# GC_LINE_2026_INCHEON.net
KiCad netlist of a schematic drawn in EAGLE
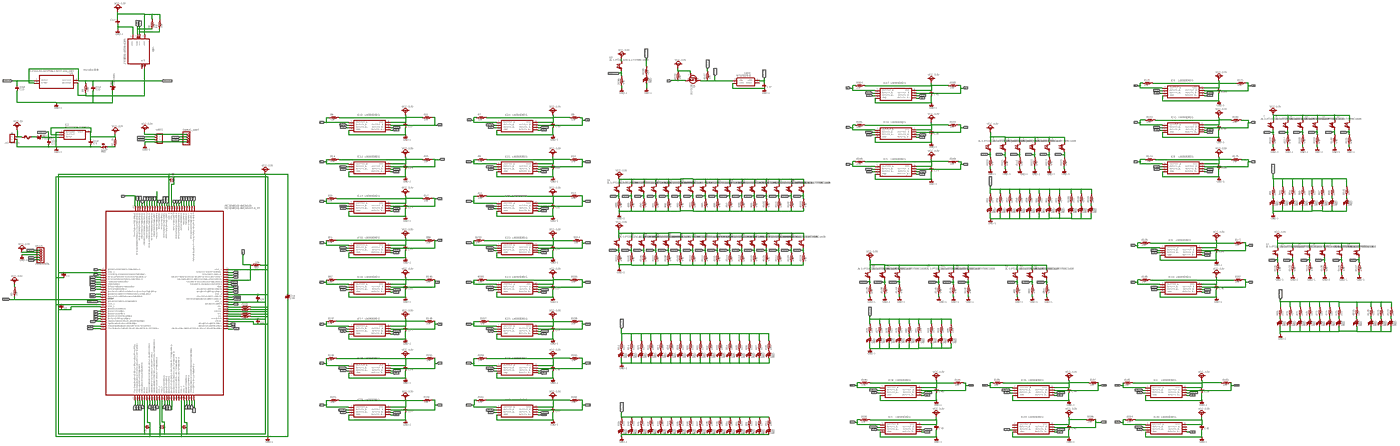
[diagram p0: schematic, sheet 1, overview]
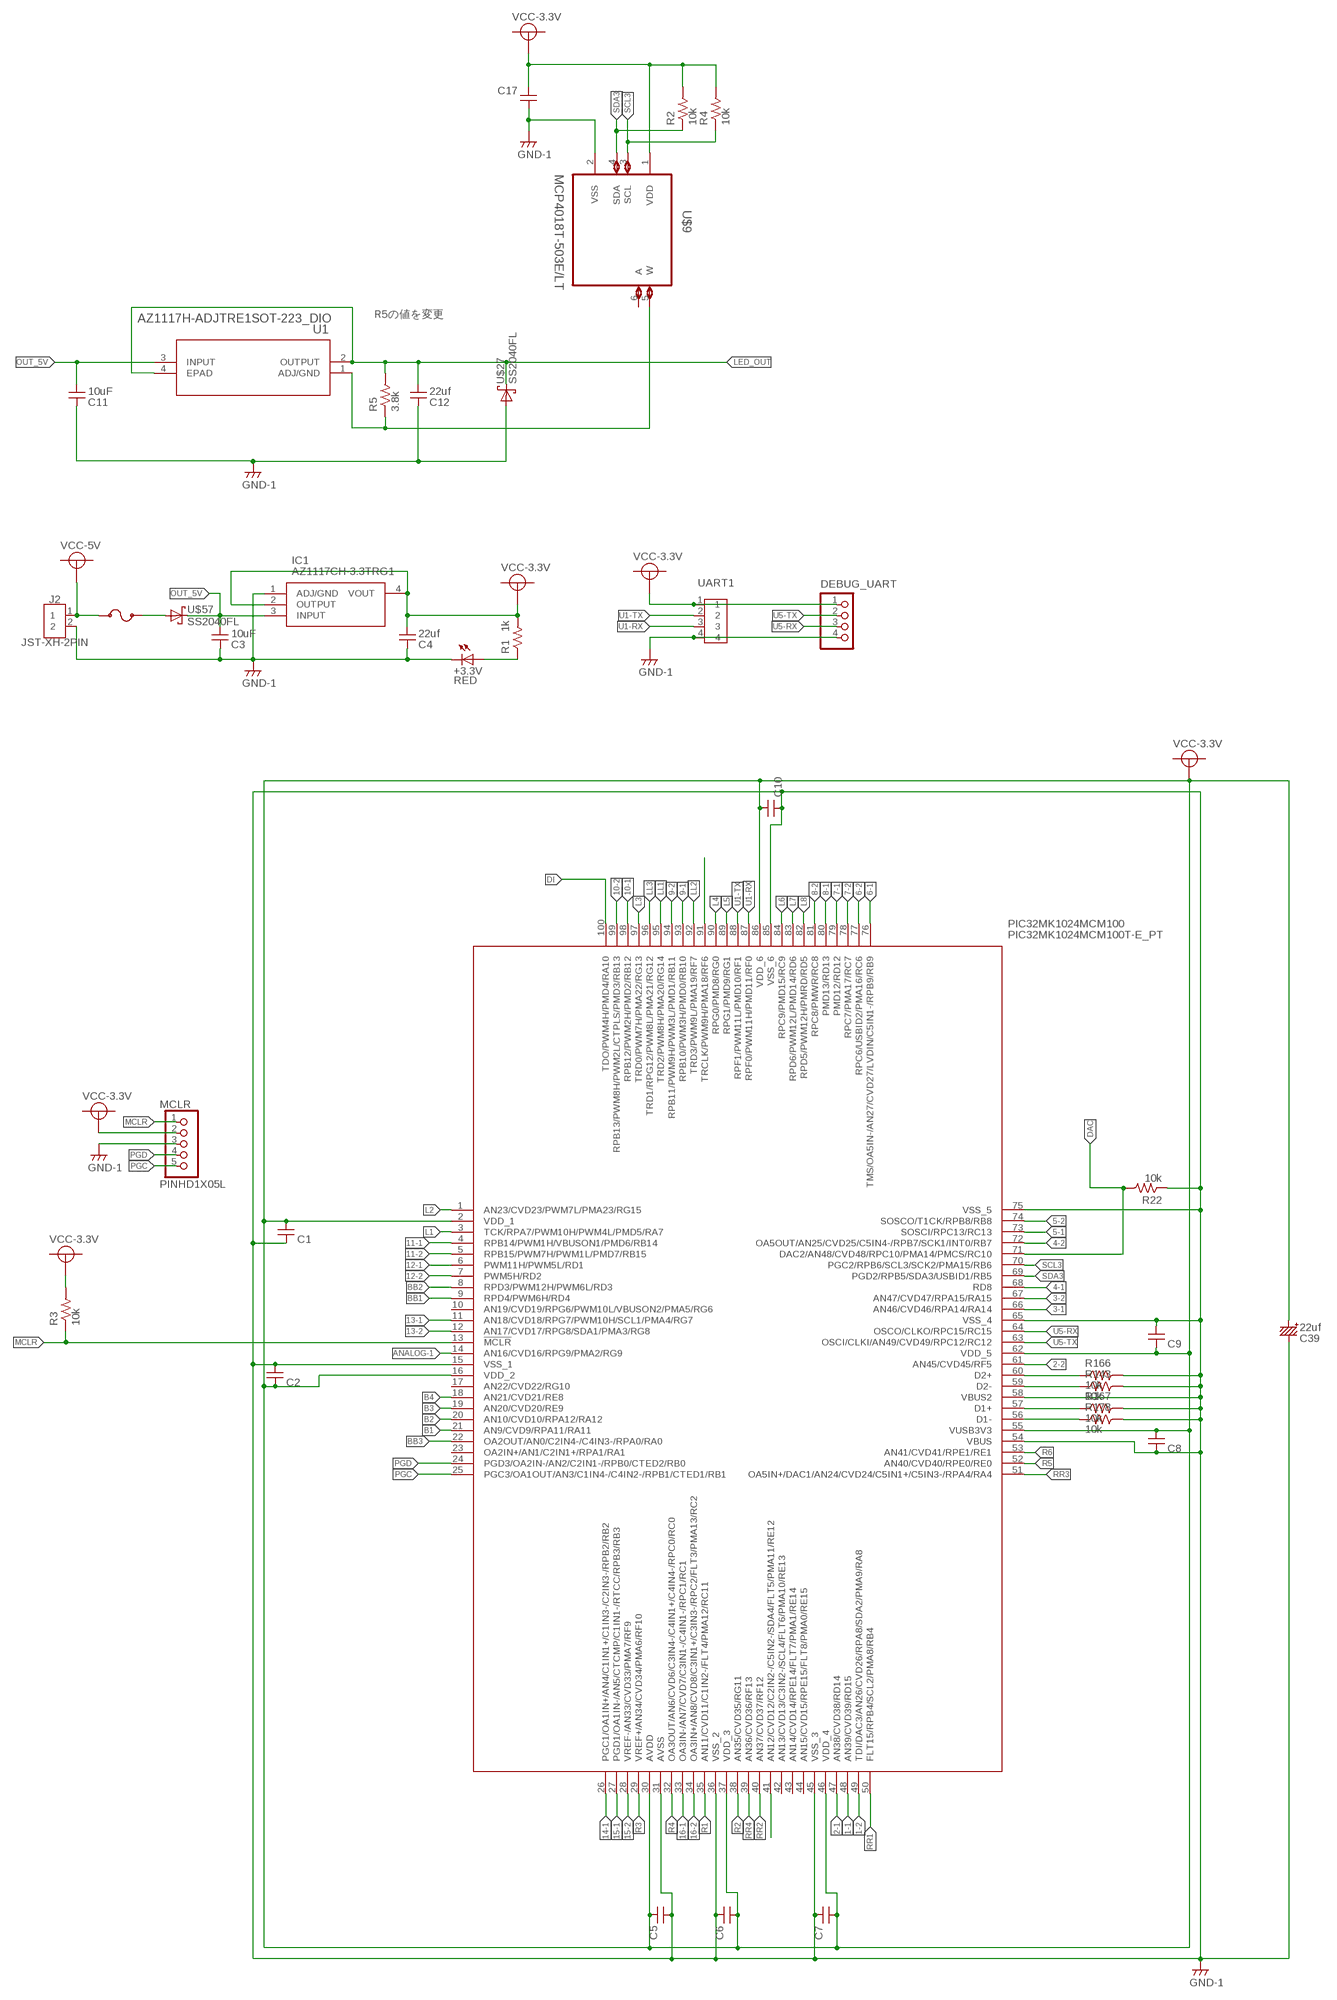
[diagram p1: schematic, sheet 1, part 1 of 4]
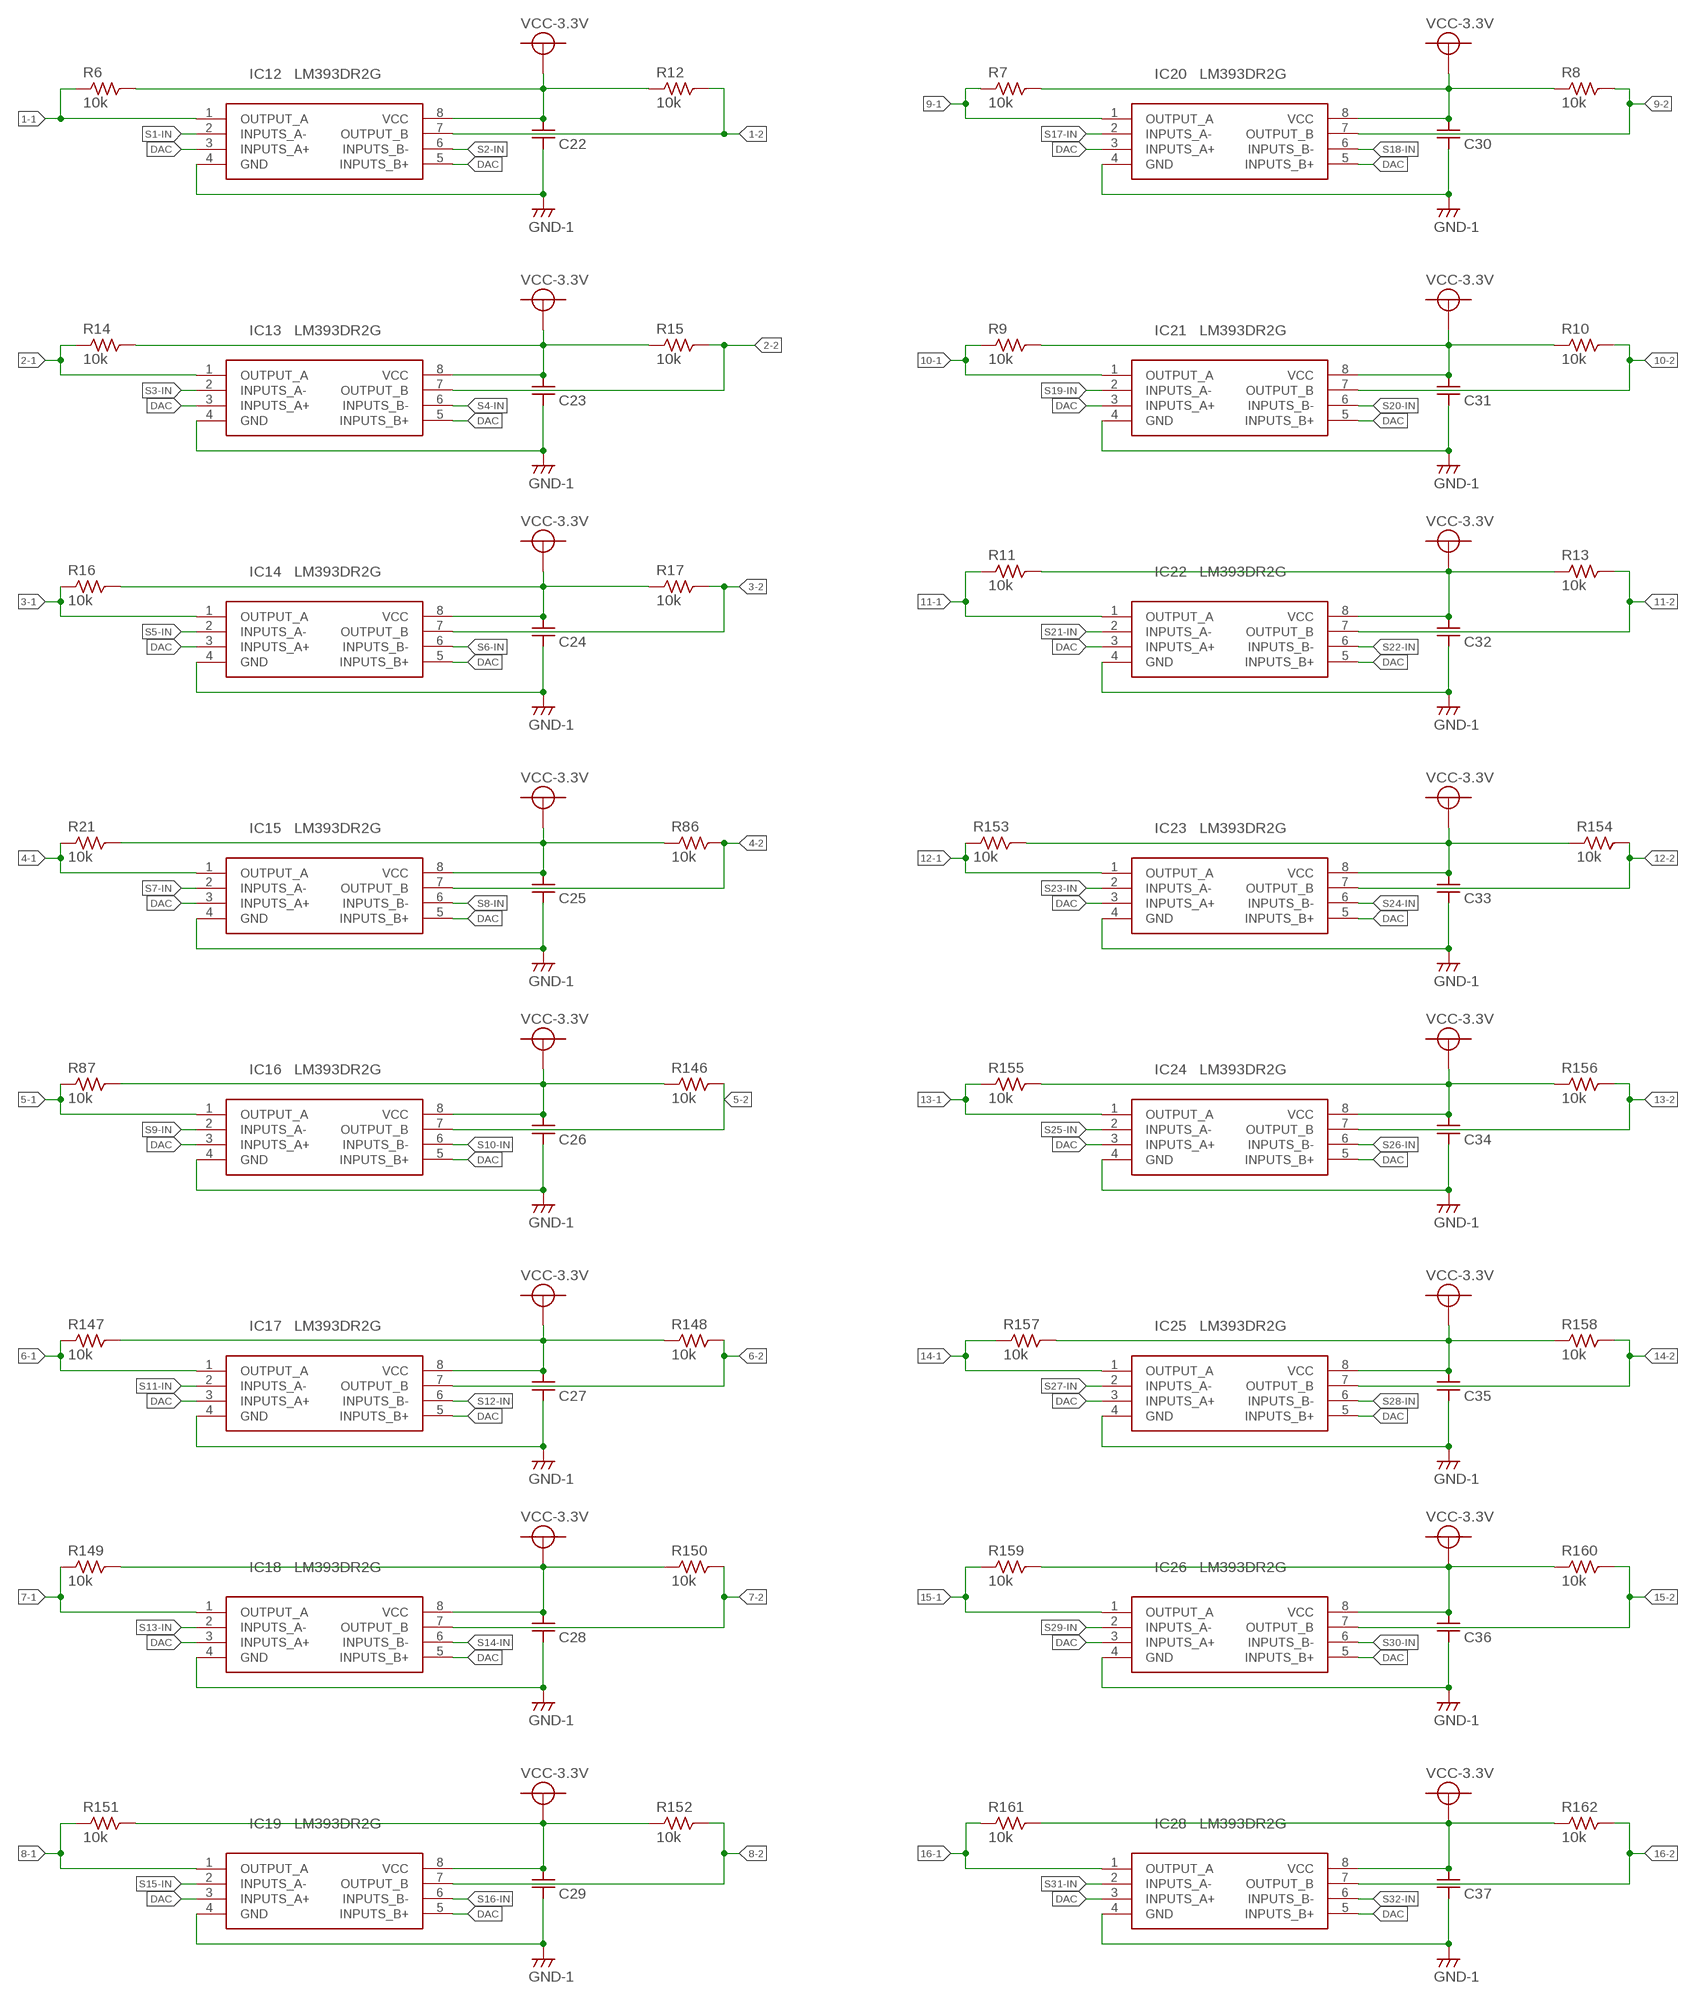
[diagram p2: schematic, sheet 1, part 2 of 4]
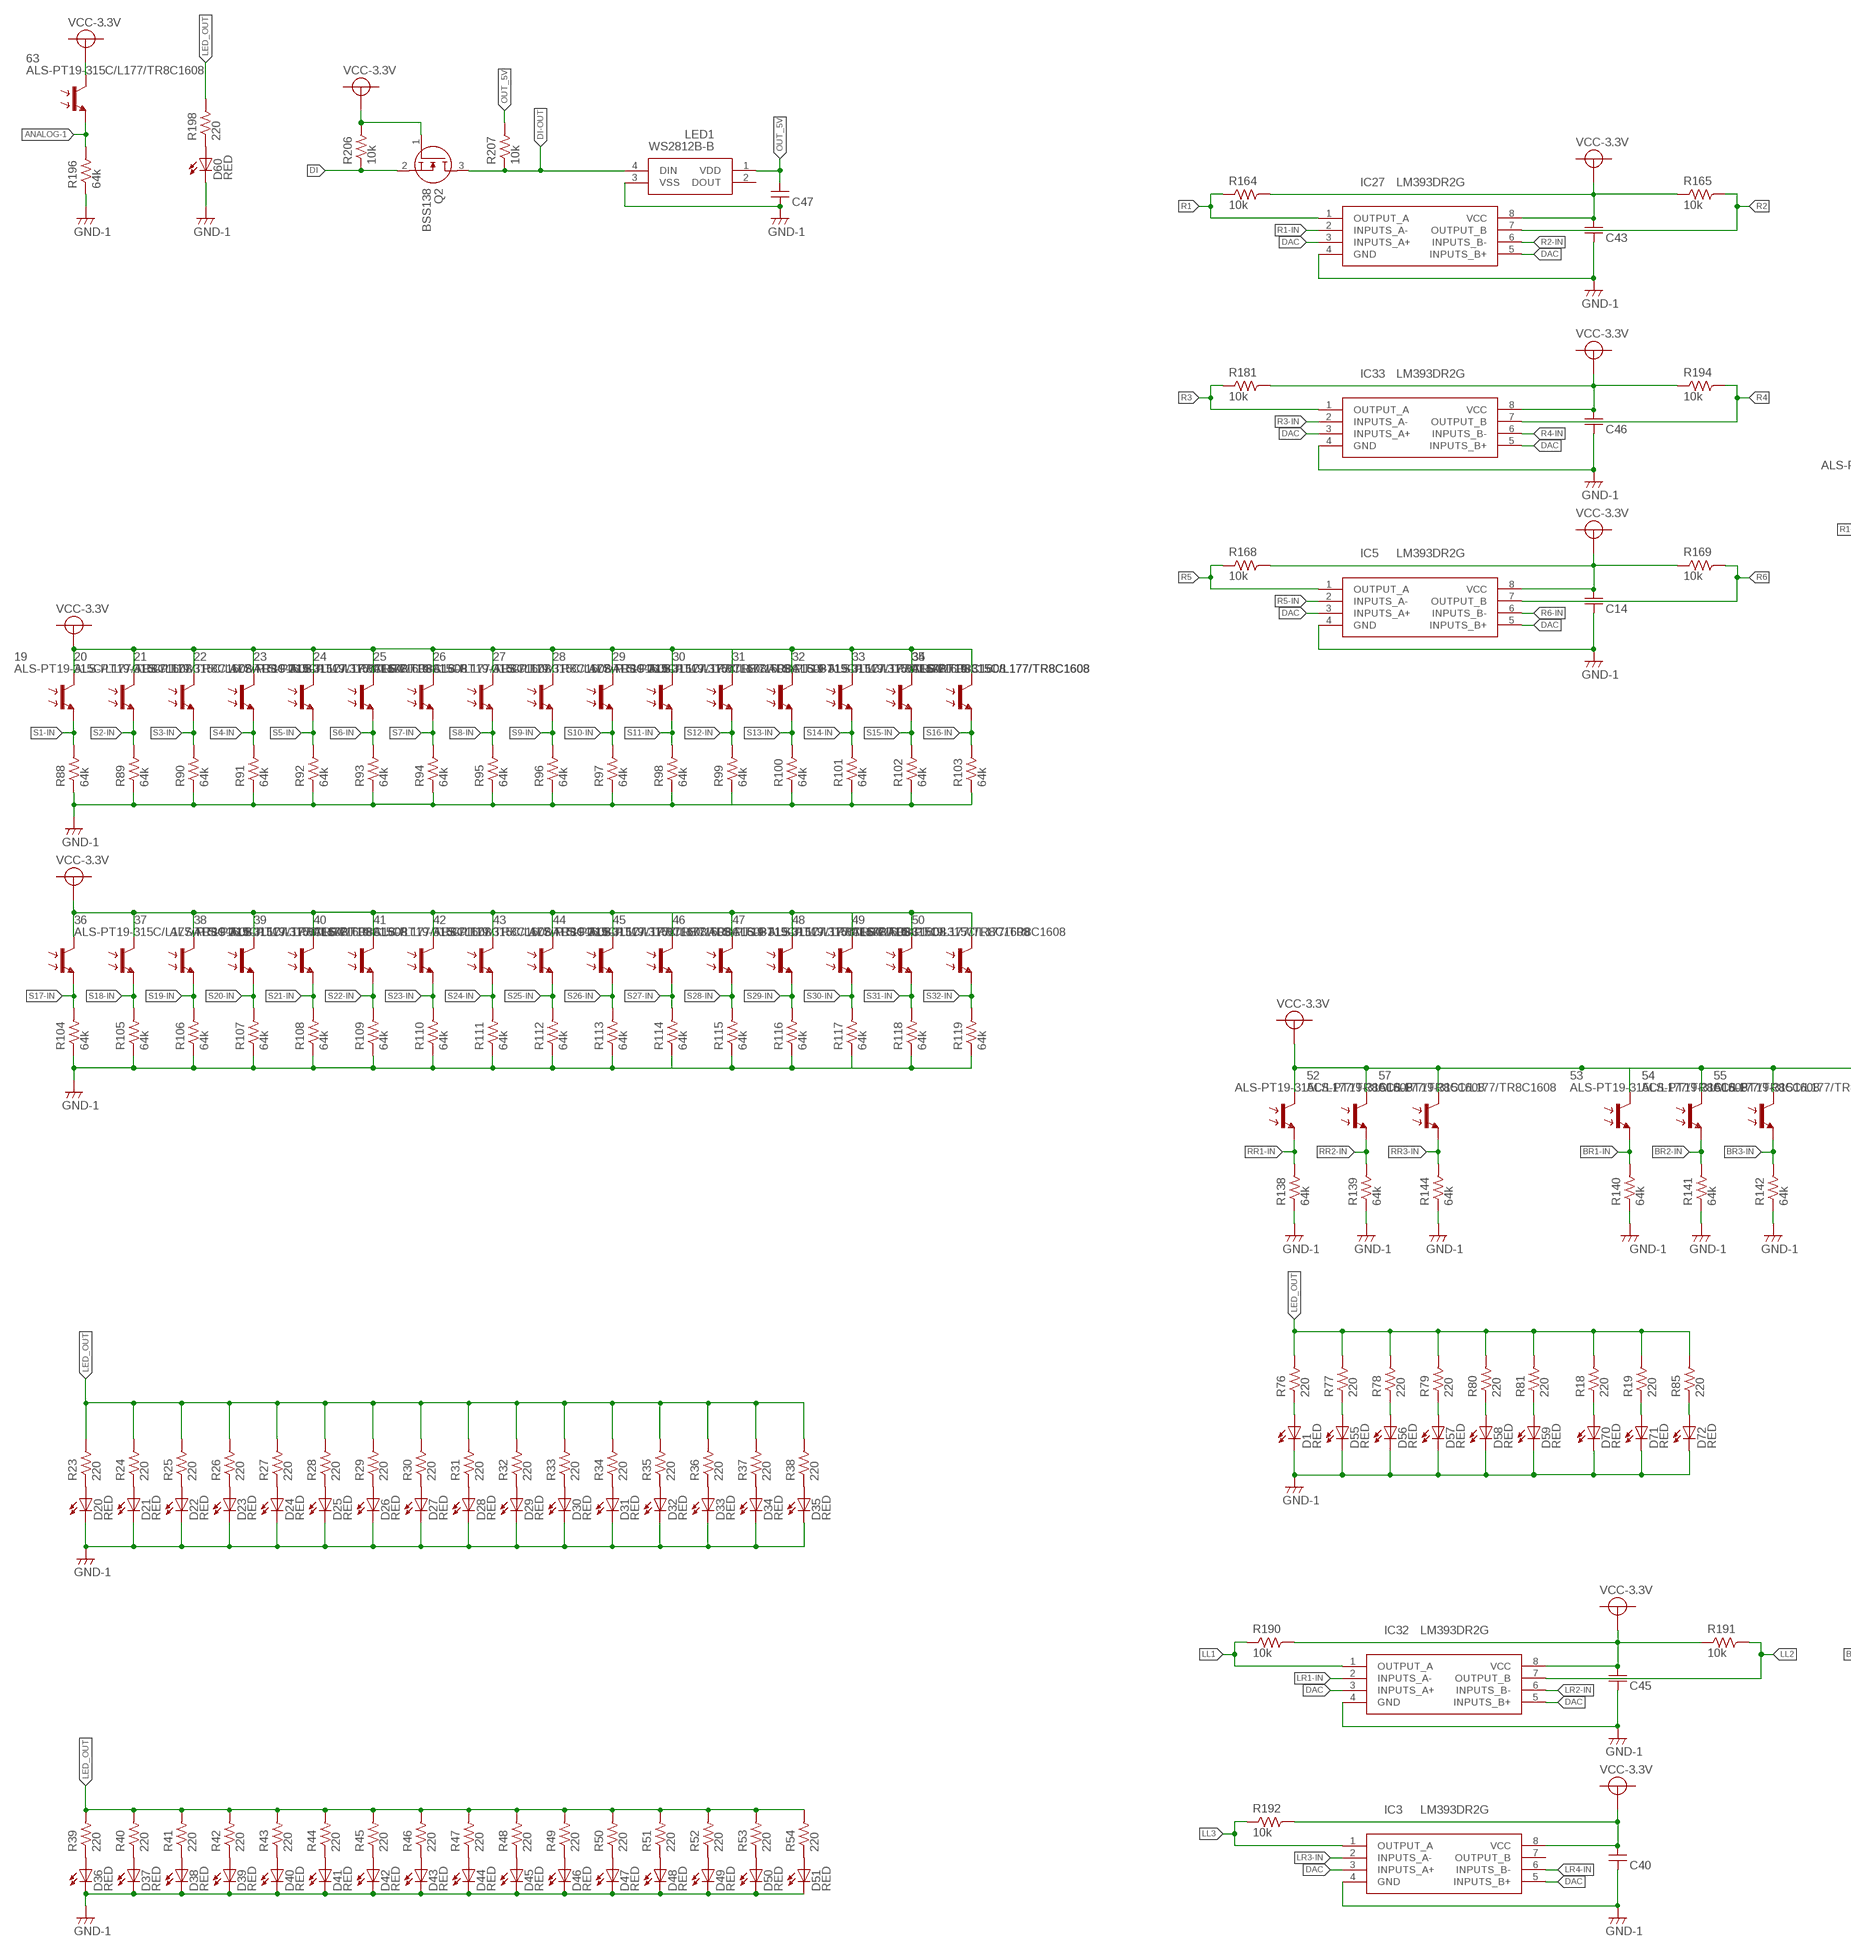
[diagram p3: schematic, sheet 1, part 3 of 4]
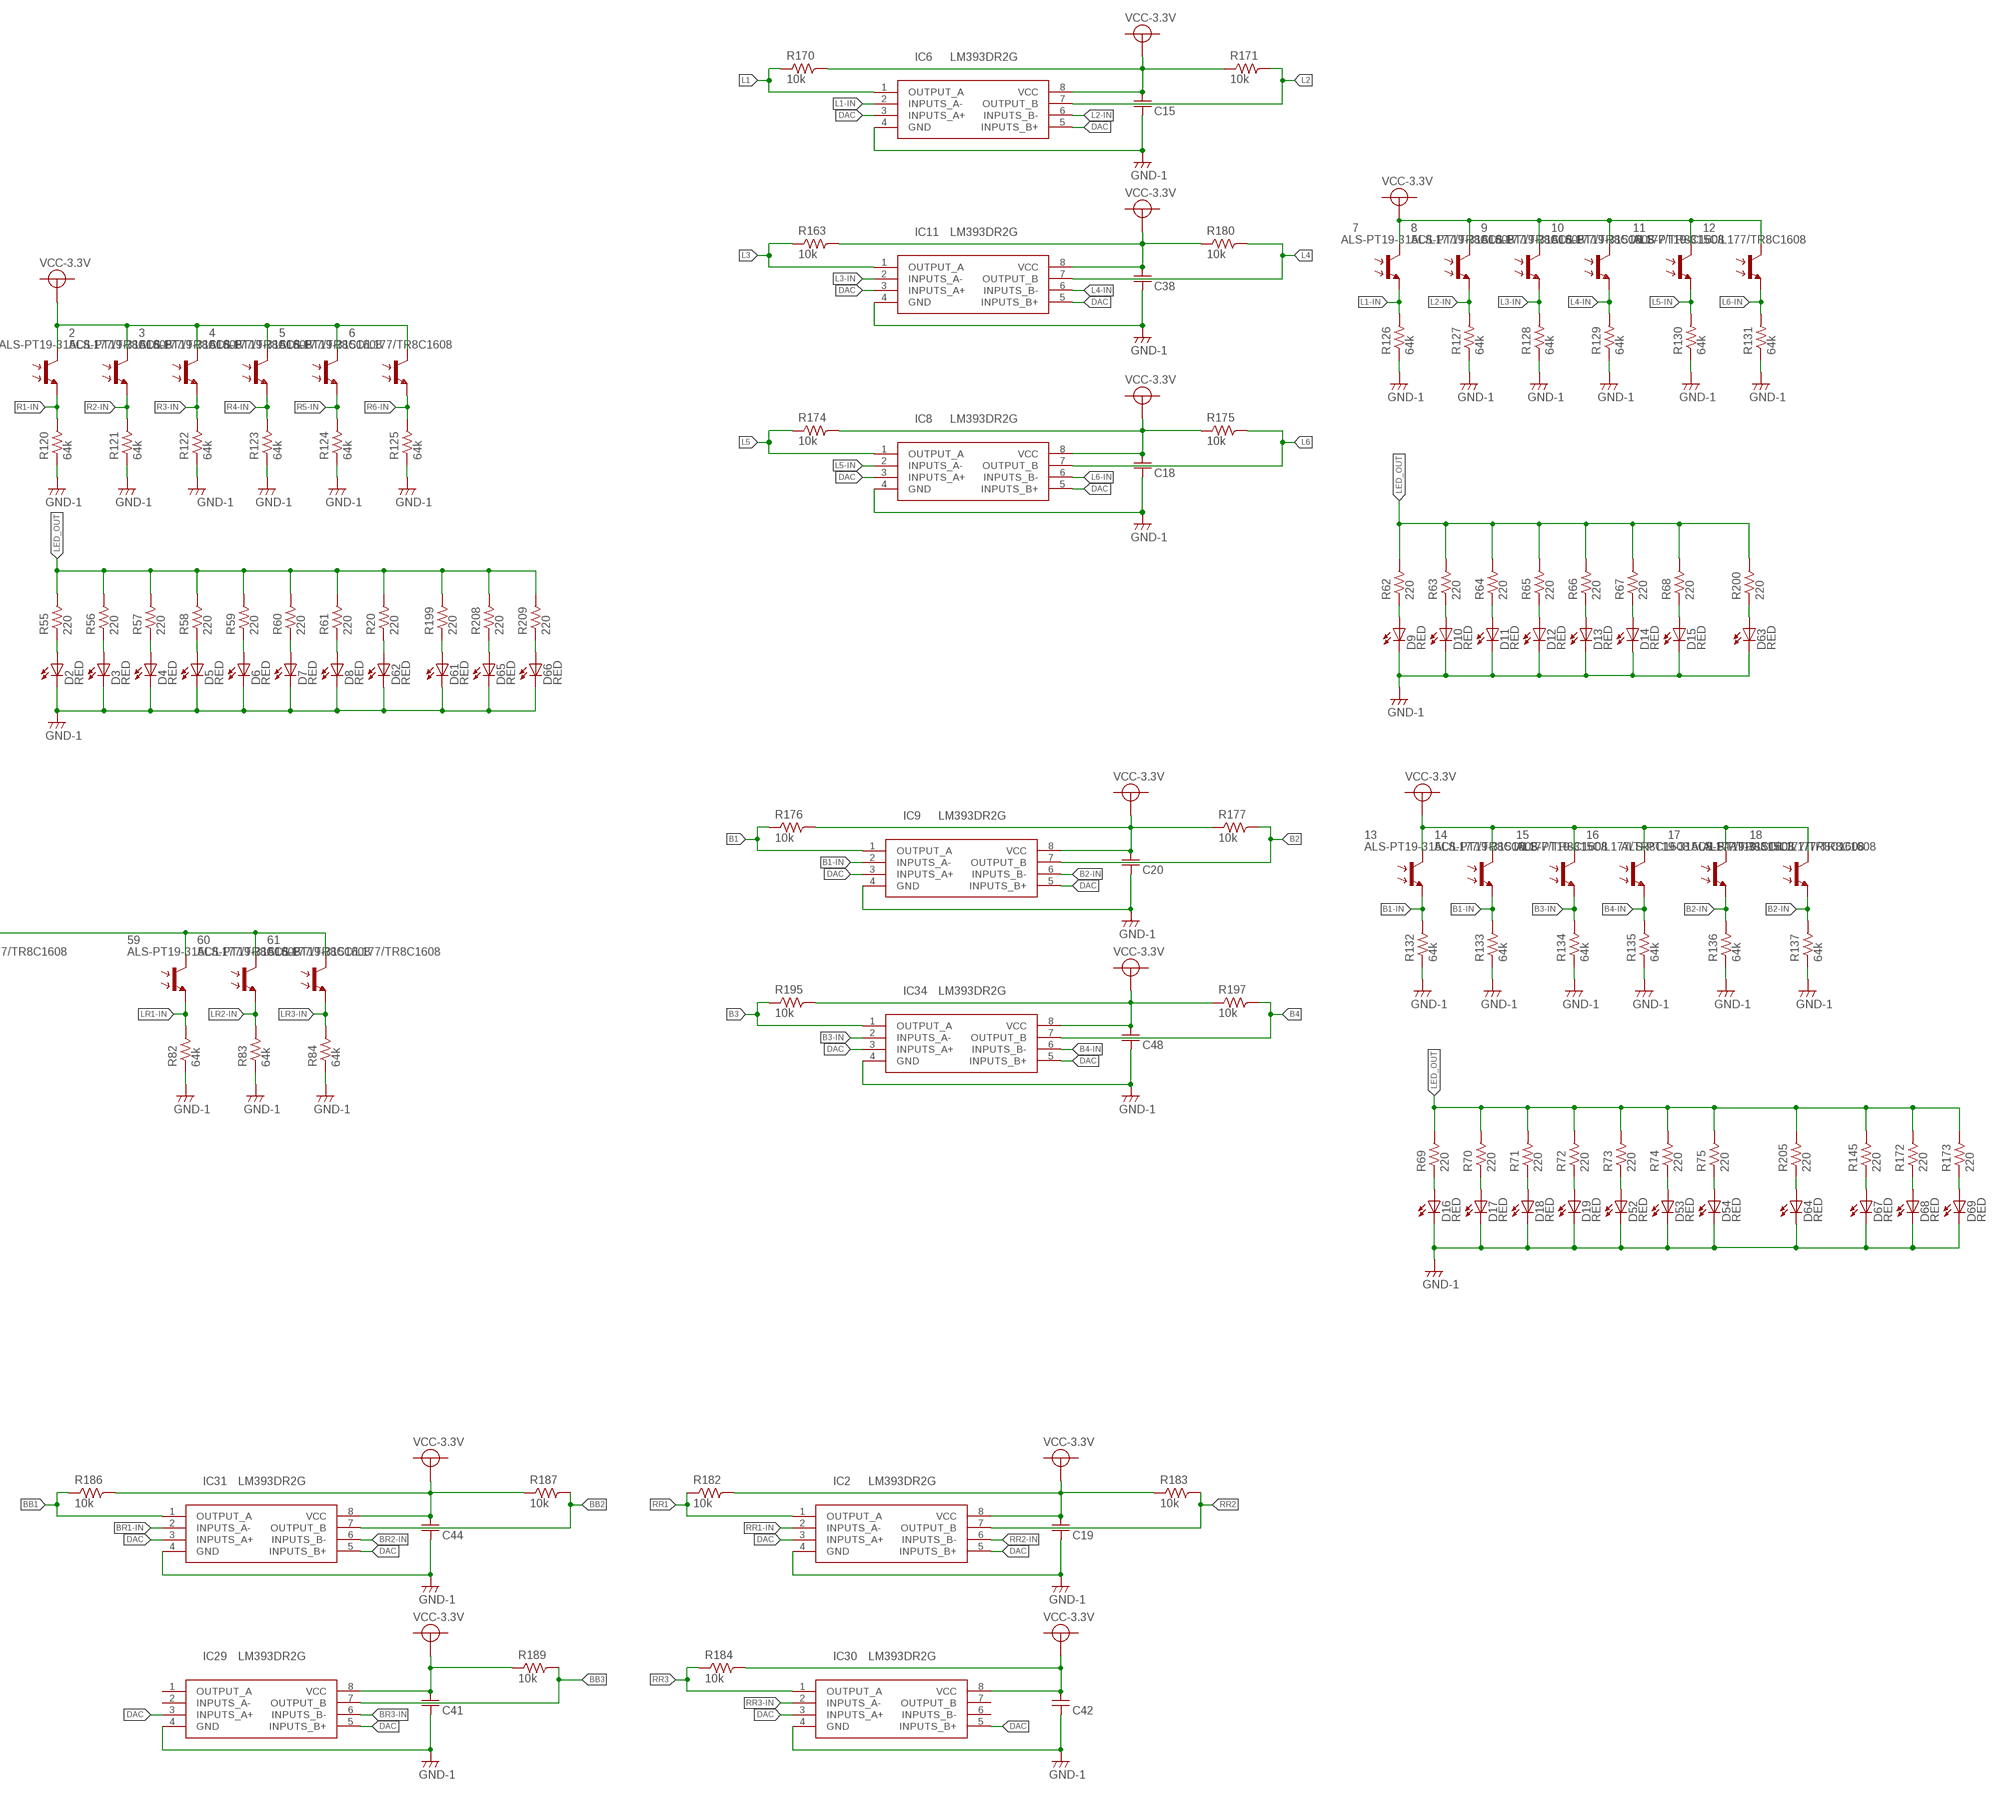
[diagram p4: schematic, sheet 1, part 4 of 4]

(export (version "E")
  (design (tool "Eeschema 10.0.6"))
  (components
    (comp (ref "+3.3V")
      (value "RED")
      (footprint "eagle-import:LEDC1608X55N_FLAT-R")
      (libsource (lib "eagle-import") (part "LEDRED"))
    )
    (comp (ref "1")
      (value "ALS-PT19-315C/L177/TR8C1608")
      (footprint "eagle-import:C1608")
      (libsource (lib "eagle-import") (part "ALS-PT19-315C/L177/TR8C1608"))
    )
    (comp (ref "2")
      (value "ALS-PT19-315C/L177/TR8C1608")
      (footprint "eagle-import:C1608")
      (libsource (lib "eagle-import") (part "ALS-PT19-315C/L177/TR8C1608"))
    )
    (comp (ref "3")
      (value "ALS-PT19-315C/L177/TR8C1608")
      (footprint "eagle-import:C1608")
      (libsource (lib "eagle-import") (part "ALS-PT19-315C/L177/TR8C1608"))
    )
    (comp (ref "4")
      (value "ALS-PT19-315C/L177/TR8C1608")
      (footprint "eagle-import:C1608")
      (libsource (lib "eagle-import") (part "ALS-PT19-315C/L177/TR8C1608"))
    )
    (comp (ref "5")
      (value "ALS-PT19-315C/L177/TR8C1608")
      (footprint "eagle-import:C1608")
      (libsource (lib "eagle-import") (part "ALS-PT19-315C/L177/TR8C1608"))
    )
    (comp (ref "6")
      (value "ALS-PT19-315C/L177/TR8C1608")
      (footprint "eagle-import:C1608")
      (libsource (lib "eagle-import") (part "ALS-PT19-315C/L177/TR8C1608"))
    )
    (comp (ref "7")
      (value "ALS-PT19-315C/L177/TR8C1608")
      (footprint "eagle-import:C1608")
      (libsource (lib "eagle-import") (part "ALS-PT19-315C/L177/TR8C1608"))
    )
    (comp (ref "8")
      (value "ALS-PT19-315C/L177/TR8C1608")
      (footprint "eagle-import:C1608")
      (libsource (lib "eagle-import") (part "ALS-PT19-315C/L177/TR8C1608"))
    )
    (comp (ref "9")
      (value "ALS-PT19-315C/L177/TR8C1608")
      (footprint "eagle-import:C1608")
      (libsource (lib "eagle-import") (part "ALS-PT19-315C/L177/TR8C1608"))
    )
    (comp (ref "10")
      (value "ALS-PT19-315C/L177/TR8C1608")
      (footprint "eagle-import:C1608")
      (libsource (lib "eagle-import") (part "ALS-PT19-315C/L177/TR8C1608"))
    )
    (comp (ref "11")
      (value "ALS-PT19-315C/L177/TR8C1608")
      (footprint "eagle-import:C1608")
      (libsource (lib "eagle-import") (part "ALS-PT19-315C/L177/TR8C1608"))
    )
    (comp (ref "12")
      (value "ALS-PT19-315C/L177/TR8C1608")
      (footprint "eagle-import:C1608")
      (libsource (lib "eagle-import") (part "ALS-PT19-315C/L177/TR8C1608"))
    )
    (comp (ref "13")
      (value "ALS-PT19-315C/L177/TR8C1608")
      (footprint "eagle-import:C1608")
      (libsource (lib "eagle-import") (part "ALS-PT19-315C/L177/TR8C1608"))
    )
    (comp (ref "14")
      (value "ALS-PT19-315C/L177/TR8C1608")
      (footprint "eagle-import:C1608")
      (libsource (lib "eagle-import") (part "ALS-PT19-315C/L177/TR8C1608"))
    )
    (comp (ref "15")
      (value "ALS-PT19-315C/L177/TR8C1608")
      (footprint "eagle-import:C1608")
      (libsource (lib "eagle-import") (part "ALS-PT19-315C/L177/TR8C1608"))
    )
    (comp (ref "16")
      (value "ALS-PT19-315C/L177/TR8C1608")
      (footprint "eagle-import:C1608")
      (libsource (lib "eagle-import") (part "ALS-PT19-315C/L177/TR8C1608"))
    )
    (comp (ref "17")
      (value "ALS-PT19-315C/L177/TR8C1608")
      (footprint "eagle-import:C1608")
      (libsource (lib "eagle-import") (part "ALS-PT19-315C/L177/TR8C1608"))
    )
    (comp (ref "18")
      (value "ALS-PT19-315C/L177/TR8C1608")
      (footprint "eagle-import:C1608")
      (libsource (lib "eagle-import") (part "ALS-PT19-315C/L177/TR8C1608"))
    )
    (comp (ref "19")
      (value "ALS-PT19-315C/L177/TR8C1608")
      (footprint "eagle-import:C1608")
      (libsource (lib "eagle-import") (part "ALS-PT19-315C/L177/TR8C1608"))
    )
    (comp (ref "20")
      (value "ALS-PT19-315C/L177/TR8C1608")
      (footprint "eagle-import:C1608")
      (libsource (lib "eagle-import") (part "ALS-PT19-315C/L177/TR8C1608"))
    )
    (comp (ref "21")
      (value "ALS-PT19-315C/L177/TR8C1608")
      (footprint "eagle-import:C1608")
      (libsource (lib "eagle-import") (part "ALS-PT19-315C/L177/TR8C1608"))
    )
    (comp (ref "22")
      (value "ALS-PT19-315C/L177/TR8C1608")
      (footprint "eagle-import:C1608")
      (libsource (lib "eagle-import") (part "ALS-PT19-315C/L177/TR8C1608"))
    )
    (comp (ref "23")
      (value "ALS-PT19-315C/L177/TR8C1608")
      (footprint "eagle-import:C1608")
      (libsource (lib "eagle-import") (part "ALS-PT19-315C/L177/TR8C1608"))
    )
    (comp (ref "24")
      (value "ALS-PT19-315C/L177/TR8C1608")
      (footprint "eagle-import:C1608")
      (libsource (lib "eagle-import") (part "ALS-PT19-315C/L177/TR8C1608"))
    )
    (comp (ref "25")
      (value "ALS-PT19-315C/L177/TR8C1608")
      (footprint "eagle-import:C1608")
      (libsource (lib "eagle-import") (part "ALS-PT19-315C/L177/TR8C1608"))
    )
    (comp (ref "26")
      (value "ALS-PT19-315C/L177/TR8C1608")
      (footprint "eagle-import:C1608")
      (libsource (lib "eagle-import") (part "ALS-PT19-315C/L177/TR8C1608"))
    )
    (comp (ref "27")
      (value "ALS-PT19-315C/L177/TR8C1608")
      (footprint "eagle-import:C1608")
      (libsource (lib "eagle-import") (part "ALS-PT19-315C/L177/TR8C1608"))
    )
    (comp (ref "28")
      (value "ALS-PT19-315C/L177/TR8C1608")
      (footprint "eagle-import:C1608")
      (libsource (lib "eagle-import") (part "ALS-PT19-315C/L177/TR8C1608"))
    )
    (comp (ref "29")
      (value "ALS-PT19-315C/L177/TR8C1608")
      (footprint "eagle-import:C1608")
      (libsource (lib "eagle-import") (part "ALS-PT19-315C/L177/TR8C1608"))
    )
    (comp (ref "30")
      (value "ALS-PT19-315C/L177/TR8C1608")
      (footprint "eagle-import:C1608")
      (libsource (lib "eagle-import") (part "ALS-PT19-315C/L177/TR8C1608"))
    )
    (comp (ref "31")
      (value "ALS-PT19-315C/L177/TR8C1608")
      (footprint "eagle-import:C1608")
      (libsource (lib "eagle-import") (part "ALS-PT19-315C/L177/TR8C1608"))
    )
    (comp (ref "32")
      (value "ALS-PT19-315C/L177/TR8C1608")
      (footprint "eagle-import:C1608")
      (libsource (lib "eagle-import") (part "ALS-PT19-315C/L177/TR8C1608"))
    )
    (comp (ref "33")
      (value "ALS-PT19-315C/L177/TR8C1608")
      (footprint "eagle-import:C1608")
      (libsource (lib "eagle-import") (part "ALS-PT19-315C/L177/TR8C1608"))
    )
    (comp (ref "34")
      (value "ALS-PT19-315C/L177/TR8C1608")
      (footprint "eagle-import:C1608")
      (libsource (lib "eagle-import") (part "ALS-PT19-315C/L177/TR8C1608"))
    )
    (comp (ref "35")
      (value "ALS-PT19-315C/L177/TR8C1608")
      (footprint "eagle-import:C1608")
      (libsource (lib "eagle-import") (part "ALS-PT19-315C/L177/TR8C1608"))
    )
    (comp (ref "36")
      (value "ALS-PT19-315C/L177/TR8C1608")
      (footprint "eagle-import:C1608")
      (libsource (lib "eagle-import") (part "ALS-PT19-315C/L177/TR8C1608"))
    )
    (comp (ref "37")
      (value "ALS-PT19-315C/L177/TR8C1608")
      (footprint "eagle-import:C1608")
      (libsource (lib "eagle-import") (part "ALS-PT19-315C/L177/TR8C1608"))
    )
    (comp (ref "38")
      (value "ALS-PT19-315C/L177/TR8C1608")
      (footprint "eagle-import:C1608")
      (libsource (lib "eagle-import") (part "ALS-PT19-315C/L177/TR8C1608"))
    )
    (comp (ref "39")
      (value "ALS-PT19-315C/L177/TR8C1608")
      (footprint "eagle-import:C1608")
      (libsource (lib "eagle-import") (part "ALS-PT19-315C/L177/TR8C1608"))
    )
    (comp (ref "40")
      (value "ALS-PT19-315C/L177/TR8C1608")
      (footprint "eagle-import:C1608")
      (libsource (lib "eagle-import") (part "ALS-PT19-315C/L177/TR8C1608"))
    )
    (comp (ref "41")
      (value "ALS-PT19-315C/L177/TR8C1608")
      (footprint "eagle-import:C1608")
      (libsource (lib "eagle-import") (part "ALS-PT19-315C/L177/TR8C1608"))
    )
    (comp (ref "42")
      (value "ALS-PT19-315C/L177/TR8C1608")
      (footprint "eagle-import:C1608")
      (libsource (lib "eagle-import") (part "ALS-PT19-315C/L177/TR8C1608"))
    )
    (comp (ref "43")
      (value "ALS-PT19-315C/L177/TR8C1608")
      (footprint "eagle-import:C1608")
      (libsource (lib "eagle-import") (part "ALS-PT19-315C/L177/TR8C1608"))
    )
    (comp (ref "44")
      (value "ALS-PT19-315C/L177/TR8C1608")
      (footprint "eagle-import:C1608")
      (libsource (lib "eagle-import") (part "ALS-PT19-315C/L177/TR8C1608"))
    )
    (comp (ref "45")
      (value "ALS-PT19-315C/L177/TR8C1608")
      (footprint "eagle-import:C1608")
      (libsource (lib "eagle-import") (part "ALS-PT19-315C/L177/TR8C1608"))
    )
    (comp (ref "46")
      (value "ALS-PT19-315C/L177/TR8C1608")
      (footprint "eagle-import:C1608")
      (libsource (lib "eagle-import") (part "ALS-PT19-315C/L177/TR8C1608"))
    )
    (comp (ref "47")
      (value "ALS-PT19-315C/L177/TR8C1608")
      (footprint "eagle-import:C1608")
      (libsource (lib "eagle-import") (part "ALS-PT19-315C/L177/TR8C1608"))
    )
    (comp (ref "48")
      (value "ALS-PT19-315C/L177/TR8C1608")
      (footprint "eagle-import:C1608")
      (libsource (lib "eagle-import") (part "ALS-PT19-315C/L177/TR8C1608"))
    )
    (comp (ref "49")
      (value "ALS-PT19-315C/L177/TR8C1608")
      (footprint "eagle-import:C1608")
      (libsource (lib "eagle-import") (part "ALS-PT19-315C/L177/TR8C1608"))
    )
    (comp (ref "50")
      (value "ALS-PT19-315C/L177/TR8C1608")
      (footprint "eagle-import:C1608")
      (libsource (lib "eagle-import") (part "ALS-PT19-315C/L177/TR8C1608"))
    )
    (comp (ref "51")
      (value "ALS-PT19-315C/L177/TR8C1608")
      (footprint "eagle-import:C1608")
      (libsource (lib "eagle-import") (part "ALS-PT19-315C/L177/TR8C1608"))
    )
    (comp (ref "52")
      (value "ALS-PT19-315C/L177/TR8C1608")
      (footprint "eagle-import:C1608")
      (libsource (lib "eagle-import") (part "ALS-PT19-315C/L177/TR8C1608"))
    )
    (comp (ref "53")
      (value "ALS-PT19-315C/L177/TR8C1608")
      (footprint "eagle-import:C1608")
      (libsource (lib "eagle-import") (part "ALS-PT19-315C/L177/TR8C1608"))
    )
    (comp (ref "54")
      (value "ALS-PT19-315C/L177/TR8C1608")
      (footprint "eagle-import:C1608")
      (libsource (lib "eagle-import") (part "ALS-PT19-315C/L177/TR8C1608"))
    )
    (comp (ref "55")
      (value "ALS-PT19-315C/L177/TR8C1608")
      (footprint "eagle-import:C1608")
      (libsource (lib "eagle-import") (part "ALS-PT19-315C/L177/TR8C1608"))
    )
    (comp (ref "57")
      (value "ALS-PT19-315C/L177/TR8C1608")
      (footprint "eagle-import:C1608")
      (libsource (lib "eagle-import") (part "ALS-PT19-315C/L177/TR8C1608"))
    )
    (comp (ref "59")
      (value "ALS-PT19-315C/L177/TR8C1608")
      (footprint "eagle-import:C1608")
      (libsource (lib "eagle-import") (part "ALS-PT19-315C/L177/TR8C1608"))
    )
    (comp (ref "60")
      (value "ALS-PT19-315C/L177/TR8C1608")
      (footprint "eagle-import:C1608")
      (libsource (lib "eagle-import") (part "ALS-PT19-315C/L177/TR8C1608"))
    )
    (comp (ref "61")
      (value "ALS-PT19-315C/L177/TR8C1608")
      (footprint "eagle-import:C1608")
      (libsource (lib "eagle-import") (part "ALS-PT19-315C/L177/TR8C1608"))
    )
    (comp (ref "63")
      (value "ALS-PT19-315C/L177/TR8C1608")
      (footprint "eagle-import:C1608")
      (libsource (lib "eagle-import") (part "ALS-PT19-315C/L177/TR8C1608"))
    )
    (comp (ref "C1")
      (value "0.1uF")
      (footprint "eagle-import:C1608")
      (libsource (lib "eagle-import") (part "CC1068"))
    )
    (comp (ref "C2")
      (value "0.1uF")
      (footprint "eagle-import:C1608")
      (libsource (lib "eagle-import") (part "CC1068"))
    )
    (comp (ref "C3")
      (value "10uF")
      (footprint "eagle-import:C1608")
      (libsource (lib "eagle-import") (part "RLC_vf.Zptc1PYOQp6T00ZjicgECQ_CC25V10UF1608(0603)"))
    )
    (comp (ref "C4")
      (value "22uf")
      (footprint "eagle-import:C1608")
      (libsource (lib "eagle-import") (part "CC6.3V22UF1608(0603)"))
    )
    (comp (ref "C5")
      (value "0.1uF")
      (footprint "eagle-import:C1608")
      (libsource (lib "eagle-import") (part "CC1068"))
    )
    (comp (ref "C6")
      (value "0.1uF")
      (footprint "eagle-import:C1608")
      (libsource (lib "eagle-import") (part "CC1068"))
    )
    (comp (ref "C7")
      (value "0.1uF")
      (footprint "eagle-import:C1608")
      (libsource (lib "eagle-import") (part "CC1068"))
    )
    (comp (ref "C8")
      (value "0.1uF")
      (footprint "eagle-import:C1608")
      (libsource (lib "eagle-import") (part "CC1068"))
    )
    (comp (ref "C9")
      (value "0.1uF")
      (footprint "eagle-import:C1608")
      (libsource (lib "eagle-import") (part "CC1068"))
    )
    (comp (ref "C10")
      (value "0.1uF")
      (footprint "eagle-import:C1608")
      (libsource (lib "eagle-import") (part "CC1068"))
    )
    (comp (ref "C11")
      (value "10uF")
      (footprint "eagle-import:C1608")
      (libsource (lib "eagle-import") (part "RLC_vf.Zptc1PYOQp6T00ZjicgECQ_CC25V10UF1608(0603)"))
    )
    (comp (ref "C12")
      (value "22uf")
      (footprint "eagle-import:C1608")
      (libsource (lib "eagle-import") (part "CC6.3V22UF1608(0603)"))
    )
    (comp (ref "C14")
      (value "0.1uF")
      (footprint "eagle-import:C1608")
      (libsource (lib "eagle-import") (part "CC1068"))
    )
    (comp (ref "C15")
      (value "0.1uF")
      (footprint "eagle-import:C1608")
      (libsource (lib "eagle-import") (part "CC1068"))
    )
    (comp (ref "C17")
      (value "0.1uF")
      (footprint "eagle-import:C1608")
      (libsource (lib "eagle-import") (part "CC1068"))
    )
    (comp (ref "C18")
      (value "0.1uF")
      (footprint "eagle-import:C1608")
      (libsource (lib "eagle-import") (part "CC1068"))
    )
    (comp (ref "C19")
      (value "0.1uF")
      (footprint "eagle-import:C1608")
      (libsource (lib "eagle-import") (part "CC1068"))
    )
    (comp (ref "C20")
      (value "0.1uF")
      (footprint "eagle-import:C1608")
      (libsource (lib "eagle-import") (part "CC1068"))
    )
    (comp (ref "C22")
      (value "0.1uF")
      (footprint "eagle-import:C1608")
      (libsource (lib "eagle-import") (part "CC1068"))
    )
    (comp (ref "C23")
      (value "0.1uF")
      (footprint "eagle-import:C1608")
      (libsource (lib "eagle-import") (part "CC1068"))
    )
    (comp (ref "C24")
      (value "0.1uF")
      (footprint "eagle-import:C1608")
      (libsource (lib "eagle-import") (part "CC1068"))
    )
    (comp (ref "C25")
      (value "0.1uF")
      (footprint "eagle-import:C1608")
      (libsource (lib "eagle-import") (part "CC1068"))
    )
    (comp (ref "C26")
      (value "0.1uF")
      (footprint "eagle-import:C1608")
      (libsource (lib "eagle-import") (part "CC1068"))
    )
    (comp (ref "C27")
      (value "0.1uF")
      (footprint "eagle-import:C1608")
      (libsource (lib "eagle-import") (part "CC1068"))
    )
    (comp (ref "C28")
      (value "0.1uF")
      (footprint "eagle-import:C1608")
      (libsource (lib "eagle-import") (part "CC1068"))
    )
    (comp (ref "C29")
      (value "0.1uF")
      (footprint "eagle-import:C1608")
      (libsource (lib "eagle-import") (part "CC1068"))
    )
    (comp (ref "C30")
      (value "0.1uF")
      (footprint "eagle-import:C1608")
      (libsource (lib "eagle-import") (part "CC1068"))
    )
    (comp (ref "C31")
      (value "0.1uF")
      (footprint "eagle-import:C1608")
      (libsource (lib "eagle-import") (part "CC1068"))
    )
    (comp (ref "C32")
      (value "0.1uF")
      (footprint "eagle-import:C1608")
      (libsource (lib "eagle-import") (part "CC1068"))
    )
    (comp (ref "C33")
      (value "0.1uF")
      (footprint "eagle-import:C1608")
      (libsource (lib "eagle-import") (part "CC1068"))
    )
    (comp (ref "C34")
      (value "0.1uF")
      (footprint "eagle-import:C1608")
      (libsource (lib "eagle-import") (part "CC1068"))
    )
    (comp (ref "C35")
      (value "0.1uF")
      (footprint "eagle-import:C1608")
      (libsource (lib "eagle-import") (part "CC1068"))
    )
    (comp (ref "C36")
      (value "0.1uF")
      (footprint "eagle-import:C1608")
      (libsource (lib "eagle-import") (part "CC1068"))
    )
    (comp (ref "C37")
      (value "0.1uF")
      (footprint "eagle-import:C1608")
      (libsource (lib "eagle-import") (part "CC1068"))
    )
    (comp (ref "C38")
      (value "0.1uF")
      (footprint "eagle-import:C1608")
      (libsource (lib "eagle-import") (part "CC1068"))
    )
    (comp (ref "C39")
      (value "22uf")
      (footprint "eagle-import:CC_3")
      (libsource (lib "eagle-import") (part "C+25V100"))
    )
    (comp (ref "C40")
      (value "0.1uF")
      (footprint "eagle-import:C1608")
      (libsource (lib "eagle-import") (part "CC1068"))
    )
    (comp (ref "C41")
      (value "0.1uF")
      (footprint "eagle-import:C1608")
      (libsource (lib "eagle-import") (part "CC1068"))
    )
    (comp (ref "C42")
      (value "0.1uF")
      (footprint "eagle-import:C1608")
      (libsource (lib "eagle-import") (part "CC1068"))
    )
    (comp (ref "C43")
      (value "0.1uF")
      (footprint "eagle-import:C1608")
      (libsource (lib "eagle-import") (part "CC1068"))
    )
    (comp (ref "C44")
      (value "0.1uF")
      (footprint "eagle-import:C1608")
      (libsource (lib "eagle-import") (part "CC1068"))
    )
    (comp (ref "C45")
      (value "0.1uF")
      (footprint "eagle-import:C1608")
      (libsource (lib "eagle-import") (part "CC1068"))
    )
    (comp (ref "C46")
      (value "0.1uF")
      (footprint "eagle-import:C1608")
      (libsource (lib "eagle-import") (part "CC1068"))
    )
    (comp (ref "C47")
      (value "0.1uF")
      (footprint "eagle-import:C1608")
      (libsource (lib "eagle-import") (part "CC1068"))
    )
    (comp (ref "C48")
      (value "0.1uF")
      (footprint "eagle-import:C1608")
      (libsource (lib "eagle-import") (part "CC1068"))
    )
    (comp (ref "D1")
      (value "RED")
      (footprint "eagle-import:CHIPLED_0603")
      (libsource (lib "eagle-import") (part "Robo_muscle-Diode_vf.UtgNshgcRRiQhBLyTmKZbQ_LEDRED"))
    )
    (comp (ref "D2")
      (value "RED")
      (footprint "eagle-import:CHIPLED_0603")
      (libsource (lib "eagle-import") (part "Robo_muscle-Diode_vf.UtgNshgcRRiQhBLyTmKZbQ_LEDRED"))
    )
    (comp (ref "D3")
      (value "RED")
      (footprint "eagle-import:CHIPLED_0603")
      (libsource (lib "eagle-import") (part "Robo_muscle-Diode_vf.UtgNshgcRRiQhBLyTmKZbQ_LEDRED"))
    )
    (comp (ref "D4")
      (value "RED")
      (footprint "eagle-import:CHIPLED_0603")
      (libsource (lib "eagle-import") (part "Robo_muscle-Diode_vf.UtgNshgcRRiQhBLyTmKZbQ_LEDRED"))
    )
    (comp (ref "D5")
      (value "RED")
      (footprint "eagle-import:CHIPLED_0603")
      (libsource (lib "eagle-import") (part "Robo_muscle-Diode_vf.UtgNshgcRRiQhBLyTmKZbQ_LEDRED"))
    )
    (comp (ref "D6")
      (value "RED")
      (footprint "eagle-import:CHIPLED_0603")
      (libsource (lib "eagle-import") (part "Robo_muscle-Diode_vf.UtgNshgcRRiQhBLyTmKZbQ_LEDRED"))
    )
    (comp (ref "D7")
      (value "RED")
      (footprint "eagle-import:CHIPLED_0603")
      (libsource (lib "eagle-import") (part "Robo_muscle-Diode_vf.UtgNshgcRRiQhBLyTmKZbQ_LEDRED"))
    )
    (comp (ref "D8")
      (value "RED")
      (footprint "eagle-import:CHIPLED_0603")
      (libsource (lib "eagle-import") (part "Robo_muscle-Diode_vf.UtgNshgcRRiQhBLyTmKZbQ_LEDRED"))
    )
    (comp (ref "D9")
      (value "RED")
      (footprint "eagle-import:CHIPLED_0603")
      (libsource (lib "eagle-import") (part "Robo_muscle-Diode_vf.UtgNshgcRRiQhBLyTmKZbQ_LEDRED"))
    )
    (comp (ref "D10")
      (value "RED")
      (footprint "eagle-import:CHIPLED_0603")
      (libsource (lib "eagle-import") (part "Robo_muscle-Diode_vf.UtgNshgcRRiQhBLyTmKZbQ_LEDRED"))
    )
    (comp (ref "D11")
      (value "RED")
      (footprint "eagle-import:CHIPLED_0603")
      (libsource (lib "eagle-import") (part "Robo_muscle-Diode_vf.UtgNshgcRRiQhBLyTmKZbQ_LEDRED"))
    )
    (comp (ref "D12")
      (value "RED")
      (footprint "eagle-import:CHIPLED_0603")
      (libsource (lib "eagle-import") (part "Robo_muscle-Diode_vf.UtgNshgcRRiQhBLyTmKZbQ_LEDRED"))
    )
    (comp (ref "D13")
      (value "RED")
      (footprint "eagle-import:CHIPLED_0603")
      (libsource (lib "eagle-import") (part "Robo_muscle-Diode_vf.UtgNshgcRRiQhBLyTmKZbQ_LEDRED"))
    )
    (comp (ref "D14")
      (value "RED")
      (footprint "eagle-import:CHIPLED_0603")
      (libsource (lib "eagle-import") (part "Robo_muscle-Diode_vf.UtgNshgcRRiQhBLyTmKZbQ_LEDRED"))
    )
    (comp (ref "D15")
      (value "RED")
      (footprint "eagle-import:CHIPLED_0603")
      (libsource (lib "eagle-import") (part "Robo_muscle-Diode_vf.UtgNshgcRRiQhBLyTmKZbQ_LEDRED"))
    )
    (comp (ref "D16")
      (value "RED")
      (footprint "eagle-import:CHIPLED_0603")
      (libsource (lib "eagle-import") (part "Robo_muscle-Diode_vf.UtgNshgcRRiQhBLyTmKZbQ_LEDRED"))
    )
    (comp (ref "D17")
      (value "RED")
      (footprint "eagle-import:CHIPLED_0603")
      (libsource (lib "eagle-import") (part "Robo_muscle-Diode_vf.UtgNshgcRRiQhBLyTmKZbQ_LEDRED"))
    )
    (comp (ref "D18")
      (value "RED")
      (footprint "eagle-import:CHIPLED_0603")
      (libsource (lib "eagle-import") (part "Robo_muscle-Diode_vf.UtgNshgcRRiQhBLyTmKZbQ_LEDRED"))
    )
    (comp (ref "D19")
      (value "RED")
      (footprint "eagle-import:CHIPLED_0603")
      (libsource (lib "eagle-import") (part "Robo_muscle-Diode_vf.UtgNshgcRRiQhBLyTmKZbQ_LEDRED"))
    )
    (comp (ref "D20")
      (value "RED")
      (footprint "eagle-import:CHIPLED_0603")
      (libsource (lib "eagle-import") (part "Robo_muscle-Diode_vf.UtgNshgcRRiQhBLyTmKZbQ_LEDRED"))
    )
    (comp (ref "D21")
      (value "RED")
      (footprint "eagle-import:CHIPLED_0603")
      (libsource (lib "eagle-import") (part "Robo_muscle-Diode_vf.UtgNshgcRRiQhBLyTmKZbQ_LEDRED"))
    )
    (comp (ref "D22")
      (value "RED")
      (footprint "eagle-import:CHIPLED_0603")
      (libsource (lib "eagle-import") (part "Robo_muscle-Diode_vf.UtgNshgcRRiQhBLyTmKZbQ_LEDRED"))
    )
    (comp (ref "D23")
      (value "RED")
      (footprint "eagle-import:CHIPLED_0603")
      (libsource (lib "eagle-import") (part "Robo_muscle-Diode_vf.UtgNshgcRRiQhBLyTmKZbQ_LEDRED"))
    )
    (comp (ref "D24")
      (value "RED")
      (footprint "eagle-import:CHIPLED_0603")
      (libsource (lib "eagle-import") (part "Robo_muscle-Diode_vf.UtgNshgcRRiQhBLyTmKZbQ_LEDRED"))
    )
    (comp (ref "D25")
      (value "RED")
      (footprint "eagle-import:CHIPLED_0603")
      (libsource (lib "eagle-import") (part "Robo_muscle-Diode_vf.UtgNshgcRRiQhBLyTmKZbQ_LEDRED"))
    )
    (comp (ref "D26")
      (value "RED")
      (footprint "eagle-import:CHIPLED_0603")
      (libsource (lib "eagle-import") (part "Robo_muscle-Diode_vf.UtgNshgcRRiQhBLyTmKZbQ_LEDRED"))
    )
    (comp (ref "D27")
      (value "RED")
      (footprint "eagle-import:CHIPLED_0603")
      (libsource (lib "eagle-import") (part "Robo_muscle-Diode_vf.UtgNshgcRRiQhBLyTmKZbQ_LEDRED"))
    )
    (comp (ref "D28")
      (value "RED")
      (footprint "eagle-import:CHIPLED_0603")
      (libsource (lib "eagle-import") (part "Robo_muscle-Diode_vf.UtgNshgcRRiQhBLyTmKZbQ_LEDRED"))
    )
    (comp (ref "D29")
      (value "RED")
      (footprint "eagle-import:CHIPLED_0603")
      (libsource (lib "eagle-import") (part "Robo_muscle-Diode_vf.UtgNshgcRRiQhBLyTmKZbQ_LEDRED"))
    )
    (comp (ref "D30")
      (value "RED")
      (footprint "eagle-import:CHIPLED_0603")
      (libsource (lib "eagle-import") (part "Robo_muscle-Diode_vf.UtgNshgcRRiQhBLyTmKZbQ_LEDRED"))
    )
    (comp (ref "D31")
      (value "RED")
      (footprint "eagle-import:CHIPLED_0603")
      (libsource (lib "eagle-import") (part "Robo_muscle-Diode_vf.UtgNshgcRRiQhBLyTmKZbQ_LEDRED"))
    )
    (comp (ref "D32")
      (value "RED")
      (footprint "eagle-import:CHIPLED_0603")
      (libsource (lib "eagle-import") (part "Robo_muscle-Diode_vf.UtgNshgcRRiQhBLyTmKZbQ_LEDRED"))
    )
    (comp (ref "D33")
      (value "RED")
      (footprint "eagle-import:CHIPLED_0603")
      (libsource (lib "eagle-import") (part "Robo_muscle-Diode_vf.UtgNshgcRRiQhBLyTmKZbQ_LEDRED"))
    )
    (comp (ref "D34")
      (value "RED")
      (footprint "eagle-import:CHIPLED_0603")
      (libsource (lib "eagle-import") (part "Robo_muscle-Diode_vf.UtgNshgcRRiQhBLyTmKZbQ_LEDRED"))
    )
    (comp (ref "D35")
      (value "RED")
      (footprint "eagle-import:CHIPLED_0603")
      (libsource (lib "eagle-import") (part "Robo_muscle-Diode_vf.UtgNshgcRRiQhBLyTmKZbQ_LEDRED"))
    )
    (comp (ref "D36")
      (value "RED")
      (footprint "eagle-import:CHIPLED_0603")
      (libsource (lib "eagle-import") (part "Robo_muscle-Diode_vf.UtgNshgcRRiQhBLyTmKZbQ_LEDRED"))
    )
    (comp (ref "D37")
      (value "RED")
      (footprint "eagle-import:CHIPLED_0603")
      (libsource (lib "eagle-import") (part "Robo_muscle-Diode_vf.UtgNshgcRRiQhBLyTmKZbQ_LEDRED"))
    )
    (comp (ref "D38")
      (value "RED")
      (footprint "eagle-import:CHIPLED_0603")
      (libsource (lib "eagle-import") (part "Robo_muscle-Diode_vf.UtgNshgcRRiQhBLyTmKZbQ_LEDRED"))
    )
    (comp (ref "D39")
      (value "RED")
      (footprint "eagle-import:CHIPLED_0603")
      (libsource (lib "eagle-import") (part "Robo_muscle-Diode_vf.UtgNshgcRRiQhBLyTmKZbQ_LEDRED"))
    )
    (comp (ref "D40")
      (value "RED")
      (footprint "eagle-import:CHIPLED_0603")
      (libsource (lib "eagle-import") (part "Robo_muscle-Diode_vf.UtgNshgcRRiQhBLyTmKZbQ_LEDRED"))
    )
    (comp (ref "D41")
      (value "RED")
      (footprint "eagle-import:CHIPLED_0603")
      (libsource (lib "eagle-import") (part "Robo_muscle-Diode_vf.UtgNshgcRRiQhBLyTmKZbQ_LEDRED"))
    )
    (comp (ref "D42")
      (value "RED")
      (footprint "eagle-import:CHIPLED_0603")
      (libsource (lib "eagle-import") (part "Robo_muscle-Diode_vf.UtgNshgcRRiQhBLyTmKZbQ_LEDRED"))
    )
    (comp (ref "D43")
      (value "RED")
      (footprint "eagle-import:CHIPLED_0603")
      (libsource (lib "eagle-import") (part "Robo_muscle-Diode_vf.UtgNshgcRRiQhBLyTmKZbQ_LEDRED"))
    )
    (comp (ref "D44")
      (value "RED")
      (footprint "eagle-import:CHIPLED_0603")
      (libsource (lib "eagle-import") (part "Robo_muscle-Diode_vf.UtgNshgcRRiQhBLyTmKZbQ_LEDRED"))
    )
    (comp (ref "D45")
      (value "RED")
      (footprint "eagle-import:CHIPLED_0603")
      (libsource (lib "eagle-import") (part "Robo_muscle-Diode_vf.UtgNshgcRRiQhBLyTmKZbQ_LEDRED"))
    )
    (comp (ref "D46")
      (value "RED")
      (footprint "eagle-import:CHIPLED_0603")
      (libsource (lib "eagle-import") (part "Robo_muscle-Diode_vf.UtgNshgcRRiQhBLyTmKZbQ_LEDRED"))
    )
    (comp (ref "D47")
      (value "RED")
      (footprint "eagle-import:CHIPLED_0603")
      (libsource (lib "eagle-import") (part "Robo_muscle-Diode_vf.UtgNshgcRRiQhBLyTmKZbQ_LEDRED"))
    )
    (comp (ref "D48")
      (value "RED")
      (footprint "eagle-import:CHIPLED_0603")
      (libsource (lib "eagle-import") (part "Robo_muscle-Diode_vf.UtgNshgcRRiQhBLyTmKZbQ_LEDRED"))
    )
    (comp (ref "D49")
      (value "RED")
      (footprint "eagle-import:CHIPLED_0603")
      (libsource (lib "eagle-import") (part "Robo_muscle-Diode_vf.UtgNshgcRRiQhBLyTmKZbQ_LEDRED"))
    )
    (comp (ref "D50")
      (value "RED")
      (footprint "eagle-import:CHIPLED_0603")
      (libsource (lib "eagle-import") (part "Robo_muscle-Diode_vf.UtgNshgcRRiQhBLyTmKZbQ_LEDRED"))
    )
    (comp (ref "D51")
      (value "RED")
      (footprint "eagle-import:CHIPLED_0603")
      (libsource (lib "eagle-import") (part "Robo_muscle-Diode_vf.UtgNshgcRRiQhBLyTmKZbQ_LEDRED"))
    )
    (comp (ref "D52")
      (value "RED")
      (footprint "eagle-import:CHIPLED_0603")
      (libsource (lib "eagle-import") (part "Robo_muscle-Diode_vf.UtgNshgcRRiQhBLyTmKZbQ_LEDRED"))
    )
    (comp (ref "D53")
      (value "RED")
      (footprint "eagle-import:CHIPLED_0603")
      (libsource (lib "eagle-import") (part "Robo_muscle-Diode_vf.UtgNshgcRRiQhBLyTmKZbQ_LEDRED"))
    )
    (comp (ref "D54")
      (value "RED")
      (footprint "eagle-import:CHIPLED_0603")
      (libsource (lib "eagle-import") (part "Robo_muscle-Diode_vf.UtgNshgcRRiQhBLyTmKZbQ_LEDRED"))
    )
    (comp (ref "D55")
      (value "RED")
      (footprint "eagle-import:CHIPLED_0603")
      (libsource (lib "eagle-import") (part "Robo_muscle-Diode_vf.UtgNshgcRRiQhBLyTmKZbQ_LEDRED"))
    )
    (comp (ref "D56")
      (value "RED")
      (footprint "eagle-import:CHIPLED_0603")
      (libsource (lib "eagle-import") (part "Robo_muscle-Diode_vf.UtgNshgcRRiQhBLyTmKZbQ_LEDRED"))
    )
    (comp (ref "D57")
      (value "RED")
      (footprint "eagle-import:CHIPLED_0603")
      (libsource (lib "eagle-import") (part "Robo_muscle-Diode_vf.UtgNshgcRRiQhBLyTmKZbQ_LEDRED"))
    )
    (comp (ref "D58")
      (value "RED")
      (footprint "eagle-import:CHIPLED_0603")
      (libsource (lib "eagle-import") (part "Robo_muscle-Diode_vf.UtgNshgcRRiQhBLyTmKZbQ_LEDRED"))
    )
    (comp (ref "D59")
      (value "RED")
      (footprint "eagle-import:CHIPLED_0603")
      (libsource (lib "eagle-import") (part "Robo_muscle-Diode_vf.UtgNshgcRRiQhBLyTmKZbQ_LEDRED"))
    )
    (comp (ref "D60")
      (value "RED")
      (footprint "eagle-import:CHIPLED_0603")
      (libsource (lib "eagle-import") (part "Robo_muscle-Diode_vf.UtgNshgcRRiQhBLyTmKZbQ_LEDRED"))
    )
    (comp (ref "D61")
      (value "RED")
      (footprint "eagle-import:CHIPLED_0603")
      (libsource (lib "eagle-import") (part "Robo_muscle-Diode_vf.UtgNshgcRRiQhBLyTmKZbQ_LEDRED"))
    )
    (comp (ref "D62")
      (value "RED")
      (footprint "eagle-import:CHIPLED_0603")
      (libsource (lib "eagle-import") (part "Robo_muscle-Diode_vf.UtgNshgcRRiQhBLyTmKZbQ_LEDRED"))
    )
    (comp (ref "D63")
      (value "RED")
      (footprint "eagle-import:CHIPLED_0603")
      (libsource (lib "eagle-import") (part "Robo_muscle-Diode_vf.UtgNshgcRRiQhBLyTmKZbQ_LEDRED"))
    )
    (comp (ref "D64")
      (value "RED")
      (footprint "eagle-import:CHIPLED_0603")
      (libsource (lib "eagle-import") (part "Robo_muscle-Diode_vf.UtgNshgcRRiQhBLyTmKZbQ_LEDRED"))
    )
    (comp (ref "D65")
      (value "RED")
      (footprint "eagle-import:CHIPLED_0603")
      (libsource (lib "eagle-import") (part "Robo_muscle-Diode_vf.UtgNshgcRRiQhBLyTmKZbQ_LEDRED"))
    )
    (comp (ref "D66")
      (value "RED")
      (footprint "eagle-import:CHIPLED_0603")
      (libsource (lib "eagle-import") (part "Robo_muscle-Diode_vf.UtgNshgcRRiQhBLyTmKZbQ_LEDRED"))
    )
    (comp (ref "D67")
      (value "RED")
      (footprint "eagle-import:CHIPLED_0603")
      (libsource (lib "eagle-import") (part "Robo_muscle-Diode_vf.UtgNshgcRRiQhBLyTmKZbQ_LEDRED"))
    )
    (comp (ref "D68")
      (value "RED")
      (footprint "eagle-import:CHIPLED_0603")
      (libsource (lib "eagle-import") (part "Robo_muscle-Diode_vf.UtgNshgcRRiQhBLyTmKZbQ_LEDRED"))
    )
    (comp (ref "D69")
      (value "RED")
      (footprint "eagle-import:CHIPLED_0603")
      (libsource (lib "eagle-import") (part "Robo_muscle-Diode_vf.UtgNshgcRRiQhBLyTmKZbQ_LEDRED"))
    )
    (comp (ref "D70")
      (value "RED")
      (footprint "eagle-import:CHIPLED_0603")
      (libsource (lib "eagle-import") (part "Robo_muscle-Diode_vf.UtgNshgcRRiQhBLyTmKZbQ_LEDRED"))
    )
    (comp (ref "D71")
      (value "RED")
      (footprint "eagle-import:CHIPLED_0603")
      (libsource (lib "eagle-import") (part "Robo_muscle-Diode_vf.UtgNshgcRRiQhBLyTmKZbQ_LEDRED"))
    )
    (comp (ref "D72")
      (value "RED")
      (footprint "eagle-import:CHIPLED_0603")
      (libsource (lib "eagle-import") (part "Robo_muscle-Diode_vf.UtgNshgcRRiQhBLyTmKZbQ_LEDRED"))
    )
    (comp (ref "DEBUG_UART")
      (value "S4B-XH-A")
      (footprint "eagle-import:S4B-XH-A")
      (libsource (lib "eagle-import") (part "S4B-XH-A"))
    )
    (comp (ref "IC1")
      (value "AZ1117CH-3.3TRG1")
      (footprint "eagle-import:SOT230P700X180-4N")
      (fields (field (name "MOUSER_PART_NUMBER") "621-AZ1117CH-3.3TRG1"))
      (libsource (lib "eagle-import") (part "AZ1117CH-3.3TRG1"))
    )
    (comp (ref "IC2")
      (value "LM393DR2G")
      (footprint "eagle-import:SOIC127P600X175-8N")
      (libsource (lib "eagle-import") (part "LM393DR2G"))
    )
    (comp (ref "IC3")
      (value "LM393DR2G")
      (footprint "eagle-import:SOIC127P600X175-8N")
      (libsource (lib "eagle-import") (part "LM393DR2G"))
    )
    (comp (ref "IC5")
      (value "LM393DR2G")
      (footprint "eagle-import:SOIC127P600X175-8N")
      (libsource (lib "eagle-import") (part "LM393DR2G"))
    )
    (comp (ref "IC6")
      (value "LM393DR2G")
      (footprint "eagle-import:SOIC127P600X175-8N")
      (libsource (lib "eagle-import") (part "LM393DR2G"))
    )
    (comp (ref "IC8")
      (value "LM393DR2G")
      (footprint "eagle-import:SOIC127P600X175-8N")
      (libsource (lib "eagle-import") (part "LM393DR2G"))
    )
    (comp (ref "IC9")
      (value "LM393DR2G")
      (footprint "eagle-import:SOIC127P600X175-8N")
      (libsource (lib "eagle-import") (part "LM393DR2G"))
    )
    (comp (ref "IC11")
      (value "LM393DR2G")
      (footprint "eagle-import:SOIC127P600X175-8N")
      (libsource (lib "eagle-import") (part "LM393DR2G"))
    )
    (comp (ref "IC12")
      (value "LM393DR2G")
      (footprint "eagle-import:SOIC127P600X175-8N")
      (libsource (lib "eagle-import") (part "LM393DR2G"))
    )
    (comp (ref "IC13")
      (value "LM393DR2G")
      (footprint "eagle-import:SOIC127P600X175-8N")
      (libsource (lib "eagle-import") (part "LM393DR2G"))
    )
    (comp (ref "IC14")
      (value "LM393DR2G")
      (footprint "eagle-import:SOIC127P600X175-8N")
      (libsource (lib "eagle-import") (part "LM393DR2G"))
    )
    (comp (ref "IC15")
      (value "LM393DR2G")
      (footprint "eagle-import:SOIC127P600X175-8N")
      (libsource (lib "eagle-import") (part "LM393DR2G"))
    )
    (comp (ref "IC16")
      (value "LM393DR2G")
      (footprint "eagle-import:SOIC127P600X175-8N")
      (libsource (lib "eagle-import") (part "LM393DR2G"))
    )
    (comp (ref "IC17")
      (value "LM393DR2G")
      (footprint "eagle-import:SOIC127P600X175-8N")
      (libsource (lib "eagle-import") (part "LM393DR2G"))
    )
    (comp (ref "IC18")
      (value "LM393DR2G")
      (footprint "eagle-import:SOIC127P600X175-8N")
      (libsource (lib "eagle-import") (part "LM393DR2G"))
    )
    (comp (ref "IC19")
      (value "LM393DR2G")
      (footprint "eagle-import:SOIC127P600X175-8N")
      (libsource (lib "eagle-import") (part "LM393DR2G"))
    )
    (comp (ref "IC20")
      (value "LM393DR2G")
      (footprint "eagle-import:SOIC127P600X175-8N")
      (libsource (lib "eagle-import") (part "LM393DR2G"))
    )
    (comp (ref "IC21")
      (value "LM393DR2G")
      (footprint "eagle-import:SOIC127P600X175-8N")
      (libsource (lib "eagle-import") (part "LM393DR2G"))
    )
    (comp (ref "IC22")
      (value "LM393DR2G")
      (footprint "eagle-import:SOIC127P600X175-8N")
      (libsource (lib "eagle-import") (part "LM393DR2G"))
    )
    (comp (ref "IC23")
      (value "LM393DR2G")
      (footprint "eagle-import:SOIC127P600X175-8N")
      (libsource (lib "eagle-import") (part "LM393DR2G"))
    )
    (comp (ref "IC24")
      (value "LM393DR2G")
      (footprint "eagle-import:SOIC127P600X175-8N")
      (libsource (lib "eagle-import") (part "LM393DR2G"))
    )
    (comp (ref "IC25")
      (value "LM393DR2G")
      (footprint "eagle-import:SOIC127P600X175-8N")
      (libsource (lib "eagle-import") (part "LM393DR2G"))
    )
    (comp (ref "IC26")
      (value "LM393DR2G")
      (footprint "eagle-import:SOIC127P600X175-8N")
      (libsource (lib "eagle-import") (part "LM393DR2G"))
    )
    (comp (ref "IC27")
      (value "LM393DR2G")
      (footprint "eagle-import:SOIC127P600X175-8N")
      (libsource (lib "eagle-import") (part "LM393DR2G"))
    )
    (comp (ref "IC28")
      (value "LM393DR2G")
      (footprint "eagle-import:SOIC127P600X175-8N")
      (libsource (lib "eagle-import") (part "LM393DR2G"))
    )
    (comp (ref "IC29")
      (value "LM393DR2G")
      (footprint "eagle-import:SOIC127P600X175-8N")
      (libsource (lib "eagle-import") (part "LM393DR2G"))
    )
    (comp (ref "IC30")
      (value "LM393DR2G")
      (footprint "eagle-import:SOIC127P600X175-8N")
      (libsource (lib "eagle-import") (part "LM393DR2G"))
    )
    (comp (ref "IC31")
      (value "LM393DR2G")
      (footprint "eagle-import:SOIC127P600X175-8N")
      (libsource (lib "eagle-import") (part "LM393DR2G"))
    )
    (comp (ref "IC32")
      (value "LM393DR2G")
      (footprint "eagle-import:SOIC127P600X175-8N")
      (libsource (lib "eagle-import") (part "LM393DR2G"))
    )
    (comp (ref "IC33")
      (value "LM393DR2G")
      (footprint "eagle-import:SOIC127P600X175-8N")
      (libsource (lib "eagle-import") (part "LM393DR2G"))
    )
    (comp (ref "IC34")
      (value "LM393DR2G")
      (footprint "eagle-import:SOIC127P600X175-8N")
      (libsource (lib "eagle-import") (part "LM393DR2G"))
    )
    (comp (ref "J2")
      (value "JST-XH-2PIN")
      (footprint "eagle-import:B2B-XH-A")
      (fields
        (field (name "MANUFACTURER") "JST Sales America Inc. ")
        (field (name "MPN") "B2B-XH-A(LF)(SN) ")
      )
      (libsource (lib "eagle-import") (part "B2B-XH-A"))
    )
    (comp (ref "LED1")
      (value "WS2812B-B")
      (footprint "eagle-import:WS2812BB")
      (libsource (lib "eagle-import") (part "WS2812B-B"))
    )
    (comp (ref "MCLR")
      (value "PINHD1X05L")
      (footprint "eagle-import:1X05L")
      (libsource (lib "eagle-import") (part "PINHD1X05L"))
    )
    (comp (ref "PIC32MK1024MCM100")
      (value "PIC32MK1024MCM100T-E_PT")
      (footprint "eagle-import:QFP40P1400X1400X120-100N")
      (fields
        (field (name "MANUFACTURER_PART_NUMBER") "PIC32MK1024MCM100T-E/PT")
        (field (name "MOUSER_PART_NUMBER") "579-1024MCM100T-E/PT")
      )
      (libsource (lib "eagle-import") (part "PIC32MK1024MCM100T-E_PT"))
    )
    (comp (ref "Q2")
      (value "BSS138")
      (footprint "eagle-import:SOT95P240X120-3N")
      (fields (field (name "MOUSER_PART_NUMBER") "512-BSS138"))
      (libsource (lib "eagle-import") (part "BSS138"))
    )
    (comp (ref "R1")
      (value "1k")
      (footprint "eagle-import:R1608")
      (libsource (lib "eagle-import") (part "RLC_vf.Zptc1PYOQp6T00ZjicgECQ_R1K/1608(0603)"))
    )
    (comp (ref "R2")
      (value "10k")
      (footprint "eagle-import:R1608")
      (libsource (lib "eagle-import") (part "RLC_vf.Zptc1PYOQp6T00ZjicgECQ_R10K/1608(0603)"))
    )
    (comp (ref "R3")
      (value "10k")
      (footprint "eagle-import:R1608")
      (libsource (lib "eagle-import") (part "RLC_vf.Zptc1PYOQp6T00ZjicgECQ_R10K/1608(0603)"))
    )
    (comp (ref "R4")
      (value "10k")
      (footprint "eagle-import:R1608")
      (libsource (lib "eagle-import") (part "RLC_vf.Zptc1PYOQp6T00ZjicgECQ_R10K/1608(0603)"))
    )
    (comp (ref "R5")
      (value "3.8k")
      (footprint "eagle-import:R1608")
      (libsource (lib "eagle-import") (part "RLC_vf.Zptc1PYOQp6T00ZjicgECQ_R1K/1608(0603)"))
    )
    (comp (ref "R6")
      (value "10k")
      (footprint "eagle-import:R1608")
      (libsource (lib "eagle-import") (part "RLC_vf.Zptc1PYOQp6T00ZjicgECQ_R10K/1608(0603)"))
    )
    (comp (ref "R7")
      (value "10k")
      (footprint "eagle-import:R1608")
      (libsource (lib "eagle-import") (part "RLC_vf.Zptc1PYOQp6T00ZjicgECQ_R10K/1608(0603)"))
    )
    (comp (ref "R8")
      (value "10k")
      (footprint "eagle-import:R1608")
      (libsource (lib "eagle-import") (part "RLC_vf.Zptc1PYOQp6T00ZjicgECQ_R10K/1608(0603)"))
    )
    (comp (ref "R9")
      (value "10k")
      (footprint "eagle-import:R1608")
      (libsource (lib "eagle-import") (part "RLC_vf.Zptc1PYOQp6T00ZjicgECQ_R10K/1608(0603)"))
    )
    (comp (ref "R10")
      (value "10k")
      (footprint "eagle-import:R1608")
      (libsource (lib "eagle-import") (part "RLC_vf.Zptc1PYOQp6T00ZjicgECQ_R10K/1608(0603)"))
    )
    (comp (ref "R11")
      (value "10k")
      (footprint "eagle-import:R1608")
      (libsource (lib "eagle-import") (part "RLC_vf.Zptc1PYOQp6T00ZjicgECQ_R10K/1608(0603)"))
    )
    (comp (ref "R12")
      (value "10k")
      (footprint "eagle-import:R1608")
      (libsource (lib "eagle-import") (part "RLC_vf.Zptc1PYOQp6T00ZjicgECQ_R10K/1608(0603)"))
    )
    (comp (ref "R13")
      (value "10k")
      (footprint "eagle-import:R1608")
      (libsource (lib "eagle-import") (part "RLC_vf.Zptc1PYOQp6T00ZjicgECQ_R10K/1608(0603)"))
    )
    (comp (ref "R14")
      (value "10k")
      (footprint "eagle-import:R1608")
      (libsource (lib "eagle-import") (part "RLC_vf.Zptc1PYOQp6T00ZjicgECQ_R10K/1608(0603)"))
    )
    (comp (ref "R15")
      (value "10k")
      (footprint "eagle-import:R1608")
      (libsource (lib "eagle-import") (part "RLC_vf.Zptc1PYOQp6T00ZjicgECQ_R10K/1608(0603)"))
    )
    (comp (ref "R16")
      (value "10k")
      (footprint "eagle-import:R1608")
      (libsource (lib "eagle-import") (part "RLC_vf.Zptc1PYOQp6T00ZjicgECQ_R10K/1608(0603)"))
    )
    (comp (ref "R17")
      (value "10k")
      (footprint "eagle-import:R1608")
      (libsource (lib "eagle-import") (part "RLC_vf.Zptc1PYOQp6T00ZjicgECQ_R10K/1608(0603)"))
    )
    (comp (ref "R18")
      (value "220")
      (footprint "eagle-import:R1608")
      (libsource (lib "eagle-import") (part "R220/1608(0603)"))
    )
    (comp (ref "R19")
      (value "220")
      (footprint "eagle-import:R1608")
      (libsource (lib "eagle-import") (part "R220/1608(0603)"))
    )
    (comp (ref "R20")
      (value "220")
      (footprint "eagle-import:R1608")
      (libsource (lib "eagle-import") (part "R220/1608(0603)"))
    )
    (comp (ref "R21")
      (value "10k")
      (footprint "eagle-import:R1608")
      (libsource (lib "eagle-import") (part "RLC_vf.Zptc1PYOQp6T00ZjicgECQ_R10K/1608(0603)"))
    )
    (comp (ref "R22")
      (value "10k")
      (footprint "eagle-import:R1608")
      (libsource (lib "eagle-import") (part "RLC_vf.Zptc1PYOQp6T00ZjicgECQ_R10K/1608(0603)"))
    )
    (comp (ref "R23")
      (value "220")
      (footprint "eagle-import:R1608")
      (libsource (lib "eagle-import") (part "R220/1608(0603)"))
    )
    (comp (ref "R24")
      (value "220")
      (footprint "eagle-import:R1608")
      (libsource (lib "eagle-import") (part "R220/1608(0603)"))
    )
    (comp (ref "R25")
      (value "220")
      (footprint "eagle-import:R1608")
      (libsource (lib "eagle-import") (part "R220/1608(0603)"))
    )
    (comp (ref "R26")
      (value "220")
      (footprint "eagle-import:R1608")
      (libsource (lib "eagle-import") (part "R220/1608(0603)"))
    )
    (comp (ref "R27")
      (value "220")
      (footprint "eagle-import:R1608")
      (libsource (lib "eagle-import") (part "R220/1608(0603)"))
    )
    (comp (ref "R28")
      (value "220")
      (footprint "eagle-import:R1608")
      (libsource (lib "eagle-import") (part "R220/1608(0603)"))
    )
    (comp (ref "R29")
      (value "220")
      (footprint "eagle-import:R1608")
      (libsource (lib "eagle-import") (part "R220/1608(0603)"))
    )
    (comp (ref "R30")
      (value "220")
      (footprint "eagle-import:R1608")
      (libsource (lib "eagle-import") (part "R220/1608(0603)"))
    )
    (comp (ref "R31")
      (value "220")
      (footprint "eagle-import:R1608")
      (libsource (lib "eagle-import") (part "R220/1608(0603)"))
    )
    (comp (ref "R32")
      (value "220")
      (footprint "eagle-import:R1608")
      (libsource (lib "eagle-import") (part "R220/1608(0603)"))
    )
    (comp (ref "R33")
      (value "220")
      (footprint "eagle-import:R1608")
      (libsource (lib "eagle-import") (part "R220/1608(0603)"))
    )
    (comp (ref "R34")
      (value "220")
      (footprint "eagle-import:R1608")
      (libsource (lib "eagle-import") (part "R220/1608(0603)"))
    )
    (comp (ref "R35")
      (value "220")
      (footprint "eagle-import:R1608")
      (libsource (lib "eagle-import") (part "R220/1608(0603)"))
    )
    (comp (ref "R36")
      (value "220")
      (footprint "eagle-import:R1608")
      (libsource (lib "eagle-import") (part "R220/1608(0603)"))
    )
    (comp (ref "R37")
      (value "220")
      (footprint "eagle-import:R1608")
      (libsource (lib "eagle-import") (part "R220/1608(0603)"))
    )
    (comp (ref "R38")
      (value "220")
      (footprint "eagle-import:R1608")
      (libsource (lib "eagle-import") (part "R220/1608(0603)"))
    )
    (comp (ref "R39")
      (value "220")
      (footprint "eagle-import:R1608")
      (libsource (lib "eagle-import") (part "R220/1608(0603)"))
    )
    (comp (ref "R40")
      (value "220")
      (footprint "eagle-import:R1608")
      (libsource (lib "eagle-import") (part "R220/1608(0603)"))
    )
    (comp (ref "R41")
      (value "220")
      (footprint "eagle-import:R1608")
      (libsource (lib "eagle-import") (part "R220/1608(0603)"))
    )
    (comp (ref "R42")
      (value "220")
      (footprint "eagle-import:R1608")
      (libsource (lib "eagle-import") (part "R220/1608(0603)"))
    )
    (comp (ref "R43")
      (value "220")
      (footprint "eagle-import:R1608")
      (libsource (lib "eagle-import") (part "R220/1608(0603)"))
    )
    (comp (ref "R44")
      (value "220")
      (footprint "eagle-import:R1608")
      (libsource (lib "eagle-import") (part "R220/1608(0603)"))
    )
    (comp (ref "R45")
      (value "220")
      (footprint "eagle-import:R1608")
      (libsource (lib "eagle-import") (part "R220/1608(0603)"))
    )
    (comp (ref "R46")
      (value "220")
      (footprint "eagle-import:R1608")
      (libsource (lib "eagle-import") (part "R220/1608(0603)"))
    )
    (comp (ref "R47")
      (value "220")
      (footprint "eagle-import:R1608")
      (libsource (lib "eagle-import") (part "R220/1608(0603)"))
    )
    (comp (ref "R48")
      (value "220")
      (footprint "eagle-import:R1608")
      (libsource (lib "eagle-import") (part "R220/1608(0603)"))
    )
    (comp (ref "R49")
      (value "220")
      (footprint "eagle-import:R1608")
      (libsource (lib "eagle-import") (part "R220/1608(0603)"))
    )
    (comp (ref "R50")
      (value "220")
      (footprint "eagle-import:R1608")
      (libsource (lib "eagle-import") (part "R220/1608(0603)"))
    )
    (comp (ref "R51")
      (value "220")
      (footprint "eagle-import:R1608")
      (libsource (lib "eagle-import") (part "R220/1608(0603)"))
    )
    (comp (ref "R52")
      (value "220")
      (footprint "eagle-import:R1608")
      (libsource (lib "eagle-import") (part "R220/1608(0603)"))
    )
    (comp (ref "R53")
      (value "220")
      (footprint "eagle-import:R1608")
      (libsource (lib "eagle-import") (part "R220/1608(0603)"))
    )
    (comp (ref "R54")
      (value "220")
      (footprint "eagle-import:R1608")
      (libsource (lib "eagle-import") (part "R220/1608(0603)"))
    )
    (comp (ref "R55")
      (value "220")
      (footprint "eagle-import:R1608")
      (libsource (lib "eagle-import") (part "R220/1608(0603)"))
    )
    (comp (ref "R56")
      (value "220")
      (footprint "eagle-import:R1608")
      (libsource (lib "eagle-import") (part "R220/1608(0603)"))
    )
    (comp (ref "R57")
      (value "220")
      (footprint "eagle-import:R1608")
      (libsource (lib "eagle-import") (part "R220/1608(0603)"))
    )
    (comp (ref "R58")
      (value "220")
      (footprint "eagle-import:R1608")
      (libsource (lib "eagle-import") (part "R220/1608(0603)"))
    )
    (comp (ref "R59")
      (value "220")
      (footprint "eagle-import:R1608")
      (libsource (lib "eagle-import") (part "R220/1608(0603)"))
    )
    (comp (ref "R60")
      (value "220")
      (footprint "eagle-import:R1608")
      (libsource (lib "eagle-import") (part "R220/1608(0603)"))
    )
    (comp (ref "R61")
      (value "220")
      (footprint "eagle-import:R1608")
      (libsource (lib "eagle-import") (part "R220/1608(0603)"))
    )
    (comp (ref "R62")
      (value "220")
      (footprint "eagle-import:R1608")
      (libsource (lib "eagle-import") (part "R220/1608(0603)"))
    )
    (comp (ref "R63")
      (value "220")
      (footprint "eagle-import:R1608")
      (libsource (lib "eagle-import") (part "R220/1608(0603)"))
    )
    (comp (ref "R64")
      (value "220")
      (footprint "eagle-import:R1608")
      (libsource (lib "eagle-import") (part "R220/1608(0603)"))
    )
    (comp (ref "R65")
      (value "220")
      (footprint "eagle-import:R1608")
      (libsource (lib "eagle-import") (part "R220/1608(0603)"))
    )
    (comp (ref "R66")
      (value "220")
      (footprint "eagle-import:R1608")
      (libsource (lib "eagle-import") (part "R220/1608(0603)"))
    )
    (comp (ref "R67")
      (value "220")
      (footprint "eagle-import:R1608")
      (libsource (lib "eagle-import") (part "R220/1608(0603)"))
    )
    (comp (ref "R68")
      (value "220")
      (footprint "eagle-import:R1608")
      (libsource (lib "eagle-import") (part "R220/1608(0603)"))
    )
    (comp (ref "R69")
      (value "220")
      (footprint "eagle-import:R1608")
      (libsource (lib "eagle-import") (part "R220/1608(0603)"))
    )
    (comp (ref "R70")
      (value "220")
      (footprint "eagle-import:R1608")
      (libsource (lib "eagle-import") (part "R220/1608(0603)"))
    )
    (comp (ref "R71")
      (value "220")
      (footprint "eagle-import:R1608")
      (libsource (lib "eagle-import") (part "R220/1608(0603)"))
    )
    (comp (ref "R72")
      (value "220")
      (footprint "eagle-import:R1608")
      (libsource (lib "eagle-import") (part "R220/1608(0603)"))
    )
    (comp (ref "R73")
      (value "220")
      (footprint "eagle-import:R1608")
      (libsource (lib "eagle-import") (part "R220/1608(0603)"))
    )
    (comp (ref "R74")
      (value "220")
      (footprint "eagle-import:R1608")
      (libsource (lib "eagle-import") (part "R220/1608(0603)"))
    )
    (comp (ref "R75")
      (value "220")
      (footprint "eagle-import:R1608")
      (libsource (lib "eagle-import") (part "R220/1608(0603)"))
    )
    (comp (ref "R76")
      (value "220")
      (footprint "eagle-import:R1608")
      (libsource (lib "eagle-import") (part "R220/1608(0603)"))
    )
    (comp (ref "R77")
      (value "220")
      (footprint "eagle-import:R1608")
      (libsource (lib "eagle-import") (part "R220/1608(0603)"))
    )
    (comp (ref "R78")
      (value "220")
      (footprint "eagle-import:R1608")
      (libsource (lib "eagle-import") (part "R220/1608(0603)"))
    )
    (comp (ref "R79")
      (value "220")
      (footprint "eagle-import:R1608")
      (libsource (lib "eagle-import") (part "R220/1608(0603)"))
    )
    (comp (ref "R80")
      (value "220")
      (footprint "eagle-import:R1608")
      (libsource (lib "eagle-import") (part "R220/1608(0603)"))
    )
    (comp (ref "R81")
      (value "220")
      (footprint "eagle-import:R1608")
      (libsource (lib "eagle-import") (part "R220/1608(0603)"))
    )
    (comp (ref "R82")
      (value "64k")
      (footprint "eagle-import:R1608")
      (libsource (lib "eagle-import") (part "R64K/1608(0603)"))
    )
    (comp (ref "R83")
      (value "64k")
      (footprint "eagle-import:R1608")
      (libsource (lib "eagle-import") (part "R64K/1608(0603)"))
    )
    (comp (ref "R84")
      (value "64k")
      (footprint "eagle-import:R1608")
      (libsource (lib "eagle-import") (part "R64K/1608(0603)"))
    )
    (comp (ref "R85")
      (value "220")
      (footprint "eagle-import:R1608")
      (libsource (lib "eagle-import") (part "R220/1608(0603)"))
    )
    (comp (ref "R86")
      (value "10k")
      (footprint "eagle-import:R1608")
      (libsource (lib "eagle-import") (part "RLC_vf.Zptc1PYOQp6T00ZjicgECQ_R10K/1608(0603)"))
    )
    (comp (ref "R87")
      (value "10k")
      (footprint "eagle-import:R1608")
      (libsource (lib "eagle-import") (part "RLC_vf.Zptc1PYOQp6T00ZjicgECQ_R10K/1608(0603)"))
    )
    (comp (ref "R88")
      (value "64k")
      (footprint "eagle-import:R1608")
      (libsource (lib "eagle-import") (part "R64K/1608(0603)"))
    )
    (comp (ref "R89")
      (value "64k")
      (footprint "eagle-import:R1608")
      (libsource (lib "eagle-import") (part "R64K/1608(0603)"))
    )
    (comp (ref "R90")
      (value "64k")
      (footprint "eagle-import:R1608")
      (libsource (lib "eagle-import") (part "R64K/1608(0603)"))
    )
    (comp (ref "R91")
      (value "64k")
      (footprint "eagle-import:R1608")
      (libsource (lib "eagle-import") (part "R64K/1608(0603)"))
    )
    (comp (ref "R92")
      (value "64k")
      (footprint "eagle-import:R1608")
      (libsource (lib "eagle-import") (part "R64K/1608(0603)"))
    )
    (comp (ref "R93")
      (value "64k")
      (footprint "eagle-import:R1608")
      (libsource (lib "eagle-import") (part "R64K/1608(0603)"))
    )
    (comp (ref "R94")
      (value "64k")
      (footprint "eagle-import:R1608")
      (libsource (lib "eagle-import") (part "R64K/1608(0603)"))
    )
    (comp (ref "R95")
      (value "64k")
      (footprint "eagle-import:R1608")
      (libsource (lib "eagle-import") (part "R64K/1608(0603)"))
    )
    (comp (ref "R96")
      (value "64k")
      (footprint "eagle-import:R1608")
      (libsource (lib "eagle-import") (part "R64K/1608(0603)"))
    )
    (comp (ref "R97")
      (value "64k")
      (footprint "eagle-import:R1608")
      (libsource (lib "eagle-import") (part "R64K/1608(0603)"))
    )
    (comp (ref "R98")
      (value "64k")
      (footprint "eagle-import:R1608")
      (libsource (lib "eagle-import") (part "R64K/1608(0603)"))
    )
    (comp (ref "R99")
      (value "64k")
      (footprint "eagle-import:R1608")
      (libsource (lib "eagle-import") (part "R64K/1608(0603)"))
    )
    (comp (ref "R100")
      (value "64k")
      (footprint "eagle-import:R1608")
      (libsource (lib "eagle-import") (part "R64K/1608(0603)"))
    )
    (comp (ref "R101")
      (value "64k")
      (footprint "eagle-import:R1608")
      (libsource (lib "eagle-import") (part "R64K/1608(0603)"))
    )
    (comp (ref "R102")
      (value "64k")
      (footprint "eagle-import:R1608")
      (libsource (lib "eagle-import") (part "R64K/1608(0603)"))
    )
    (comp (ref "R103")
      (value "64k")
      (footprint "eagle-import:R1608")
      (libsource (lib "eagle-import") (part "R64K/1608(0603)"))
    )
    (comp (ref "R104")
      (value "64k")
      (footprint "eagle-import:R1608")
      (libsource (lib "eagle-import") (part "R64K/1608(0603)"))
    )
    (comp (ref "R105")
      (value "64k")
      (footprint "eagle-import:R1608")
      (libsource (lib "eagle-import") (part "R64K/1608(0603)"))
    )
    (comp (ref "R106")
      (value "64k")
      (footprint "eagle-import:R1608")
      (libsource (lib "eagle-import") (part "R64K/1608(0603)"))
    )
    (comp (ref "R107")
      (value "64k")
      (footprint "eagle-import:R1608")
      (libsource (lib "eagle-import") (part "R64K/1608(0603)"))
    )
    (comp (ref "R108")
      (value "64k")
      (footprint "eagle-import:R1608")
      (libsource (lib "eagle-import") (part "R64K/1608(0603)"))
    )
    (comp (ref "R109")
      (value "64k")
      (footprint "eagle-import:R1608")
      (libsource (lib "eagle-import") (part "R64K/1608(0603)"))
    )
    (comp (ref "R110")
      (value "64k")
      (footprint "eagle-import:R1608")
      (libsource (lib "eagle-import") (part "R64K/1608(0603)"))
    )
    (comp (ref "R111")
      (value "64k")
      (footprint "eagle-import:R1608")
      (libsource (lib "eagle-import") (part "R64K/1608(0603)"))
    )
    (comp (ref "R112")
      (value "64k")
      (footprint "eagle-import:R1608")
      (libsource (lib "eagle-import") (part "R64K/1608(0603)"))
    )
    (comp (ref "R113")
      (value "64k")
      (footprint "eagle-import:R1608")
      (libsource (lib "eagle-import") (part "R64K/1608(0603)"))
    )
    (comp (ref "R114")
      (value "64k")
      (footprint "eagle-import:R1608")
      (libsource (lib "eagle-import") (part "R64K/1608(0603)"))
    )
    (comp (ref "R115")
      (value "64k")
      (footprint "eagle-import:R1608")
      (libsource (lib "eagle-import") (part "R64K/1608(0603)"))
    )
    (comp (ref "R116")
      (value "64k")
      (footprint "eagle-import:R1608")
      (libsource (lib "eagle-import") (part "R64K/1608(0603)"))
    )
    (comp (ref "R117")
      (value "64k")
      (footprint "eagle-import:R1608")
      (libsource (lib "eagle-import") (part "R64K/1608(0603)"))
    )
    (comp (ref "R118")
      (value "64k")
      (footprint "eagle-import:R1608")
      (libsource (lib "eagle-import") (part "R64K/1608(0603)"))
    )
    (comp (ref "R119")
      (value "64k")
      (footprint "eagle-import:R1608")
      (libsource (lib "eagle-import") (part "R64K/1608(0603)"))
    )
    (comp (ref "R120")
      (value "64k")
      (footprint "eagle-import:R1608")
      (libsource (lib "eagle-import") (part "R64K/1608(0603)"))
    )
    (comp (ref "R121")
      (value "64k")
      (footprint "eagle-import:R1608")
      (libsource (lib "eagle-import") (part "R64K/1608(0603)"))
    )
    (comp (ref "R122")
      (value "64k")
      (footprint "eagle-import:R1608")
      (libsource (lib "eagle-import") (part "R64K/1608(0603)"))
    )
    (comp (ref "R123")
      (value "64k")
      (footprint "eagle-import:R1608")
      (libsource (lib "eagle-import") (part "R64K/1608(0603)"))
    )
    (comp (ref "R124")
      (value "64k")
      (footprint "eagle-import:R1608")
      (libsource (lib "eagle-import") (part "R64K/1608(0603)"))
    )
    (comp (ref "R125")
      (value "64k")
      (footprint "eagle-import:R1608")
      (libsource (lib "eagle-import") (part "R64K/1608(0603)"))
    )
    (comp (ref "R126")
      (value "64k")
      (footprint "eagle-import:R1608")
      (libsource (lib "eagle-import") (part "R64K/1608(0603)"))
    )
    (comp (ref "R127")
      (value "64k")
      (footprint "eagle-import:R1608")
      (libsource (lib "eagle-import") (part "R64K/1608(0603)"))
    )
    (comp (ref "R128")
      (value "64k")
      (footprint "eagle-import:R1608")
      (libsource (lib "eagle-import") (part "R64K/1608(0603)"))
    )
    (comp (ref "R129")
      (value "64k")
      (footprint "eagle-import:R1608")
      (libsource (lib "eagle-import") (part "R64K/1608(0603)"))
    )
    (comp (ref "R130")
      (value "64k")
      (footprint "eagle-import:R1608")
      (libsource (lib "eagle-import") (part "R64K/1608(0603)"))
    )
    (comp (ref "R131")
      (value "64k")
      (footprint "eagle-import:R1608")
      (libsource (lib "eagle-import") (part "R64K/1608(0603)"))
    )
    (comp (ref "R132")
      (value "64k")
      (footprint "eagle-import:R1608")
      (libsource (lib "eagle-import") (part "R64K/1608(0603)"))
    )
    (comp (ref "R133")
      (value "64k")
      (footprint "eagle-import:R1608")
      (libsource (lib "eagle-import") (part "R64K/1608(0603)"))
    )
    (comp (ref "R134")
      (value "64k")
      (footprint "eagle-import:R1608")
      (libsource (lib "eagle-import") (part "R64K/1608(0603)"))
    )
    (comp (ref "R135")
      (value "64k")
      (footprint "eagle-import:R1608")
      (libsource (lib "eagle-import") (part "R64K/1608(0603)"))
    )
    (comp (ref "R136")
      (value "64k")
      (footprint "eagle-import:R1608")
      (libsource (lib "eagle-import") (part "R64K/1608(0603)"))
    )
    (comp (ref "R137")
      (value "64k")
      (footprint "eagle-import:R1608")
      (libsource (lib "eagle-import") (part "R64K/1608(0603)"))
    )
    (comp (ref "R138")
      (value "64k")
      (footprint "eagle-import:R1608")
      (libsource (lib "eagle-import") (part "R64K/1608(0603)"))
    )
    (comp (ref "R139")
      (value "64k")
      (footprint "eagle-import:R1608")
      (libsource (lib "eagle-import") (part "R64K/1608(0603)"))
    )
    (comp (ref "R140")
      (value "64k")
      (footprint "eagle-import:R1608")
      (libsource (lib "eagle-import") (part "R64K/1608(0603)"))
    )
    (comp (ref "R141")
      (value "64k")
      (footprint "eagle-import:R1608")
      (libsource (lib "eagle-import") (part "R64K/1608(0603)"))
    )
    (comp (ref "R142")
      (value "64k")
      (footprint "eagle-import:R1608")
      (libsource (lib "eagle-import") (part "R64K/1608(0603)"))
    )
    (comp (ref "R143")
      (value "10k")
      (footprint "eagle-import:R1608")
      (libsource (lib "eagle-import") (part "RLC_vf.Zptc1PYOQp6T00ZjicgECQ_R10K/1608(0603)"))
    )
    (comp (ref "R144")
      (value "64k")
      (footprint "eagle-import:R1608")
      (libsource (lib "eagle-import") (part "R64K/1608(0603)"))
    )
    (comp (ref "R145")
      (value "220")
      (footprint "eagle-import:R1608")
      (libsource (lib "eagle-import") (part "R220/1608(0603)"))
    )
    (comp (ref "R146")
      (value "10k")
      (footprint "eagle-import:R1608")
      (libsource (lib "eagle-import") (part "RLC_vf.Zptc1PYOQp6T00ZjicgECQ_R10K/1608(0603)"))
    )
    (comp (ref "R147")
      (value "10k")
      (footprint "eagle-import:R1608")
      (libsource (lib "eagle-import") (part "RLC_vf.Zptc1PYOQp6T00ZjicgECQ_R10K/1608(0603)"))
    )
    (comp (ref "R148")
      (value "10k")
      (footprint "eagle-import:R1608")
      (libsource (lib "eagle-import") (part "RLC_vf.Zptc1PYOQp6T00ZjicgECQ_R10K/1608(0603)"))
    )
    (comp (ref "R149")
      (value "10k")
      (footprint "eagle-import:R1608")
      (libsource (lib "eagle-import") (part "RLC_vf.Zptc1PYOQp6T00ZjicgECQ_R10K/1608(0603)"))
    )
    (comp (ref "R150")
      (value "10k")
      (footprint "eagle-import:R1608")
      (libsource (lib "eagle-import") (part "RLC_vf.Zptc1PYOQp6T00ZjicgECQ_R10K/1608(0603)"))
    )
    (comp (ref "R151")
      (value "10k")
      (footprint "eagle-import:R1608")
      (libsource (lib "eagle-import") (part "RLC_vf.Zptc1PYOQp6T00ZjicgECQ_R10K/1608(0603)"))
    )
    (comp (ref "R152")
      (value "10k")
      (footprint "eagle-import:R1608")
      (libsource (lib "eagle-import") (part "RLC_vf.Zptc1PYOQp6T00ZjicgECQ_R10K/1608(0603)"))
    )
    (comp (ref "R153")
      (value "10k")
      (footprint "eagle-import:R1608")
      (libsource (lib "eagle-import") (part "RLC_vf.Zptc1PYOQp6T00ZjicgECQ_R10K/1608(0603)"))
    )
    (comp (ref "R154")
      (value "10k")
      (footprint "eagle-import:R1608")
      (libsource (lib "eagle-import") (part "RLC_vf.Zptc1PYOQp6T00ZjicgECQ_R10K/1608(0603)"))
    )
    (comp (ref "R155")
      (value "10k")
      (footprint "eagle-import:R1608")
      (libsource (lib "eagle-import") (part "RLC_vf.Zptc1PYOQp6T00ZjicgECQ_R10K/1608(0603)"))
    )
    (comp (ref "R156")
      (value "10k")
      (footprint "eagle-import:R1608")
      (libsource (lib "eagle-import") (part "RLC_vf.Zptc1PYOQp6T00ZjicgECQ_R10K/1608(0603)"))
    )
    (comp (ref "R157")
      (value "10k")
      (footprint "eagle-import:R1608")
      (libsource (lib "eagle-import") (part "RLC_vf.Zptc1PYOQp6T00ZjicgECQ_R10K/1608(0603)"))
    )
    (comp (ref "R158")
      (value "10k")
      (footprint "eagle-import:R1608")
      (libsource (lib "eagle-import") (part "RLC_vf.Zptc1PYOQp6T00ZjicgECQ_R10K/1608(0603)"))
    )
    (comp (ref "R159")
      (value "10k")
      (footprint "eagle-import:R1608")
      (libsource (lib "eagle-import") (part "RLC_vf.Zptc1PYOQp6T00ZjicgECQ_R10K/1608(0603)"))
    )
    (comp (ref "R160")
      (value "10k")
      (footprint "eagle-import:R1608")
      (libsource (lib "eagle-import") (part "RLC_vf.Zptc1PYOQp6T00ZjicgECQ_R10K/1608(0603)"))
    )
    (comp (ref "R161")
      (value "10k")
      (footprint "eagle-import:R1608")
      (libsource (lib "eagle-import") (part "RLC_vf.Zptc1PYOQp6T00ZjicgECQ_R10K/1608(0603)"))
    )
    (comp (ref "R162")
      (value "10k")
      (footprint "eagle-import:R1608")
      (libsource (lib "eagle-import") (part "RLC_vf.Zptc1PYOQp6T00ZjicgECQ_R10K/1608(0603)"))
    )
    (comp (ref "R163")
      (value "10k")
      (footprint "eagle-import:R1608")
      (libsource (lib "eagle-import") (part "RLC_vf.Zptc1PYOQp6T00ZjicgECQ_R10K/1608(0603)"))
    )
    (comp (ref "R164")
      (value "10k")
      (footprint "eagle-import:R1608")
      (libsource (lib "eagle-import") (part "RLC_vf.Zptc1PYOQp6T00ZjicgECQ_R10K/1608(0603)"))
    )
    (comp (ref "R165")
      (value "10k")
      (footprint "eagle-import:R1608")
      (libsource (lib "eagle-import") (part "RLC_vf.Zptc1PYOQp6T00ZjicgECQ_R10K/1608(0603)"))
    )
    (comp (ref "R166")
      (value "10k")
      (footprint "eagle-import:R1608")
      (libsource (lib "eagle-import") (part "RLC_vf.Zptc1PYOQp6T00ZjicgECQ_R10K/1608(0603)"))
    )
    (comp (ref "R167")
      (value "10k")
      (footprint "eagle-import:R1608")
      (libsource (lib "eagle-import") (part "RLC_vf.Zptc1PYOQp6T00ZjicgECQ_R10K/1608(0603)"))
    )
    (comp (ref "R168")
      (value "10k")
      (footprint "eagle-import:R1608")
      (libsource (lib "eagle-import") (part "RLC_vf.Zptc1PYOQp6T00ZjicgECQ_R10K/1608(0603)"))
    )
    (comp (ref "R169")
      (value "10k")
      (footprint "eagle-import:R1608")
      (libsource (lib "eagle-import") (part "RLC_vf.Zptc1PYOQp6T00ZjicgECQ_R10K/1608(0603)"))
    )
    (comp (ref "R170")
      (value "10k")
      (footprint "eagle-import:R1608")
      (libsource (lib "eagle-import") (part "RLC_vf.Zptc1PYOQp6T00ZjicgECQ_R10K/1608(0603)"))
    )
    (comp (ref "R171")
      (value "10k")
      (footprint "eagle-import:R1608")
      (libsource (lib "eagle-import") (part "RLC_vf.Zptc1PYOQp6T00ZjicgECQ_R10K/1608(0603)"))
    )
    (comp (ref "R172")
      (value "220")
      (footprint "eagle-import:R1608")
      (libsource (lib "eagle-import") (part "R220/1608(0603)"))
    )
    (comp (ref "R173")
      (value "220")
      (footprint "eagle-import:R1608")
      (libsource (lib "eagle-import") (part "R220/1608(0603)"))
    )
    (comp (ref "R174")
      (value "10k")
      (footprint "eagle-import:R1608")
      (libsource (lib "eagle-import") (part "RLC_vf.Zptc1PYOQp6T00ZjicgECQ_R10K/1608(0603)"))
    )
    (comp (ref "R175")
      (value "10k")
      (footprint "eagle-import:R1608")
      (libsource (lib "eagle-import") (part "RLC_vf.Zptc1PYOQp6T00ZjicgECQ_R10K/1608(0603)"))
    )
    (comp (ref "R176")
      (value "10k")
      (footprint "eagle-import:R1608")
      (libsource (lib "eagle-import") (part "RLC_vf.Zptc1PYOQp6T00ZjicgECQ_R10K/1608(0603)"))
    )
    (comp (ref "R177")
      (value "10k")
      (footprint "eagle-import:R1608")
      (libsource (lib "eagle-import") (part "RLC_vf.Zptc1PYOQp6T00ZjicgECQ_R10K/1608(0603)"))
    )
    (comp (ref "R178")
      (value "10k")
      (footprint "eagle-import:R1608")
      (libsource (lib "eagle-import") (part "RLC_vf.Zptc1PYOQp6T00ZjicgECQ_R10K/1608(0603)"))
    )
    (comp (ref "R180")
      (value "10k")
      (footprint "eagle-import:R1608")
      (libsource (lib "eagle-import") (part "RLC_vf.Zptc1PYOQp6T00ZjicgECQ_R10K/1608(0603)"))
    )
    (comp (ref "R181")
      (value "10k")
      (footprint "eagle-import:R1608")
      (libsource (lib "eagle-import") (part "RLC_vf.Zptc1PYOQp6T00ZjicgECQ_R10K/1608(0603)"))
    )
    (comp (ref "R182")
      (value "10k")
      (footprint "eagle-import:R1608")
      (libsource (lib "eagle-import") (part "RLC_vf.Zptc1PYOQp6T00ZjicgECQ_R10K/1608(0603)"))
    )
    (comp (ref "R183")
      (value "10k")
      (footprint "eagle-import:R1608")
      (libsource (lib "eagle-import") (part "RLC_vf.Zptc1PYOQp6T00ZjicgECQ_R10K/1608(0603)"))
    )
    (comp (ref "R184")
      (value "10k")
      (footprint "eagle-import:R1608")
      (libsource (lib "eagle-import") (part "RLC_vf.Zptc1PYOQp6T00ZjicgECQ_R10K/1608(0603)"))
    )
    (comp (ref "R186")
      (value "10k")
      (footprint "eagle-import:R1608")
      (libsource (lib "eagle-import") (part "RLC_vf.Zptc1PYOQp6T00ZjicgECQ_R10K/1608(0603)"))
    )
    (comp (ref "R187")
      (value "10k")
      (footprint "eagle-import:R1608")
      (libsource (lib "eagle-import") (part "RLC_vf.Zptc1PYOQp6T00ZjicgECQ_R10K/1608(0603)"))
    )
    (comp (ref "R189")
      (value "10k")
      (footprint "eagle-import:R1608")
      (libsource (lib "eagle-import") (part "RLC_vf.Zptc1PYOQp6T00ZjicgECQ_R10K/1608(0603)"))
    )
    (comp (ref "R190")
      (value "10k")
      (footprint "eagle-import:R1608")
      (libsource (lib "eagle-import") (part "RLC_vf.Zptc1PYOQp6T00ZjicgECQ_R10K/1608(0603)"))
    )
    (comp (ref "R191")
      (value "10k")
      (footprint "eagle-import:R1608")
      (libsource (lib "eagle-import") (part "RLC_vf.Zptc1PYOQp6T00ZjicgECQ_R10K/1608(0603)"))
    )
    (comp (ref "R192")
      (value "10k")
      (footprint "eagle-import:R1608")
      (libsource (lib "eagle-import") (part "RLC_vf.Zptc1PYOQp6T00ZjicgECQ_R10K/1608(0603)"))
    )
    (comp (ref "R194")
      (value "10k")
      (footprint "eagle-import:R1608")
      (libsource (lib "eagle-import") (part "RLC_vf.Zptc1PYOQp6T00ZjicgECQ_R10K/1608(0603)"))
    )
    (comp (ref "R195")
      (value "10k")
      (footprint "eagle-import:R1608")
      (libsource (lib "eagle-import") (part "RLC_vf.Zptc1PYOQp6T00ZjicgECQ_R10K/1608(0603)"))
    )
    (comp (ref "R196")
      (value "64k")
      (footprint "eagle-import:R1608")
      (libsource (lib "eagle-import") (part "R64K/1608(0603)"))
    )
    (comp (ref "R197")
      (value "10k")
      (footprint "eagle-import:R1608")
      (libsource (lib "eagle-import") (part "RLC_vf.Zptc1PYOQp6T00ZjicgECQ_R10K/1608(0603)"))
    )
    (comp (ref "R198")
      (value "220")
      (footprint "eagle-import:R1608")
      (libsource (lib "eagle-import") (part "R220/1608(0603)"))
    )
    (comp (ref "R199")
      (value "220")
      (footprint "eagle-import:R1608")
      (libsource (lib "eagle-import") (part "R220/1608(0603)"))
    )
    (comp (ref "R200")
      (value "220")
      (footprint "eagle-import:R1608")
      (libsource (lib "eagle-import") (part "R220/1608(0603)"))
    )
    (comp (ref "R205")
      (value "220")
      (footprint "eagle-import:R1608")
      (libsource (lib "eagle-import") (part "R220/1608(0603)"))
    )
    (comp (ref "R206")
      (value "10k")
      (footprint "eagle-import:R1608")
      (libsource (lib "eagle-import") (part "RLC_vf.Zptc1PYOQp6T00ZjicgECQ_R10K/1608(0603)"))
    )
    (comp (ref "R207")
      (value "10k")
      (footprint "eagle-import:R1608")
      (libsource (lib "eagle-import") (part "RLC_vf.Zptc1PYOQp6T00ZjicgECQ_R10K/1608(0603)"))
    )
    (comp (ref "R208")
      (value "220")
      (footprint "eagle-import:R1608")
      (libsource (lib "eagle-import") (part "R220/1608(0603)"))
    )
    (comp (ref "R209")
      (value "220")
      (footprint "eagle-import:R1608")
      (libsource (lib "eagle-import") (part "R220/1608(0603)"))
    )
    (comp (ref "U$3")
      (value "RESETABLEFUSE")
      (footprint "eagle-import:R3216")
      (libsource (lib "eagle-import") (part "RESETABLEFUSE"))
    )
    (comp (ref "U$9")
      (value "MCP4018T-503E/LT")
      (footprint "eagle-import:SOT65P210X110-6N")
      (libsource (lib "eagle-import") (part "MCP4018T-503E/LT"))
    )
    (comp (ref "U$27")
      (value "SS2040FL")
      (footprint "eagle-import:SDO-123FL")
      (libsource (lib "eagle-import") (part "SS2040FL"))
    )
    (comp (ref "U$57")
      (value "SS2040FL")
      (footprint "eagle-import:SDO-123FL")
      (libsource (lib "eagle-import") (part "SS2040FL"))
    )
    (comp (ref "U1")
      (value "AZ1117H-ADJTRE1SOT-223_DIO")
      (footprint "eagle-import:SOT-223_DIO")
      (fields
        (field (name "MANUFACTURER_PART_NUMBER") "AZ1117H-ADJTRE1")
        (field (name "COPYRIGHT") "Copyright (C) 2025 Ultra Librarian. All rights reserved.")
      )
      (libsource (lib "eagle-import") (part "AZ1117H-ADJTRE1SOT-223_DIO"))
    )
    (comp (ref "UART1")
      (value "JST-XH-4PIN")
      (footprint "eagle-import:B4B-XH-A")
      (fields (field (name "MANUFACTURER") "JST Sales America Inc.") (field (name "MPN") "B4B-XH-A(LF)(SN)"))
      (libsource (lib "eagle-import") (part "B4B-XH-A"))
    )
  )
  (nets
    (net (code "1") (name "1-1") (class "Default")
      (node (ref "IC12") (pin "1") (pinfunction "OUTPUT_A_1") (pintype "bidirectional"))
      (node (ref "PIC32MK1024MCM100") (pin "48") (pinfunction "AN39/CVD39/RD15_48") (pintype "bidirectional"))
      (node (ref "R6") (pin "1") (pinfunction "P$1_1") (pintype "passive"))
    )
    (net (code "2") (name "1-2") (class "Default")
      (node (ref "IC12") (pin "7") (pinfunction "OUTPUT_B_7") (pintype "bidirectional"))
      (node (ref "PIC32MK1024MCM100") (pin "49") (pinfunction "TDI/DAC3/AN26/CVD26/RPA8/SDA2/PMA9/RA8_49") (pintype "bidirectional"))
      (node (ref "R12") (pin "2") (pinfunction "P$2_2") (pintype "passive"))
    )
    (net (code "3") (name "2-1") (class "Default")
      (node (ref "IC13") (pin "1") (pinfunction "OUTPUT_A_1") (pintype "bidirectional"))
      (node (ref "PIC32MK1024MCM100") (pin "47") (pinfunction "AN38/CVD38/RD14_47") (pintype "bidirectional"))
      (node (ref "R14") (pin "1") (pinfunction "P$1_1") (pintype "passive"))
    )
    (net (code "4") (name "2-2") (class "Default")
      (node (ref "IC13") (pin "7") (pinfunction "OUTPUT_B_7") (pintype "bidirectional"))
      (node (ref "PIC32MK1024MCM100") (pin "61") (pinfunction "AN45/CVD45/RF5_61") (pintype "bidirectional"))
      (node (ref "R15") (pin "2") (pinfunction "P$2_2") (pintype "passive"))
    )
    (net (code "5") (name "3-1") (class "Default")
      (node (ref "IC14") (pin "1") (pinfunction "OUTPUT_A_1") (pintype "bidirectional"))
      (node (ref "PIC32MK1024MCM100") (pin "66") (pinfunction "AN46/CVD46/RPA14/RA14_66") (pintype "bidirectional"))
      (node (ref "R16") (pin "1") (pinfunction "P$1_1") (pintype "passive"))
    )
    (net (code "6") (name "3-2") (class "Default")
      (node (ref "IC14") (pin "7") (pinfunction "OUTPUT_B_7") (pintype "bidirectional"))
      (node (ref "PIC32MK1024MCM100") (pin "67") (pinfunction "AN47/CVD47/RPA15/RA15_67") (pintype "bidirectional"))
      (node (ref "R17") (pin "2") (pinfunction "P$2_2") (pintype "passive"))
    )
    (net (code "7") (name "4-1") (class "Default")
      (node (ref "IC15") (pin "1") (pinfunction "OUTPUT_A_1") (pintype "bidirectional"))
      (node (ref "PIC32MK1024MCM100") (pin "68") (pinfunction "RD8_68") (pintype "bidirectional"))
      (node (ref "R21") (pin "1") (pinfunction "P$1_1") (pintype "passive"))
    )
    (net (code "8") (name "4-2") (class "Default")
      (node (ref "IC15") (pin "7") (pinfunction "OUTPUT_B_7") (pintype "bidirectional"))
      (node (ref "PIC32MK1024MCM100") (pin "72") (pinfunction "OA5OUT/AN25/CVD25/C5IN4-/RPB7/SCK1/INT0/RB7_72") (pintype "bidirectional"))
      (node (ref "R86") (pin "2") (pinfunction "P$2_2") (pintype "passive"))
    )
    (net (code "9") (name "5-1") (class "Default")
      (node (ref "IC16") (pin "1") (pinfunction "OUTPUT_A_1") (pintype "bidirectional"))
      (node (ref "PIC32MK1024MCM100") (pin "73") (pinfunction "SOSCI/RPC13/RC13_73") (pintype "bidirectional"))
      (node (ref "R87") (pin "1") (pinfunction "P$1_1") (pintype "passive"))
    )
    (net (code "10") (name "5-2") (class "Default")
      (node (ref "IC16") (pin "7") (pinfunction "OUTPUT_B_7") (pintype "bidirectional"))
      (node (ref "PIC32MK1024MCM100") (pin "74") (pinfunction "SOSCO/T1CK/RPB8/RB8_74") (pintype "bidirectional"))
      (node (ref "R146") (pin "2") (pinfunction "P$2_2") (pintype "passive"))
    )
    (net (code "11") (name "6-1") (class "Default")
      (node (ref "IC17") (pin "1") (pinfunction "OUTPUT_A_1") (pintype "bidirectional"))
      (node (ref "PIC32MK1024MCM100") (pin "76") (pinfunction "TMS/OA5IN-/AN27/CVD27/LVDIN/C5IN1-/RPB9/RB9_76") (pintype "bidirectional"))
      (node (ref "R147") (pin "1") (pinfunction "P$1_1") (pintype "passive"))
    )
    (net (code "12") (name "6-2") (class "Default")
      (node (ref "IC17") (pin "7") (pinfunction "OUTPUT_B_7") (pintype "bidirectional"))
      (node (ref "PIC32MK1024MCM100") (pin "77") (pinfunction "RPC6/USBID2/PMA16/RC6_77") (pintype "bidirectional"))
      (node (ref "R148") (pin "2") (pinfunction "P$2_2") (pintype "passive"))
    )
    (net (code "13") (name "7-1") (class "Default")
      (node (ref "IC18") (pin "1") (pinfunction "OUTPUT_A_1") (pintype "bidirectional"))
      (node (ref "PIC32MK1024MCM100") (pin "79") (pinfunction "PMD12/RD12_79") (pintype "bidirectional"))
      (node (ref "R149") (pin "1") (pinfunction "P$1_1") (pintype "passive"))
    )
    (net (code "14") (name "7-2") (class "Default")
      (node (ref "IC18") (pin "7") (pinfunction "OUTPUT_B_7") (pintype "bidirectional"))
      (node (ref "PIC32MK1024MCM100") (pin "78") (pinfunction "RPC7/PMA17/RC7_78") (pintype "bidirectional"))
      (node (ref "R150") (pin "2") (pinfunction "P$2_2") (pintype "passive"))
    )
    (net (code "15") (name "8-1") (class "Default")
      (node (ref "IC19") (pin "1") (pinfunction "OUTPUT_A_1") (pintype "bidirectional"))
      (node (ref "PIC32MK1024MCM100") (pin "80") (pinfunction "PMD13/RD13_80") (pintype "bidirectional"))
      (node (ref "R151") (pin "1") (pinfunction "P$1_1") (pintype "passive"))
    )
    (net (code "16") (name "8-2") (class "Default")
      (node (ref "IC19") (pin "7") (pinfunction "OUTPUT_B_7") (pintype "bidirectional"))
      (node (ref "PIC32MK1024MCM100") (pin "81") (pinfunction "RPC8/PMWR/RC8_81") (pintype "bidirectional"))
      (node (ref "R152") (pin "2") (pinfunction "P$2_2") (pintype "passive"))
    )
    (net (code "17") (name "9-1") (class "Default")
      (node (ref "IC20") (pin "1") (pinfunction "OUTPUT_A_1") (pintype "bidirectional"))
      (node (ref "PIC32MK1024MCM100") (pin "93") (pinfunction "RPB10/PWM3H/PMD0/RB10_93") (pintype "bidirectional"))
      (node (ref "R7") (pin "1") (pinfunction "P$1_1") (pintype "passive"))
    )
    (net (code "18") (name "9-2") (class "Default")
      (node (ref "IC20") (pin "7") (pinfunction "OUTPUT_B_7") (pintype "bidirectional"))
      (node (ref "PIC32MK1024MCM100") (pin "94") (pinfunction "RPB11/PWM9H/PWM3L/PMD1/RB11_94") (pintype "bidirectional"))
      (node (ref "R8") (pin "2") (pinfunction "P$2_2") (pintype "passive"))
    )
    (net (code "19") (name "10-1") (class "Default")
      (node (ref "IC21") (pin "1") (pinfunction "OUTPUT_A_1") (pintype "bidirectional"))
      (node (ref "PIC32MK1024MCM100") (pin "98") (pinfunction "RPB12/PWM2H/PMD2/RB12_98") (pintype "bidirectional"))
      (node (ref "R9") (pin "1") (pinfunction "P$1_1") (pintype "passive"))
    )
    (net (code "20") (name "10-2") (class "Default")
      (node (ref "IC21") (pin "7") (pinfunction "OUTPUT_B_7") (pintype "bidirectional"))
      (node (ref "PIC32MK1024MCM100") (pin "99") (pinfunction "RPB13/PWM8H/PWM2L/CTPLS/PMD3/RB13_99") (pintype "bidirectional"))
      (node (ref "R10") (pin "2") (pinfunction "P$2_2") (pintype "passive"))
    )
    (net (code "21") (name "11-1") (class "Default")
      (node (ref "IC22") (pin "1") (pinfunction "OUTPUT_A_1") (pintype "bidirectional"))
      (node (ref "PIC32MK1024MCM100") (pin "4") (pinfunction "RPB14/PWM1H/VBUSON1/PMD6/RB14_4") (pintype "bidirectional"))
      (node (ref "R11") (pin "1") (pinfunction "P$1_1") (pintype "passive"))
    )
    (net (code "22") (name "11-2") (class "Default")
      (node (ref "IC22") (pin "7") (pinfunction "OUTPUT_B_7") (pintype "bidirectional"))
      (node (ref "PIC32MK1024MCM100") (pin "5") (pinfunction "RPB15/PWM7H/PWM1L/PMD7/RB15_5") (pintype "bidirectional"))
      (node (ref "R13") (pin "2") (pinfunction "P$2_2") (pintype "passive"))
    )
    (net (code "23") (name "12-1") (class "Default")
      (node (ref "IC23") (pin "1") (pinfunction "OUTPUT_A_1") (pintype "bidirectional"))
      (node (ref "PIC32MK1024MCM100") (pin "6") (pinfunction "PWM11H/PWM5L/RD1_6") (pintype "bidirectional"))
      (node (ref "R153") (pin "1") (pinfunction "P$1_1") (pintype "passive"))
    )
    (net (code "24") (name "12-2") (class "Default")
      (node (ref "IC23") (pin "7") (pinfunction "OUTPUT_B_7") (pintype "bidirectional"))
      (node (ref "PIC32MK1024MCM100") (pin "7") (pinfunction "PWM5H/RD2_7") (pintype "bidirectional"))
      (node (ref "R154") (pin "2") (pinfunction "P$2_2") (pintype "passive"))
    )
    (net (code "25") (name "13-1") (class "Default")
      (node (ref "IC24") (pin "1") (pinfunction "OUTPUT_A_1") (pintype "bidirectional"))
      (node (ref "PIC32MK1024MCM100") (pin "11") (pinfunction "AN18/CVD18/RPG7/PWM10H/SCL1/PMA4/RG7_11") (pintype "bidirectional"))
      (node (ref "R155") (pin "1") (pinfunction "P$1_1") (pintype "passive"))
    )
    (net (code "26") (name "13-2") (class "Default")
      (node (ref "IC24") (pin "7") (pinfunction "OUTPUT_B_7") (pintype "bidirectional"))
      (node (ref "PIC32MK1024MCM100") (pin "12") (pinfunction "AN17/CVD17/RPG8/SDA1/PMA3/RG8_12") (pintype "bidirectional"))
      (node (ref "R156") (pin "2") (pinfunction "P$2_2") (pintype "passive"))
    )
    (net (code "27") (name "14-1") (class "Default")
      (node (ref "IC25") (pin "1") (pinfunction "OUTPUT_A_1") (pintype "bidirectional"))
      (node (ref "PIC32MK1024MCM100") (pin "26") (pinfunction "PGC1/OA1IN+/AN4/C1IN1+/C1IN3-/C2IN3-/RPB2/RB2_26") (pintype "bidirectional"))
      (node (ref "R157") (pin "1") (pinfunction "P$1_1") (pintype "passive"))
    )
    (net (code "28") (name "14-2") (class "Default")
      (node (ref "IC25") (pin "7") (pinfunction "OUTPUT_B_7") (pintype "bidirectional"))
      (node (ref "R158") (pin "2") (pinfunction "P$2_2") (pintype "passive"))
    )
    (net (code "29") (name "15-1") (class "Default")
      (node (ref "IC26") (pin "1") (pinfunction "OUTPUT_A_1") (pintype "bidirectional"))
      (node (ref "PIC32MK1024MCM100") (pin "27") (pinfunction "PGD1/OA1IN-/AN5/CTCMP/C1IN1-/RTCC/RPB3/RB3_27") (pintype "bidirectional"))
      (node (ref "R159") (pin "1") (pinfunction "P$1_1") (pintype "passive"))
    )
    (net (code "30") (name "15-2") (class "Default")
      (node (ref "IC26") (pin "7") (pinfunction "OUTPUT_B_7") (pintype "bidirectional"))
      (node (ref "PIC32MK1024MCM100") (pin "28") (pinfunction "VREF-/AN33/CVD33/PMA7/RF9_28") (pintype "bidirectional"))
      (node (ref "R160") (pin "2") (pinfunction "P$2_2") (pintype "passive"))
    )
    (net (code "31") (name "16-1") (class "Default")
      (node (ref "IC28") (pin "1") (pinfunction "OUTPUT_A_1") (pintype "bidirectional"))
      (node (ref "PIC32MK1024MCM100") (pin "33") (pinfunction "OA3IN-/AN7/CVD7/C3IN1-/C4IN1-/RPC1/RC1_33") (pintype "bidirectional"))
      (node (ref "R161") (pin "1") (pinfunction "P$1_1") (pintype "passive"))
    )
    (net (code "32") (name "16-2") (class "Default")
      (node (ref "IC28") (pin "7") (pinfunction "OUTPUT_B_7") (pintype "bidirectional"))
      (node (ref "PIC32MK1024MCM100") (pin "34") (pinfunction "OA3IN+/AN8/CVD8/C3IN1+/C3IN3-/RPC2/FLT3/PMA13/RC2_34") (pintype "bidirectional"))
      (node (ref "R162") (pin "2") (pinfunction "P$2_2") (pintype "passive"))
    )
    (net (code "33") (name "ANALOG-1") (class "Default")
      (node (ref "63") (pin "2") (pinfunction "E_2") (pintype "passive"))
      (node (ref "PIC32MK1024MCM100") (pin "14") (pinfunction "AN16/CVD16/RPG9/PMA2/RG9_14") (pintype "bidirectional"))
      (node (ref "R196") (pin "2") (pinfunction "P$2_2") (pintype "passive"))
    )
    (net (code "34") (name "B1") (class "Default")
      (node (ref "IC9") (pin "1") (pinfunction "OUTPUT_A_1") (pintype "bidirectional"))
      (node (ref "PIC32MK1024MCM100") (pin "21") (pinfunction "AN9/CVD9/RPA11/RA11_21") (pintype "bidirectional"))
      (node (ref "R176") (pin "1") (pinfunction "P$1_1") (pintype "passive"))
    )
    (net (code "35") (name "B1-IN") (class "Default")
      (node (ref "13") (pin "2") (pinfunction "E_2") (pintype "passive"))
      (node (ref "14") (pin "2") (pinfunction "E_2") (pintype "passive"))
      (node (ref "IC9") (pin "2") (pinfunction "INPUTS_A-_2") (pintype "bidirectional"))
      (node (ref "R132") (pin "2") (pinfunction "P$2_2") (pintype "passive"))
      (node (ref "R133") (pin "2") (pinfunction "P$2_2") (pintype "passive"))
    )
    (net (code "36") (name "B2") (class "Default")
      (node (ref "IC9") (pin "7") (pinfunction "OUTPUT_B_7") (pintype "bidirectional"))
      (node (ref "PIC32MK1024MCM100") (pin "20") (pinfunction "AN10/CVD10/RPA12/RA12_20") (pintype "bidirectional"))
      (node (ref "R177") (pin "2") (pinfunction "P$2_2") (pintype "passive"))
    )
    (net (code "37") (name "B2-IN") (class "Default")
      (node (ref "17") (pin "2") (pinfunction "E_2") (pintype "passive"))
      (node (ref "18") (pin "2") (pinfunction "E_2") (pintype "passive"))
      (node (ref "IC9") (pin "6") (pinfunction "INPUTS_B-_6") (pintype "bidirectional"))
      (node (ref "R136") (pin "2") (pinfunction "P$2_2") (pintype "passive"))
      (node (ref "R137") (pin "2") (pinfunction "P$2_2") (pintype "passive"))
    )
    (net (code "38") (name "B3") (class "Default")
      (node (ref "IC34") (pin "1") (pinfunction "OUTPUT_A_1") (pintype "bidirectional"))
      (node (ref "PIC32MK1024MCM100") (pin "19") (pinfunction "AN20/CVD20/RE9_19") (pintype "bidirectional"))
      (node (ref "R195") (pin "1") (pinfunction "P$1_1") (pintype "passive"))
    )
    (net (code "39") (name "B3-IN") (class "Default")
      (node (ref "15") (pin "2") (pinfunction "E_2") (pintype "passive"))
      (node (ref "IC34") (pin "2") (pinfunction "INPUTS_A-_2") (pintype "bidirectional"))
      (node (ref "R134") (pin "2") (pinfunction "P$2_2") (pintype "passive"))
    )
    (net (code "40") (name "B4") (class "Default")
      (node (ref "IC34") (pin "7") (pinfunction "OUTPUT_B_7") (pintype "bidirectional"))
      (node (ref "PIC32MK1024MCM100") (pin "18") (pinfunction "AN21/CVD21/RE8_18") (pintype "bidirectional"))
      (node (ref "R197") (pin "2") (pinfunction "P$2_2") (pintype "passive"))
    )
    (net (code "41") (name "B4-IN") (class "Default")
      (node (ref "16") (pin "2") (pinfunction "E_2") (pintype "passive"))
      (node (ref "IC34") (pin "6") (pinfunction "INPUTS_B-_6") (pintype "bidirectional"))
      (node (ref "R135") (pin "2") (pinfunction "P$2_2") (pintype "passive"))
    )
    (net (code "42") (name "BB1") (class "Default")
      (node (ref "IC31") (pin "1") (pinfunction "OUTPUT_A_1") (pintype "bidirectional"))
      (node (ref "PIC32MK1024MCM100") (pin "9") (pinfunction "RPD4/PWM6H/RD4_9") (pintype "bidirectional"))
      (node (ref "R186") (pin "1") (pinfunction "P$1_1") (pintype "passive"))
    )
    (net (code "43") (name "BB2") (class "Default")
      (node (ref "IC31") (pin "7") (pinfunction "OUTPUT_B_7") (pintype "bidirectional"))
      (node (ref "PIC32MK1024MCM100") (pin "8") (pinfunction "RPD3/PWM12H/PWM6L/RD3_8") (pintype "bidirectional"))
      (node (ref "R187") (pin "2") (pinfunction "P$2_2") (pintype "passive"))
    )
    (net (code "44") (name "BB3") (class "Default")
      (node (ref "IC29") (pin "7") (pinfunction "OUTPUT_B_7") (pintype "bidirectional"))
      (node (ref "PIC32MK1024MCM100") (pin "22") (pinfunction "OA2OUT/AN0/C2IN4-/C4IN3-/RPA0/RA0_22") (pintype "bidirectional"))
      (node (ref "R189") (pin "2") (pinfunction "P$2_2") (pintype "passive"))
    )
    (net (code "45") (name "BR1-IN") (class "Default")
      (node (ref "53") (pin "2") (pinfunction "E_2") (pintype "passive"))
      (node (ref "IC31") (pin "2") (pinfunction "INPUTS_A-_2") (pintype "bidirectional"))
      (node (ref "R140") (pin "2") (pinfunction "P$2_2") (pintype "passive"))
    )
    (net (code "46") (name "BR2-IN") (class "Default")
      (node (ref "54") (pin "2") (pinfunction "E_2") (pintype "passive"))
      (node (ref "IC31") (pin "6") (pinfunction "INPUTS_B-_6") (pintype "bidirectional"))
      (node (ref "R141") (pin "2") (pinfunction "P$2_2") (pintype "passive"))
    )
    (net (code "47") (name "BR3-IN") (class "Default")
      (node (ref "55") (pin "2") (pinfunction "E_2") (pintype "passive"))
      (node (ref "IC29") (pin "6") (pinfunction "INPUTS_B-_6") (pintype "bidirectional"))
      (node (ref "R142") (pin "2") (pinfunction "P$2_2") (pintype "passive"))
    )
    (net (code "48") (name "DAC") (class "Default")
      (node (ref "IC11") (pin "3") (pinfunction "INPUTS_A+_3") (pintype "bidirectional"))
      (node (ref "IC11") (pin "5") (pinfunction "INPUTS_B+_5") (pintype "bidirectional"))
      (node (ref "IC12") (pin "3") (pinfunction "INPUTS_A+_3") (pintype "bidirectional"))
      (node (ref "IC12") (pin "5") (pinfunction "INPUTS_B+_5") (pintype "bidirectional"))
      (node (ref "IC13") (pin "3") (pinfunction "INPUTS_A+_3") (pintype "bidirectional"))
      (node (ref "IC13") (pin "5") (pinfunction "INPUTS_B+_5") (pintype "bidirectional"))
      (node (ref "IC14") (pin "3") (pinfunction "INPUTS_A+_3") (pintype "bidirectional"))
      (node (ref "IC14") (pin "5") (pinfunction "INPUTS_B+_5") (pintype "bidirectional"))
      (node (ref "IC15") (pin "3") (pinfunction "INPUTS_A+_3") (pintype "bidirectional"))
      (node (ref "IC15") (pin "5") (pinfunction "INPUTS_B+_5") (pintype "bidirectional"))
      (node (ref "IC16") (pin "3") (pinfunction "INPUTS_A+_3") (pintype "bidirectional"))
      (node (ref "IC16") (pin "5") (pinfunction "INPUTS_B+_5") (pintype "bidirectional"))
      (node (ref "IC17") (pin "3") (pinfunction "INPUTS_A+_3") (pintype "bidirectional"))
      (node (ref "IC17") (pin "5") (pinfunction "INPUTS_B+_5") (pintype "bidirectional"))
      (node (ref "IC18") (pin "3") (pinfunction "INPUTS_A+_3") (pintype "bidirectional"))
      (node (ref "IC18") (pin "5") (pinfunction "INPUTS_B+_5") (pintype "bidirectional"))
      (node (ref "IC19") (pin "3") (pinfunction "INPUTS_A+_3") (pintype "bidirectional"))
      (node (ref "IC19") (pin "5") (pinfunction "INPUTS_B+_5") (pintype "bidirectional"))
      (node (ref "IC2") (pin "3") (pinfunction "INPUTS_A+_3") (pintype "bidirectional"))
      (node (ref "IC2") (pin "5") (pinfunction "INPUTS_B+_5") (pintype "bidirectional"))
      (node (ref "IC20") (pin "3") (pinfunction "INPUTS_A+_3") (pintype "bidirectional"))
      (node (ref "IC20") (pin "5") (pinfunction "INPUTS_B+_5") (pintype "bidirectional"))
      (node (ref "IC21") (pin "3") (pinfunction "INPUTS_A+_3") (pintype "bidirectional"))
      (node (ref "IC21") (pin "5") (pinfunction "INPUTS_B+_5") (pintype "bidirectional"))
      (node (ref "IC22") (pin "3") (pinfunction "INPUTS_A+_3") (pintype "bidirectional"))
      (node (ref "IC22") (pin "5") (pinfunction "INPUTS_B+_5") (pintype "bidirectional"))
      (node (ref "IC23") (pin "3") (pinfunction "INPUTS_A+_3") (pintype "bidirectional"))
      (node (ref "IC23") (pin "5") (pinfunction "INPUTS_B+_5") (pintype "bidirectional"))
      (node (ref "IC24") (pin "3") (pinfunction "INPUTS_A+_3") (pintype "bidirectional"))
      (node (ref "IC24") (pin "5") (pinfunction "INPUTS_B+_5") (pintype "bidirectional"))
      (node (ref "IC25") (pin "3") (pinfunction "INPUTS_A+_3") (pintype "bidirectional"))
      (node (ref "IC25") (pin "5") (pinfunction "INPUTS_B+_5") (pintype "bidirectional"))
      (node (ref "IC26") (pin "3") (pinfunction "INPUTS_A+_3") (pintype "bidirectional"))
      (node (ref "IC26") (pin "5") (pinfunction "INPUTS_B+_5") (pintype "bidirectional"))
      (node (ref "IC27") (pin "3") (pinfunction "INPUTS_A+_3") (pintype "bidirectional"))
      (node (ref "IC27") (pin "5") (pinfunction "INPUTS_B+_5") (pintype "bidirectional"))
      (node (ref "IC28") (pin "3") (pinfunction "INPUTS_A+_3") (pintype "bidirectional"))
      (node (ref "IC28") (pin "5") (pinfunction "INPUTS_B+_5") (pintype "bidirectional"))
      (node (ref "IC29") (pin "3") (pinfunction "INPUTS_A+_3") (pintype "bidirectional"))
      (node (ref "IC29") (pin "5") (pinfunction "INPUTS_B+_5") (pintype "bidirectional"))
      (node (ref "IC3") (pin "3") (pinfunction "INPUTS_A+_3") (pintype "bidirectional"))
      (node (ref "IC3") (pin "5") (pinfunction "INPUTS_B+_5") (pintype "bidirectional"))
      (node (ref "IC30") (pin "3") (pinfunction "INPUTS_A+_3") (pintype "bidirectional"))
      (node (ref "IC30") (pin "5") (pinfunction "INPUTS_B+_5") (pintype "bidirectional"))
      (node (ref "IC31") (pin "3") (pinfunction "INPUTS_A+_3") (pintype "bidirectional"))
      (node (ref "IC31") (pin "5") (pinfunction "INPUTS_B+_5") (pintype "bidirectional"))
      (node (ref "IC32") (pin "3") (pinfunction "INPUTS_A+_3") (pintype "bidirectional"))
      (node (ref "IC32") (pin "5") (pinfunction "INPUTS_B+_5") (pintype "bidirectional"))
      (node (ref "IC33") (pin "3") (pinfunction "INPUTS_A+_3") (pintype "bidirectional"))
      (node (ref "IC33") (pin "5") (pinfunction "INPUTS_B+_5") (pintype "bidirectional"))
      (node (ref "IC34") (pin "3") (pinfunction "INPUTS_A+_3") (pintype "bidirectional"))
      (node (ref "IC34") (pin "5") (pinfunction "INPUTS_B+_5") (pintype "bidirectional"))
      (node (ref "IC5") (pin "3") (pinfunction "INPUTS_A+_3") (pintype "bidirectional"))
      (node (ref "IC5") (pin "5") (pinfunction "INPUTS_B+_5") (pintype "bidirectional"))
      (node (ref "IC6") (pin "3") (pinfunction "INPUTS_A+_3") (pintype "bidirectional"))
      (node (ref "IC6") (pin "5") (pinfunction "INPUTS_B+_5") (pintype "bidirectional"))
      (node (ref "IC8") (pin "3") (pinfunction "INPUTS_A+_3") (pintype "bidirectional"))
      (node (ref "IC8") (pin "5") (pinfunction "INPUTS_B+_5") (pintype "bidirectional"))
      (node (ref "IC9") (pin "3") (pinfunction "INPUTS_A+_3") (pintype "bidirectional"))
      (node (ref "IC9") (pin "5") (pinfunction "INPUTS_B+_5") (pintype "bidirectional"))
      (node (ref "PIC32MK1024MCM100") (pin "71") (pinfunction "DAC2/AN48/CVD48/RPC10/PMA14/PMCS/RC10_71") (pintype "bidirectional"))
      (node (ref "R22") (pin "2") (pinfunction "P$2_2") (pintype "passive"))
    )
    (net (code "49") (name "DI") (class "Default")
      (node (ref "PIC32MK1024MCM100") (pin "100") (pinfunction "TDO/PWM4H/PMD4/RA10_100") (pintype "bidirectional"))
      (node (ref "Q2") (pin "2") (pinfunction "S_2") (pintype "bidirectional"))
      (node (ref "R206") (pin "1") (pinfunction "P$1_1") (pintype "passive"))
    )
    (net (code "50") (name "DI-OUT") (class "Default")
      (node (ref "LED1") (pin "4") (pinfunction "DIN_4") (pintype "bidirectional"))
      (node (ref "Q2") (pin "3") (pinfunction "D_3") (pintype "bidirectional"))
      (node (ref "R207") (pin "1") (pinfunction "P$1_1") (pintype "passive"))
    )
    (net (code "51") (name "GND-1") (class "Default")
      (node (ref "+3.3V") (pin "C") (pinfunction "C_C") (pintype "passive"))
      (node (ref "C1") (pin "2") (pinfunction "P$2_2") (pintype "passive"))
      (node (ref "C10") (pin "2") (pinfunction "P$2_2") (pintype "passive"))
      (node (ref "C11") (pin "2") (pinfunction "P$2_2") (pintype "passive"))
      (node (ref "C12") (pin "2") (pinfunction "P$2_2") (pintype "passive"))
      (node (ref "C14") (pin "2") (pinfunction "P$2_2") (pintype "passive"))
      (node (ref "C15") (pin "2") (pinfunction "P$2_2") (pintype "passive"))
      (node (ref "C17") (pin "1") (pinfunction "P$1_1") (pintype "passive"))
      (node (ref "C18") (pin "2") (pinfunction "P$2_2") (pintype "passive"))
      (node (ref "C19") (pin "2") (pinfunction "P$2_2") (pintype "passive"))
      (node (ref "C2") (pin "1") (pinfunction "P$1_1") (pintype "passive"))
      (node (ref "C20") (pin "2") (pinfunction "P$2_2") (pintype "passive"))
      (node (ref "C22") (pin "2") (pinfunction "P$2_2") (pintype "passive"))
      (node (ref "C23") (pin "2") (pinfunction "P$2_2") (pintype "passive"))
      (node (ref "C24") (pin "2") (pinfunction "P$2_2") (pintype "passive"))
      (node (ref "C25") (pin "2") (pinfunction "P$2_2") (pintype "passive"))
      (node (ref "C26") (pin "2") (pinfunction "P$2_2") (pintype "passive"))
      (node (ref "C27") (pin "2") (pinfunction "P$2_2") (pintype "passive"))
      (node (ref "C28") (pin "2") (pinfunction "P$2_2") (pintype "passive"))
      (node (ref "C29") (pin "2") (pinfunction "P$2_2") (pintype "passive"))
      (node (ref "C3") (pin "2") (pinfunction "P$2_2") (pintype "passive"))
      (node (ref "C30") (pin "2") (pinfunction "P$2_2") (pintype "passive"))
      (node (ref "C31") (pin "2") (pinfunction "P$2_2") (pintype "passive"))
      (node (ref "C32") (pin "2") (pinfunction "P$2_2") (pintype "passive"))
      (node (ref "C33") (pin "2") (pinfunction "P$2_2") (pintype "passive"))
      (node (ref "C34") (pin "2") (pinfunction "P$2_2") (pintype "passive"))
      (node (ref "C35") (pin "2") (pinfunction "P$2_2") (pintype "passive"))
      (node (ref "C36") (pin "2") (pinfunction "P$2_2") (pintype "passive"))
      (node (ref "C37") (pin "2") (pinfunction "P$2_2") (pintype "passive"))
      (node (ref "C38") (pin "2") (pinfunction "P$2_2") (pintype "passive"))
      (node (ref "C39") (pin "-") (pinfunction "P$2-_-") (pintype "passive"))
      (node (ref "C4") (pin "2") (pinfunction "P$2_2") (pintype "passive"))
      (node (ref "C40") (pin "2") (pinfunction "P$2_2") (pintype "passive"))
      (node (ref "C41") (pin "2") (pinfunction "P$2_2") (pintype "passive"))
      (node (ref "C42") (pin "2") (pinfunction "P$2_2") (pintype "passive"))
      (node (ref "C43") (pin "2") (pinfunction "P$2_2") (pintype "passive"))
      (node (ref "C44") (pin "2") (pinfunction "P$2_2") (pintype "passive"))
      (node (ref "C45") (pin "2") (pinfunction "P$2_2") (pintype "passive"))
      (node (ref "C46") (pin "2") (pinfunction "P$2_2") (pintype "passive"))
      (node (ref "C47") (pin "2") (pinfunction "P$2_2") (pintype "passive"))
      (node (ref "C48") (pin "2") (pinfunction "P$2_2") (pintype "passive"))
      (node (ref "C5") (pin "1") (pinfunction "P$1_1") (pintype "passive"))
      (node (ref "C6") (pin "2") (pinfunction "P$2_2") (pintype "passive"))
      (node (ref "C7") (pin "2") (pinfunction "P$2_2") (pintype "passive"))
      (node (ref "C8") (pin "2") (pinfunction "P$2_2") (pintype "passive"))
      (node (ref "C9") (pin "1") (pinfunction "P$1_1") (pintype "passive"))
      (node (ref "D1") (pin "C") (pinfunction "C_C") (pintype "passive"))
      (node (ref "D10") (pin "C") (pinfunction "C_C") (pintype "passive"))
      (node (ref "D11") (pin "C") (pinfunction "C_C") (pintype "passive"))
      (node (ref "D12") (pin "C") (pinfunction "C_C") (pintype "passive"))
      (node (ref "D13") (pin "C") (pinfunction "C_C") (pintype "passive"))
      (node (ref "D14") (pin "C") (pinfunction "C_C") (pintype "passive"))
      (node (ref "D15") (pin "C") (pinfunction "C_C") (pintype "passive"))
      (node (ref "D16") (pin "C") (pinfunction "C_C") (pintype "passive"))
      (node (ref "D17") (pin "C") (pinfunction "C_C") (pintype "passive"))
      (node (ref "D18") (pin "C") (pinfunction "C_C") (pintype "passive"))
      (node (ref "D19") (pin "C") (pinfunction "C_C") (pintype "passive"))
      (node (ref "D2") (pin "C") (pinfunction "C_C") (pintype "passive"))
      (node (ref "D20") (pin "C") (pinfunction "C_C") (pintype "passive"))
      (node (ref "D21") (pin "C") (pinfunction "C_C") (pintype "passive"))
      (node (ref "D22") (pin "C") (pinfunction "C_C") (pintype "passive"))
      (node (ref "D23") (pin "C") (pinfunction "C_C") (pintype "passive"))
      (node (ref "D24") (pin "C") (pinfunction "C_C") (pintype "passive"))
      (node (ref "D25") (pin "C") (pinfunction "C_C") (pintype "passive"))
      (node (ref "D26") (pin "C") (pinfunction "C_C") (pintype "passive"))
      (node (ref "D27") (pin "C") (pinfunction "C_C") (pintype "passive"))
      (node (ref "D28") (pin "C") (pinfunction "C_C") (pintype "passive"))
      (node (ref "D29") (pin "C") (pinfunction "C_C") (pintype "passive"))
      (node (ref "D3") (pin "C") (pinfunction "C_C") (pintype "passive"))
      (node (ref "D30") (pin "C") (pinfunction "C_C") (pintype "passive"))
      (node (ref "D31") (pin "C") (pinfunction "C_C") (pintype "passive"))
      (node (ref "D32") (pin "C") (pinfunction "C_C") (pintype "passive"))
      (node (ref "D33") (pin "C") (pinfunction "C_C") (pintype "passive"))
      (node (ref "D34") (pin "C") (pinfunction "C_C") (pintype "passive"))
      (node (ref "D35") (pin "C") (pinfunction "C_C") (pintype "passive"))
      (node (ref "D36") (pin "C") (pinfunction "C_C") (pintype "passive"))
      (node (ref "D37") (pin "C") (pinfunction "C_C") (pintype "passive"))
      (node (ref "D38") (pin "C") (pinfunction "C_C") (pintype "passive"))
      (node (ref "D39") (pin "C") (pinfunction "C_C") (pintype "passive"))
      (node (ref "D4") (pin "C") (pinfunction "C_C") (pintype "passive"))
      (node (ref "D40") (pin "C") (pinfunction "C_C") (pintype "passive"))
      (node (ref "D41") (pin "C") (pinfunction "C_C") (pintype "passive"))
      (node (ref "D42") (pin "C") (pinfunction "C_C") (pintype "passive"))
      (node (ref "D43") (pin "C") (pinfunction "C_C") (pintype "passive"))
      (node (ref "D44") (pin "C") (pinfunction "C_C") (pintype "passive"))
      (node (ref "D45") (pin "C") (pinfunction "C_C") (pintype "passive"))
      (node (ref "D46") (pin "C") (pinfunction "C_C") (pintype "passive"))
      (node (ref "D47") (pin "C") (pinfunction "C_C") (pintype "passive"))
      (node (ref "D48") (pin "C") (pinfunction "C_C") (pintype "passive"))
      (node (ref "D49") (pin "C") (pinfunction "C_C") (pintype "passive"))
      (node (ref "D5") (pin "C") (pinfunction "C_C") (pintype "passive"))
      (node (ref "D50") (pin "C") (pinfunction "C_C") (pintype "passive"))
      (node (ref "D51") (pin "C") (pinfunction "C_C") (pintype "passive"))
      (node (ref "D52") (pin "C") (pinfunction "C_C") (pintype "passive"))
      (node (ref "D53") (pin "C") (pinfunction "C_C") (pintype "passive"))
      (node (ref "D54") (pin "C") (pinfunction "C_C") (pintype "passive"))
      (node (ref "D55") (pin "C") (pinfunction "C_C") (pintype "passive"))
      (node (ref "D56") (pin "C") (pinfunction "C_C") (pintype "passive"))
      (node (ref "D57") (pin "C") (pinfunction "C_C") (pintype "passive"))
      (node (ref "D58") (pin "C") (pinfunction "C_C") (pintype "passive"))
      (node (ref "D59") (pin "C") (pinfunction "C_C") (pintype "passive"))
      (node (ref "D6") (pin "C") (pinfunction "C_C") (pintype "passive"))
      (node (ref "D60") (pin "C") (pinfunction "C_C") (pintype "passive"))
      (node (ref "D61") (pin "C") (pinfunction "C_C") (pintype "passive"))
      (node (ref "D62") (pin "C") (pinfunction "C_C") (pintype "passive"))
      (node (ref "D63") (pin "C") (pinfunction "C_C") (pintype "passive"))
      (node (ref "D64") (pin "C") (pinfunction "C_C") (pintype "passive"))
      (node (ref "D65") (pin "C") (pinfunction "C_C") (pintype "passive"))
      (node (ref "D66") (pin "C") (pinfunction "C_C") (pintype "passive"))
      (node (ref "D67") (pin "C") (pinfunction "C_C") (pintype "passive"))
      (node (ref "D68") (pin "C") (pinfunction "C_C") (pintype "passive"))
      (node (ref "D69") (pin "C") (pinfunction "C_C") (pintype "passive"))
      (node (ref "D7") (pin "C") (pinfunction "C_C") (pintype "passive"))
      (node (ref "D70") (pin "C") (pinfunction "C_C") (pintype "passive"))
      (node (ref "D71") (pin "C") (pinfunction "C_C") (pintype "passive"))
      (node (ref "D72") (pin "C") (pinfunction "C_C") (pintype "passive"))
      (node (ref "D8") (pin "C") (pinfunction "C_C") (pintype "passive"))
      (node (ref "D9") (pin "C") (pinfunction "C_C") (pintype "passive"))
      (node (ref "DEBUG_UART") (pin "4") (pinfunction "4_4") (pintype "passive"))
      (node (ref "IC1") (pin "1") (pinfunction "ADJ/GND_1") (pintype "bidirectional"))
      (node (ref "IC11") (pin "4") (pinfunction "GND_4") (pintype "bidirectional"))
      (node (ref "IC12") (pin "4") (pinfunction "GND_4") (pintype "bidirectional"))
      (node (ref "IC13") (pin "4") (pinfunction "GND_4") (pintype "bidirectional"))
      (node (ref "IC14") (pin "4") (pinfunction "GND_4") (pintype "bidirectional"))
      (node (ref "IC15") (pin "4") (pinfunction "GND_4") (pintype "bidirectional"))
      (node (ref "IC16") (pin "4") (pinfunction "GND_4") (pintype "bidirectional"))
      (node (ref "IC17") (pin "4") (pinfunction "GND_4") (pintype "bidirectional"))
      (node (ref "IC18") (pin "4") (pinfunction "GND_4") (pintype "bidirectional"))
      (node (ref "IC19") (pin "4") (pinfunction "GND_4") (pintype "bidirectional"))
      (node (ref "IC2") (pin "4") (pinfunction "GND_4") (pintype "bidirectional"))
      (node (ref "IC20") (pin "4") (pinfunction "GND_4") (pintype "bidirectional"))
      (node (ref "IC21") (pin "4") (pinfunction "GND_4") (pintype "bidirectional"))
      (node (ref "IC22") (pin "4") (pinfunction "GND_4") (pintype "bidirectional"))
      (node (ref "IC23") (pin "4") (pinfunction "GND_4") (pintype "bidirectional"))
      (node (ref "IC24") (pin "4") (pinfunction "GND_4") (pintype "bidirectional"))
      (node (ref "IC25") (pin "4") (pinfunction "GND_4") (pintype "bidirectional"))
      (node (ref "IC26") (pin "4") (pinfunction "GND_4") (pintype "bidirectional"))
      (node (ref "IC27") (pin "4") (pinfunction "GND_4") (pintype "bidirectional"))
      (node (ref "IC28") (pin "4") (pinfunction "GND_4") (pintype "bidirectional"))
      (node (ref "IC29") (pin "4") (pinfunction "GND_4") (pintype "bidirectional"))
      (node (ref "IC3") (pin "4") (pinfunction "GND_4") (pintype "bidirectional"))
      (node (ref "IC30") (pin "4") (pinfunction "GND_4") (pintype "bidirectional"))
      (node (ref "IC31") (pin "4") (pinfunction "GND_4") (pintype "bidirectional"))
      (node (ref "IC32") (pin "4") (pinfunction "GND_4") (pintype "bidirectional"))
      (node (ref "IC33") (pin "4") (pinfunction "GND_4") (pintype "bidirectional"))
      (node (ref "IC34") (pin "4") (pinfunction "GND_4") (pintype "bidirectional"))
      (node (ref "IC5") (pin "4") (pinfunction "GND_4") (pintype "bidirectional"))
      (node (ref "IC6") (pin "4") (pinfunction "GND_4") (pintype "bidirectional"))
      (node (ref "IC8") (pin "4") (pinfunction "GND_4") (pintype "bidirectional"))
      (node (ref "IC9") (pin "4") (pinfunction "GND_4") (pintype "bidirectional"))
      (node (ref "J2") (pin "2") (pinfunction "2_2") (pintype "bidirectional"))
      (node (ref "LED1") (pin "3") (pinfunction "VSS_3") (pintype "bidirectional"))
      (node (ref "MCLR") (pin "3") (pinfunction "P$3_3") (pintype "bidirectional"))
      (node (ref "PIC32MK1024MCM100") (pin "15") (pinfunction "VSS_1_15") (pintype "bidirectional"))
      (node (ref "PIC32MK1024MCM100") (pin "31") (pinfunction "AVSS_31") (pintype "bidirectional"))
      (node (ref "PIC32MK1024MCM100") (pin "36") (pinfunction "VSS_2_36") (pintype "bidirectional"))
      (node (ref "PIC32MK1024MCM100") (pin "45") (pinfunction "VSS_3_45") (pintype "bidirectional"))
      (node (ref "PIC32MK1024MCM100") (pin "54") (pinfunction "VBUS_54") (pintype "bidirectional"))
      (node (ref "PIC32MK1024MCM100") (pin "58") (pinfunction "VBUS2_58") (pintype "bidirectional"))
      (node (ref "PIC32MK1024MCM100") (pin "65") (pinfunction "VSS_4_65") (pintype "bidirectional"))
      (node (ref "PIC32MK1024MCM100") (pin "75") (pinfunction "VSS_5_75") (pintype "bidirectional"))
      (node (ref "PIC32MK1024MCM100") (pin "85") (pinfunction "VSS_6_85") (pintype "bidirectional"))
      (node (ref "R100") (pin "1") (pinfunction "P$1_1") (pintype "passive"))
      (node (ref "R101") (pin "1") (pinfunction "P$1_1") (pintype "passive"))
      (node (ref "R102") (pin "1") (pinfunction "P$1_1") (pintype "passive"))
      (node (ref "R103") (pin "1") (pinfunction "P$1_1") (pintype "passive"))
      (node (ref "R104") (pin "1") (pinfunction "P$1_1") (pintype "passive"))
      (node (ref "R105") (pin "1") (pinfunction "P$1_1") (pintype "passive"))
      (node (ref "R106") (pin "1") (pinfunction "P$1_1") (pintype "passive"))
      (node (ref "R107") (pin "1") (pinfunction "P$1_1") (pintype "passive"))
      (node (ref "R108") (pin "1") (pinfunction "P$1_1") (pintype "passive"))
      (node (ref "R109") (pin "1") (pinfunction "P$1_1") (pintype "passive"))
      (node (ref "R110") (pin "1") (pinfunction "P$1_1") (pintype "passive"))
      (node (ref "R111") (pin "1") (pinfunction "P$1_1") (pintype "passive"))
      (node (ref "R112") (pin "1") (pinfunction "P$1_1") (pintype "passive"))
      (node (ref "R113") (pin "1") (pinfunction "P$1_1") (pintype "passive"))
      (node (ref "R114") (pin "1") (pinfunction "P$1_1") (pintype "passive"))
      (node (ref "R115") (pin "1") (pinfunction "P$1_1") (pintype "passive"))
      (node (ref "R116") (pin "1") (pinfunction "P$1_1") (pintype "passive"))
      (node (ref "R117") (pin "1") (pinfunction "P$1_1") (pintype "passive"))
      (node (ref "R118") (pin "1") (pinfunction "P$1_1") (pintype "passive"))
      (node (ref "R119") (pin "1") (pinfunction "P$1_1") (pintype "passive"))
      (node (ref "R120") (pin "1") (pinfunction "P$1_1") (pintype "passive"))
      (node (ref "R121") (pin "1") (pinfunction "P$1_1") (pintype "passive"))
      (node (ref "R122") (pin "1") (pinfunction "P$1_1") (pintype "passive"))
      (node (ref "R123") (pin "1") (pinfunction "P$1_1") (pintype "passive"))
      (node (ref "R124") (pin "1") (pinfunction "P$1_1") (pintype "passive"))
      (node (ref "R125") (pin "1") (pinfunction "P$1_1") (pintype "passive"))
      (node (ref "R126") (pin "1") (pinfunction "P$1_1") (pintype "passive"))
      (node (ref "R127") (pin "1") (pinfunction "P$1_1") (pintype "passive"))
      (node (ref "R128") (pin "1") (pinfunction "P$1_1") (pintype "passive"))
      (node (ref "R129") (pin "1") (pinfunction "P$1_1") (pintype "passive"))
      (node (ref "R130") (pin "1") (pinfunction "P$1_1") (pintype "passive"))
      (node (ref "R131") (pin "1") (pinfunction "P$1_1") (pintype "passive"))
      (node (ref "R132") (pin "1") (pinfunction "P$1_1") (pintype "passive"))
      (node (ref "R133") (pin "1") (pinfunction "P$1_1") (pintype "passive"))
      (node (ref "R134") (pin "1") (pinfunction "P$1_1") (pintype "passive"))
      (node (ref "R135") (pin "1") (pinfunction "P$1_1") (pintype "passive"))
      (node (ref "R136") (pin "1") (pinfunction "P$1_1") (pintype "passive"))
      (node (ref "R137") (pin "1") (pinfunction "P$1_1") (pintype "passive"))
      (node (ref "R138") (pin "1") (pinfunction "P$1_1") (pintype "passive"))
      (node (ref "R139") (pin "1") (pinfunction "P$1_1") (pintype "passive"))
      (node (ref "R140") (pin "1") (pinfunction "P$1_1") (pintype "passive"))
      (node (ref "R141") (pin "1") (pinfunction "P$1_1") (pintype "passive"))
      (node (ref "R142") (pin "1") (pinfunction "P$1_1") (pintype "passive"))
      (node (ref "R143") (pin "2") (pinfunction "P$2_2") (pintype "passive"))
      (node (ref "R144") (pin "1") (pinfunction "P$1_1") (pintype "passive"))
      (node (ref "R166") (pin "2") (pinfunction "P$2_2") (pintype "passive"))
      (node (ref "R167") (pin "2") (pinfunction "P$2_2") (pintype "passive"))
      (node (ref "R178") (pin "2") (pinfunction "P$2_2") (pintype "passive"))
      (node (ref "R196") (pin "1") (pinfunction "P$1_1") (pintype "passive"))
      (node (ref "R22") (pin "1") (pinfunction "P$1_1") (pintype "passive"))
      (node (ref "R82") (pin "1") (pinfunction "P$1_1") (pintype "passive"))
      (node (ref "R83") (pin "1") (pinfunction "P$1_1") (pintype "passive"))
      (node (ref "R84") (pin "1") (pinfunction "P$1_1") (pintype "passive"))
      (node (ref "R88") (pin "1") (pinfunction "P$1_1") (pintype "passive"))
      (node (ref "R89") (pin "1") (pinfunction "P$1_1") (pintype "passive"))
      (node (ref "R90") (pin "1") (pinfunction "P$1_1") (pintype "passive"))
      (node (ref "R91") (pin "1") (pinfunction "P$1_1") (pintype "passive"))
      (node (ref "R92") (pin "1") (pinfunction "P$1_1") (pintype "passive"))
      (node (ref "R93") (pin "1") (pinfunction "P$1_1") (pintype "passive"))
      (node (ref "R94") (pin "1") (pinfunction "P$1_1") (pintype "passive"))
      (node (ref "R95") (pin "1") (pinfunction "P$1_1") (pintype "passive"))
      (node (ref "R96") (pin "1") (pinfunction "P$1_1") (pintype "passive"))
      (node (ref "R97") (pin "1") (pinfunction "P$1_1") (pintype "passive"))
      (node (ref "R98") (pin "1") (pinfunction "P$1_1") (pintype "passive"))
      (node (ref "R99") (pin "1") (pinfunction "P$1_1") (pintype "passive"))
      (node (ref "U$27") (pin "P$1") (pinfunction "A_P$1") (pintype "passive"))
      (node (ref "U$9") (pin "2") (pinfunction "VSS_2") (pintype "power_in"))
      (node (ref "UART1") (pin "4") (pinfunction "4_4") (pintype "bidirectional"))
    )
    (net (code "52") (name "L1") (class "Default")
      (node (ref "IC6") (pin "1") (pinfunction "OUTPUT_A_1") (pintype "bidirectional"))
      (node (ref "PIC32MK1024MCM100") (pin "3") (pinfunction "TCK/RPA7/PWM10H/PWM4L/PMD5/RA7_3") (pintype "bidirectional"))
      (node (ref "R170") (pin "1") (pinfunction "P$1_1") (pintype "passive"))
    )
    (net (code "53") (name "L1-IN") (class "Default")
      (node (ref "7") (pin "2") (pinfunction "E_2") (pintype "passive"))
      (node (ref "IC6") (pin "2") (pinfunction "INPUTS_A-_2") (pintype "bidirectional"))
      (node (ref "R126") (pin "2") (pinfunction "P$2_2") (pintype "passive"))
    )
    (net (code "54") (name "L2") (class "Default")
      (node (ref "IC6") (pin "7") (pinfunction "OUTPUT_B_7") (pintype "bidirectional"))
      (node (ref "PIC32MK1024MCM100") (pin "1") (pinfunction "AN23/CVD23/PWM7L/PMA23/RG15_1") (pintype "bidirectional"))
      (node (ref "R171") (pin "2") (pinfunction "P$2_2") (pintype "passive"))
    )
    (net (code "55") (name "L2-IN") (class "Default")
      (node (ref "8") (pin "2") (pinfunction "E_2") (pintype "passive"))
      (node (ref "IC6") (pin "6") (pinfunction "INPUTS_B-_6") (pintype "bidirectional"))
      (node (ref "R127") (pin "2") (pinfunction "P$2_2") (pintype "passive"))
    )
    (net (code "56") (name "L3") (class "Default")
      (node (ref "IC11") (pin "1") (pinfunction "OUTPUT_A_1") (pintype "bidirectional"))
      (node (ref "PIC32MK1024MCM100") (pin "97") (pinfunction "TRD0/PWM7H/PMA22/RG13_97") (pintype "bidirectional"))
      (node (ref "R163") (pin "1") (pinfunction "P$1_1") (pintype "passive"))
    )
    (net (code "57") (name "L3-IN") (class "Default")
      (node (ref "9") (pin "2") (pinfunction "E_2") (pintype "passive"))
      (node (ref "IC11") (pin "2") (pinfunction "INPUTS_A-_2") (pintype "bidirectional"))
      (node (ref "R128") (pin "2") (pinfunction "P$2_2") (pintype "passive"))
    )
    (net (code "58") (name "L4") (class "Default")
      (node (ref "IC11") (pin "7") (pinfunction "OUTPUT_B_7") (pintype "bidirectional"))
      (node (ref "PIC32MK1024MCM100") (pin "90") (pinfunction "RPG0/PMD8/RG0_90") (pintype "bidirectional"))
      (node (ref "R180") (pin "2") (pinfunction "P$2_2") (pintype "passive"))
    )
    (net (code "59") (name "L4-IN") (class "Default")
      (node (ref "10") (pin "2") (pinfunction "E_2") (pintype "passive"))
      (node (ref "IC11") (pin "6") (pinfunction "INPUTS_B-_6") (pintype "bidirectional"))
      (node (ref "R129") (pin "2") (pinfunction "P$2_2") (pintype "passive"))
    )
    (net (code "60") (name "L5") (class "Default")
      (node (ref "IC8") (pin "1") (pinfunction "OUTPUT_A_1") (pintype "bidirectional"))
      (node (ref "PIC32MK1024MCM100") (pin "89") (pinfunction "RPG1/PMD9/RG1_89") (pintype "bidirectional"))
      (node (ref "R174") (pin "1") (pinfunction "P$1_1") (pintype "passive"))
    )
    (net (code "61") (name "L5-IN") (class "Default")
      (node (ref "11") (pin "2") (pinfunction "E_2") (pintype "passive"))
      (node (ref "IC8") (pin "2") (pinfunction "INPUTS_A-_2") (pintype "bidirectional"))
      (node (ref "R130") (pin "2") (pinfunction "P$2_2") (pintype "passive"))
    )
    (net (code "62") (name "L6") (class "Default")
      (node (ref "IC8") (pin "7") (pinfunction "OUTPUT_B_7") (pintype "bidirectional"))
      (node (ref "PIC32MK1024MCM100") (pin "84") (pinfunction "RPC9/PMD15/RC9_84") (pintype "bidirectional"))
      (node (ref "R175") (pin "2") (pinfunction "P$2_2") (pintype "passive"))
    )
    (net (code "63") (name "L6-IN") (class "Default")
      (node (ref "12") (pin "2") (pinfunction "E_2") (pintype "passive"))
      (node (ref "IC8") (pin "6") (pinfunction "INPUTS_B-_6") (pintype "bidirectional"))
      (node (ref "R131") (pin "2") (pinfunction "P$2_2") (pintype "passive"))
    )
    (net (code "64") (name "L7") (class "Default")
      (node (ref "PIC32MK1024MCM100") (pin "83") (pinfunction "RPD6/PWM12L/PMD14/RD6_83") (pintype "bidirectional"))
    )
    (net (code "65") (name "L8") (class "Default")
      (node (ref "PIC32MK1024MCM100") (pin "82") (pinfunction "RPD5/PWM12H/PMRD/RD5_82") (pintype "bidirectional"))
    )
    (net (code "66") (name "LED_OUT") (class "Default")
      (node (ref "C12") (pin "1") (pinfunction "P$1_1") (pintype "passive"))
      (node (ref "R145") (pin "2") (pinfunction "P$2_2") (pintype "passive"))
      (node (ref "R172") (pin "2") (pinfunction "P$2_2") (pintype "passive"))
      (node (ref "R173") (pin "2") (pinfunction "P$2_2") (pintype "passive"))
      (node (ref "R18") (pin "2") (pinfunction "P$2_2") (pintype "passive"))
      (node (ref "R19") (pin "2") (pinfunction "P$2_2") (pintype "passive"))
      (node (ref "R198") (pin "2") (pinfunction "P$2_2") (pintype "passive"))
      (node (ref "R199") (pin "2") (pinfunction "P$2_2") (pintype "passive"))
      (node (ref "R20") (pin "2") (pinfunction "P$2_2") (pintype "passive"))
      (node (ref "R200") (pin "2") (pinfunction "P$2_2") (pintype "passive"))
      (node (ref "R205") (pin "2") (pinfunction "P$2_2") (pintype "passive"))
      (node (ref "R208") (pin "2") (pinfunction "P$2_2") (pintype "passive"))
      (node (ref "R209") (pin "2") (pinfunction "P$2_2") (pintype "passive"))
      (node (ref "R23") (pin "2") (pinfunction "P$2_2") (pintype "passive"))
      (node (ref "R24") (pin "2") (pinfunction "P$2_2") (pintype "passive"))
      (node (ref "R25") (pin "2") (pinfunction "P$2_2") (pintype "passive"))
      (node (ref "R26") (pin "2") (pinfunction "P$2_2") (pintype "passive"))
      (node (ref "R27") (pin "2") (pinfunction "P$2_2") (pintype "passive"))
      (node (ref "R28") (pin "2") (pinfunction "P$2_2") (pintype "passive"))
      (node (ref "R29") (pin "2") (pinfunction "P$2_2") (pintype "passive"))
      (node (ref "R30") (pin "2") (pinfunction "P$2_2") (pintype "passive"))
      (node (ref "R31") (pin "2") (pinfunction "P$2_2") (pintype "passive"))
      (node (ref "R32") (pin "2") (pinfunction "P$2_2") (pintype "passive"))
      (node (ref "R33") (pin "2") (pinfunction "P$2_2") (pintype "passive"))
      (node (ref "R34") (pin "2") (pinfunction "P$2_2") (pintype "passive"))
      (node (ref "R35") (pin "2") (pinfunction "P$2_2") (pintype "passive"))
      (node (ref "R36") (pin "2") (pinfunction "P$2_2") (pintype "passive"))
      (node (ref "R37") (pin "2") (pinfunction "P$2_2") (pintype "passive"))
      (node (ref "R38") (pin "2") (pinfunction "P$2_2") (pintype "passive"))
      (node (ref "R39") (pin "2") (pinfunction "P$2_2") (pintype "passive"))
      (node (ref "R40") (pin "2") (pinfunction "P$2_2") (pintype "passive"))
      (node (ref "R41") (pin "2") (pinfunction "P$2_2") (pintype "passive"))
      (node (ref "R42") (pin "2") (pinfunction "P$2_2") (pintype "passive"))
      (node (ref "R43") (pin "2") (pinfunction "P$2_2") (pintype "passive"))
      (node (ref "R44") (pin "2") (pinfunction "P$2_2") (pintype "passive"))
      (node (ref "R45") (pin "2") (pinfunction "P$2_2") (pintype "passive"))
      (node (ref "R46") (pin "2") (pinfunction "P$2_2") (pintype "passive"))
      (node (ref "R47") (pin "2") (pinfunction "P$2_2") (pintype "passive"))
      (node (ref "R48") (pin "2") (pinfunction "P$2_2") (pintype "passive"))
      (node (ref "R49") (pin "2") (pinfunction "P$2_2") (pintype "passive"))
      (node (ref "R5") (pin "2") (pinfunction "P$2_2") (pintype "passive"))
      (node (ref "R50") (pin "2") (pinfunction "P$2_2") (pintype "passive"))
      (node (ref "R51") (pin "2") (pinfunction "P$2_2") (pintype "passive"))
      (node (ref "R52") (pin "2") (pinfunction "P$2_2") (pintype "passive"))
      (node (ref "R53") (pin "2") (pinfunction "P$2_2") (pintype "passive"))
      (node (ref "R54") (pin "2") (pinfunction "P$2_2") (pintype "passive"))
      (node (ref "R55") (pin "2") (pinfunction "P$2_2") (pintype "passive"))
      (node (ref "R56") (pin "2") (pinfunction "P$2_2") (pintype "passive"))
      (node (ref "R57") (pin "2") (pinfunction "P$2_2") (pintype "passive"))
      (node (ref "R58") (pin "2") (pinfunction "P$2_2") (pintype "passive"))
      (node (ref "R59") (pin "2") (pinfunction "P$2_2") (pintype "passive"))
      (node (ref "R60") (pin "2") (pinfunction "P$2_2") (pintype "passive"))
      (node (ref "R61") (pin "2") (pinfunction "P$2_2") (pintype "passive"))
      (node (ref "R62") (pin "2") (pinfunction "P$2_2") (pintype "passive"))
      (node (ref "R63") (pin "2") (pinfunction "P$2_2") (pintype "passive"))
      (node (ref "R64") (pin "2") (pinfunction "P$2_2") (pintype "passive"))
      (node (ref "R65") (pin "2") (pinfunction "P$2_2") (pintype "passive"))
      (node (ref "R66") (pin "2") (pinfunction "P$2_2") (pintype "passive"))
      (node (ref "R67") (pin "2") (pinfunction "P$2_2") (pintype "passive"))
      (node (ref "R68") (pin "2") (pinfunction "P$2_2") (pintype "passive"))
      (node (ref "R69") (pin "2") (pinfunction "P$2_2") (pintype "passive"))
      (node (ref "R70") (pin "2") (pinfunction "P$2_2") (pintype "passive"))
      (node (ref "R71") (pin "2") (pinfunction "P$2_2") (pintype "passive"))
      (node (ref "R72") (pin "2") (pinfunction "P$2_2") (pintype "passive"))
      (node (ref "R73") (pin "2") (pinfunction "P$2_2") (pintype "passive"))
      (node (ref "R74") (pin "2") (pinfunction "P$2_2") (pintype "passive"))
      (node (ref "R75") (pin "2") (pinfunction "P$2_2") (pintype "passive"))
      (node (ref "R76") (pin "2") (pinfunction "P$2_2") (pintype "passive"))
      (node (ref "R77") (pin "2") (pinfunction "P$2_2") (pintype "passive"))
      (node (ref "R78") (pin "2") (pinfunction "P$2_2") (pintype "passive"))
      (node (ref "R79") (pin "2") (pinfunction "P$2_2") (pintype "passive"))
      (node (ref "R80") (pin "2") (pinfunction "P$2_2") (pintype "passive"))
      (node (ref "R81") (pin "2") (pinfunction "P$2_2") (pintype "passive"))
      (node (ref "R85") (pin "2") (pinfunction "P$2_2") (pintype "passive"))
      (node (ref "U$27") (pin "P$2") (pinfunction "C_P$2") (pintype "passive"))
      (node (ref "U1") (pin "2") (pinfunction "OUTPUT_2") (pintype "output"))
      (node (ref "U1") (pin "4") (pinfunction "EPAD_4") (pintype "passive"))
    )
    (net (code "67") (name "LL1") (class "Default")
      (node (ref "IC32") (pin "1") (pinfunction "OUTPUT_A_1") (pintype "bidirectional"))
      (node (ref "PIC32MK1024MCM100") (pin "95") (pinfunction "TRD2/PWM8H/PMA20/RG14_95") (pintype "bidirectional"))
      (node (ref "R190") (pin "1") (pinfunction "P$1_1") (pintype "passive"))
    )
    (net (code "68") (name "LL2") (class "Default")
      (node (ref "IC32") (pin "7") (pinfunction "OUTPUT_B_7") (pintype "bidirectional"))
      (node (ref "PIC32MK1024MCM100") (pin "92") (pinfunction "TRD3/PWM9L/PMA19/RF7_92") (pintype "bidirectional"))
      (node (ref "R191") (pin "2") (pinfunction "P$2_2") (pintype "passive"))
    )
    (net (code "69") (name "LL3") (class "Default")
      (node (ref "IC3") (pin "1") (pinfunction "OUTPUT_A_1") (pintype "bidirectional"))
      (node (ref "PIC32MK1024MCM100") (pin "96") (pinfunction "TRD1/RPG12/PWM8L/PMA21/RG12_96") (pintype "bidirectional"))
      (node (ref "R192") (pin "1") (pinfunction "P$1_1") (pintype "passive"))
    )
    (net (code "70") (name "LR1-IN") (class "Default")
      (node (ref "59") (pin "2") (pinfunction "E_2") (pintype "passive"))
      (node (ref "IC32") (pin "2") (pinfunction "INPUTS_A-_2") (pintype "bidirectional"))
      (node (ref "R82") (pin "2") (pinfunction "P$2_2") (pintype "passive"))
    )
    (net (code "71") (name "LR2-IN") (class "Default")
      (node (ref "60") (pin "2") (pinfunction "E_2") (pintype "passive"))
      (node (ref "IC32") (pin "6") (pinfunction "INPUTS_B-_6") (pintype "bidirectional"))
      (node (ref "R83") (pin "2") (pinfunction "P$2_2") (pintype "passive"))
    )
    (net (code "72") (name "LR3-IN") (class "Default")
      (node (ref "61") (pin "2") (pinfunction "E_2") (pintype "passive"))
      (node (ref "IC3") (pin "2") (pinfunction "INPUTS_A-_2") (pintype "bidirectional"))
      (node (ref "R84") (pin "2") (pinfunction "P$2_2") (pintype "passive"))
    )
    (net (code "73") (name "LR4-IN") (class "Default")
      (node (ref "IC3") (pin "6") (pinfunction "INPUTS_B-_6") (pintype "bidirectional"))
    )
    (net (code "74") (name "MCLR") (class "Default")
      (node (ref "MCLR") (pin "1") (pinfunction "P$1_1") (pintype "bidirectional"))
      (node (ref "PIC32MK1024MCM100") (pin "13") (pinfunction "~{MCLR}_13") (pintype "bidirectional"))
      (node (ref "R3") (pin "1") (pinfunction "P$1_1") (pintype "passive"))
    )
    (net (code "75") (name "Net-(PIC32MK1024MCM100-D1+)") (class "Default")
      (node (ref "PIC32MK1024MCM100") (pin "57") (pinfunction "D1+_57") (pintype "bidirectional"))
      (node (ref "R167") (pin "1") (pinfunction "P$1_1") (pintype "passive"))
    )
    (net (code "76") (name "Net-(PIC32MK1024MCM100-D1-)") (class "Default")
      (node (ref "PIC32MK1024MCM100") (pin "56") (pinfunction "D1-_56") (pintype "bidirectional"))
      (node (ref "R178") (pin "1") (pinfunction "P$1_1") (pintype "passive"))
    )
    (net (code "77") (name "Net-(PIC32MK1024MCM100-D2+)") (class "Default")
      (node (ref "PIC32MK1024MCM100") (pin "60") (pinfunction "D2+_60") (pintype "bidirectional"))
      (node (ref "R166") (pin "1") (pinfunction "P$1_1") (pintype "passive"))
    )
    (net (code "78") (name "Net-(PIC32MK1024MCM100-D2-)") (class "Default")
      (node (ref "PIC32MK1024MCM100") (pin "59") (pinfunction "D2-_59") (pintype "bidirectional"))
      (node (ref "R143") (pin "1") (pinfunction "P$1_1") (pintype "passive"))
    )
    (net (code "79") (name "Net-(R1-P$1)") (class "Default")
      (node (ref "+3.3V") (pin "A") (pinfunction "A_A") (pintype "passive"))
      (node (ref "R1") (pin "1") (pinfunction "P$1_1") (pintype "passive"))
    )
    (net (code "80") (name "Net-(R5-P$1)") (class "Default")
      (node (ref "R5") (pin "1") (pinfunction "P$1_1") (pintype "passive"))
      (node (ref "U$9") (pin "5") (pinfunction "W_5") (pintype "bidirectional"))
      (node (ref "U1") (pin "1") (pinfunction "ADJ/GND_1") (pintype "bidirectional"))
    )
    (net (code "81") (name "Net-(R18-P$1)") (class "Default")
      (node (ref "D70") (pin "A") (pinfunction "A_A") (pintype "passive"))
      (node (ref "R18") (pin "1") (pinfunction "P$1_1") (pintype "passive"))
    )
    (net (code "82") (name "Net-(R19-P$1)") (class "Default")
      (node (ref "D71") (pin "A") (pinfunction "A_A") (pintype "passive"))
      (node (ref "R19") (pin "1") (pinfunction "P$1_1") (pintype "passive"))
    )
    (net (code "83") (name "Net-(R20-P$1)") (class "Default")
      (node (ref "D62") (pin "A") (pinfunction "A_A") (pintype "passive"))
      (node (ref "R20") (pin "1") (pinfunction "P$1_1") (pintype "passive"))
    )
    (net (code "84") (name "Net-(R23-P$1)") (class "Default")
      (node (ref "D20") (pin "A") (pinfunction "A_A") (pintype "passive"))
      (node (ref "R23") (pin "1") (pinfunction "P$1_1") (pintype "passive"))
    )
    (net (code "85") (name "Net-(R24-P$1)") (class "Default")
      (node (ref "D21") (pin "A") (pinfunction "A_A") (pintype "passive"))
      (node (ref "R24") (pin "1") (pinfunction "P$1_1") (pintype "passive"))
    )
    (net (code "86") (name "Net-(R25-P$1)") (class "Default")
      (node (ref "D22") (pin "A") (pinfunction "A_A") (pintype "passive"))
      (node (ref "R25") (pin "1") (pinfunction "P$1_1") (pintype "passive"))
    )
    (net (code "87") (name "Net-(R26-P$1)") (class "Default")
      (node (ref "D23") (pin "A") (pinfunction "A_A") (pintype "passive"))
      (node (ref "R26") (pin "1") (pinfunction "P$1_1") (pintype "passive"))
    )
    (net (code "88") (name "Net-(R27-P$1)") (class "Default")
      (node (ref "D24") (pin "A") (pinfunction "A_A") (pintype "passive"))
      (node (ref "R27") (pin "1") (pinfunction "P$1_1") (pintype "passive"))
    )
    (net (code "89") (name "Net-(R28-P$1)") (class "Default")
      (node (ref "D25") (pin "A") (pinfunction "A_A") (pintype "passive"))
      (node (ref "R28") (pin "1") (pinfunction "P$1_1") (pintype "passive"))
    )
    (net (code "90") (name "Net-(R29-P$1)") (class "Default")
      (node (ref "D26") (pin "A") (pinfunction "A_A") (pintype "passive"))
      (node (ref "R29") (pin "1") (pinfunction "P$1_1") (pintype "passive"))
    )
    (net (code "91") (name "Net-(R30-P$1)") (class "Default")
      (node (ref "D27") (pin "A") (pinfunction "A_A") (pintype "passive"))
      (node (ref "R30") (pin "1") (pinfunction "P$1_1") (pintype "passive"))
    )
    (net (code "92") (name "Net-(R31-P$1)") (class "Default")
      (node (ref "D28") (pin "A") (pinfunction "A_A") (pintype "passive"))
      (node (ref "R31") (pin "1") (pinfunction "P$1_1") (pintype "passive"))
    )
    (net (code "93") (name "Net-(R32-P$1)") (class "Default")
      (node (ref "D29") (pin "A") (pinfunction "A_A") (pintype "passive"))
      (node (ref "R32") (pin "1") (pinfunction "P$1_1") (pintype "passive"))
    )
    (net (code "94") (name "Net-(R33-P$1)") (class "Default")
      (node (ref "D30") (pin "A") (pinfunction "A_A") (pintype "passive"))
      (node (ref "R33") (pin "1") (pinfunction "P$1_1") (pintype "passive"))
    )
    (net (code "95") (name "Net-(R34-P$1)") (class "Default")
      (node (ref "D31") (pin "A") (pinfunction "A_A") (pintype "passive"))
      (node (ref "R34") (pin "1") (pinfunction "P$1_1") (pintype "passive"))
    )
    (net (code "96") (name "Net-(R35-P$1)") (class "Default")
      (node (ref "D32") (pin "A") (pinfunction "A_A") (pintype "passive"))
      (node (ref "R35") (pin "1") (pinfunction "P$1_1") (pintype "passive"))
    )
    (net (code "97") (name "Net-(R36-P$1)") (class "Default")
      (node (ref "D33") (pin "A") (pinfunction "A_A") (pintype "passive"))
      (node (ref "R36") (pin "1") (pinfunction "P$1_1") (pintype "passive"))
    )
    (net (code "98") (name "Net-(R37-P$1)") (class "Default")
      (node (ref "D34") (pin "A") (pinfunction "A_A") (pintype "passive"))
      (node (ref "R37") (pin "1") (pinfunction "P$1_1") (pintype "passive"))
    )
    (net (code "99") (name "Net-(R38-P$1)") (class "Default")
      (node (ref "D35") (pin "A") (pinfunction "A_A") (pintype "passive"))
      (node (ref "R38") (pin "1") (pinfunction "P$1_1") (pintype "passive"))
    )
    (net (code "100") (name "Net-(R39-P$1)") (class "Default")
      (node (ref "D36") (pin "A") (pinfunction "A_A") (pintype "passive"))
      (node (ref "R39") (pin "1") (pinfunction "P$1_1") (pintype "passive"))
    )
    (net (code "101") (name "Net-(R40-P$1)") (class "Default")
      (node (ref "D37") (pin "A") (pinfunction "A_A") (pintype "passive"))
      (node (ref "R40") (pin "1") (pinfunction "P$1_1") (pintype "passive"))
    )
    (net (code "102") (name "Net-(R41-P$1)") (class "Default")
      (node (ref "D38") (pin "A") (pinfunction "A_A") (pintype "passive"))
      (node (ref "R41") (pin "1") (pinfunction "P$1_1") (pintype "passive"))
    )
    (net (code "103") (name "Net-(R42-P$1)") (class "Default")
      (node (ref "D39") (pin "A") (pinfunction "A_A") (pintype "passive"))
      (node (ref "R42") (pin "1") (pinfunction "P$1_1") (pintype "passive"))
    )
    (net (code "104") (name "Net-(R43-P$1)") (class "Default")
      (node (ref "D40") (pin "A") (pinfunction "A_A") (pintype "passive"))
      (node (ref "R43") (pin "1") (pinfunction "P$1_1") (pintype "passive"))
    )
    (net (code "105") (name "Net-(R44-P$1)") (class "Default")
      (node (ref "D41") (pin "A") (pinfunction "A_A") (pintype "passive"))
      (node (ref "R44") (pin "1") (pinfunction "P$1_1") (pintype "passive"))
    )
    (net (code "106") (name "Net-(R45-P$1)") (class "Default")
      (node (ref "D42") (pin "A") (pinfunction "A_A") (pintype "passive"))
      (node (ref "R45") (pin "1") (pinfunction "P$1_1") (pintype "passive"))
    )
    (net (code "107") (name "Net-(R46-P$1)") (class "Default")
      (node (ref "D43") (pin "A") (pinfunction "A_A") (pintype "passive"))
      (node (ref "R46") (pin "1") (pinfunction "P$1_1") (pintype "passive"))
    )
    (net (code "108") (name "Net-(R47-P$1)") (class "Default")
      (node (ref "D44") (pin "A") (pinfunction "A_A") (pintype "passive"))
      (node (ref "R47") (pin "1") (pinfunction "P$1_1") (pintype "passive"))
    )
    (net (code "109") (name "Net-(R48-P$1)") (class "Default")
      (node (ref "D45") (pin "A") (pinfunction "A_A") (pintype "passive"))
      (node (ref "R48") (pin "1") (pinfunction "P$1_1") (pintype "passive"))
    )
    (net (code "110") (name "Net-(R49-P$1)") (class "Default")
      (node (ref "D46") (pin "A") (pinfunction "A_A") (pintype "passive"))
      (node (ref "R49") (pin "1") (pinfunction "P$1_1") (pintype "passive"))
    )
    (net (code "111") (name "Net-(R50-P$1)") (class "Default")
      (node (ref "D47") (pin "A") (pinfunction "A_A") (pintype "passive"))
      (node (ref "R50") (pin "1") (pinfunction "P$1_1") (pintype "passive"))
    )
    (net (code "112") (name "Net-(R51-P$1)") (class "Default")
      (node (ref "D48") (pin "A") (pinfunction "A_A") (pintype "passive"))
      (node (ref "R51") (pin "1") (pinfunction "P$1_1") (pintype "passive"))
    )
    (net (code "113") (name "Net-(R52-P$1)") (class "Default")
      (node (ref "D49") (pin "A") (pinfunction "A_A") (pintype "passive"))
      (node (ref "R52") (pin "1") (pinfunction "P$1_1") (pintype "passive"))
    )
    (net (code "114") (name "Net-(R53-P$1)") (class "Default")
      (node (ref "D50") (pin "A") (pinfunction "A_A") (pintype "passive"))
      (node (ref "R53") (pin "1") (pinfunction "P$1_1") (pintype "passive"))
    )
    (net (code "115") (name "Net-(R54-P$1)") (class "Default")
      (node (ref "D51") (pin "A") (pinfunction "A_A") (pintype "passive"))
      (node (ref "R54") (pin "1") (pinfunction "P$1_1") (pintype "passive"))
    )
    (net (code "116") (name "Net-(R55-P$1)") (class "Default")
      (node (ref "D2") (pin "A") (pinfunction "A_A") (pintype "passive"))
      (node (ref "R55") (pin "1") (pinfunction "P$1_1") (pintype "passive"))
    )
    (net (code "117") (name "Net-(R56-P$1)") (class "Default")
      (node (ref "D3") (pin "A") (pinfunction "A_A") (pintype "passive"))
      (node (ref "R56") (pin "1") (pinfunction "P$1_1") (pintype "passive"))
    )
    (net (code "118") (name "Net-(R57-P$1)") (class "Default")
      (node (ref "D4") (pin "A") (pinfunction "A_A") (pintype "passive"))
      (node (ref "R57") (pin "1") (pinfunction "P$1_1") (pintype "passive"))
    )
    (net (code "119") (name "Net-(R58-P$1)") (class "Default")
      (node (ref "D5") (pin "A") (pinfunction "A_A") (pintype "passive"))
      (node (ref "R58") (pin "1") (pinfunction "P$1_1") (pintype "passive"))
    )
    (net (code "120") (name "Net-(R59-P$1)") (class "Default")
      (node (ref "D6") (pin "A") (pinfunction "A_A") (pintype "passive"))
      (node (ref "R59") (pin "1") (pinfunction "P$1_1") (pintype "passive"))
    )
    (net (code "121") (name "Net-(R60-P$1)") (class "Default")
      (node (ref "D7") (pin "A") (pinfunction "A_A") (pintype "passive"))
      (node (ref "R60") (pin "1") (pinfunction "P$1_1") (pintype "passive"))
    )
    (net (code "122") (name "Net-(R61-P$1)") (class "Default")
      (node (ref "D8") (pin "A") (pinfunction "A_A") (pintype "passive"))
      (node (ref "R61") (pin "1") (pinfunction "P$1_1") (pintype "passive"))
    )
    (net (code "123") (name "Net-(R62-P$1)") (class "Default")
      (node (ref "D9") (pin "A") (pinfunction "A_A") (pintype "passive"))
      (node (ref "R62") (pin "1") (pinfunction "P$1_1") (pintype "passive"))
    )
    (net (code "124") (name "Net-(R63-P$1)") (class "Default")
      (node (ref "D10") (pin "A") (pinfunction "A_A") (pintype "passive"))
      (node (ref "R63") (pin "1") (pinfunction "P$1_1") (pintype "passive"))
    )
    (net (code "125") (name "Net-(R64-P$1)") (class "Default")
      (node (ref "D11") (pin "A") (pinfunction "A_A") (pintype "passive"))
      (node (ref "R64") (pin "1") (pinfunction "P$1_1") (pintype "passive"))
    )
    (net (code "126") (name "Net-(R65-P$1)") (class "Default")
      (node (ref "D12") (pin "A") (pinfunction "A_A") (pintype "passive"))
      (node (ref "R65") (pin "1") (pinfunction "P$1_1") (pintype "passive"))
    )
    (net (code "127") (name "Net-(R66-P$1)") (class "Default")
      (node (ref "D13") (pin "A") (pinfunction "A_A") (pintype "passive"))
      (node (ref "R66") (pin "1") (pinfunction "P$1_1") (pintype "passive"))
    )
    (net (code "128") (name "Net-(R67-P$1)") (class "Default")
      (node (ref "D14") (pin "A") (pinfunction "A_A") (pintype "passive"))
      (node (ref "R67") (pin "1") (pinfunction "P$1_1") (pintype "passive"))
    )
    (net (code "129") (name "Net-(R68-P$1)") (class "Default")
      (node (ref "D15") (pin "A") (pinfunction "A_A") (pintype "passive"))
      (node (ref "R68") (pin "1") (pinfunction "P$1_1") (pintype "passive"))
    )
    (net (code "130") (name "Net-(R69-P$1)") (class "Default")
      (node (ref "D16") (pin "A") (pinfunction "A_A") (pintype "passive"))
      (node (ref "R69") (pin "1") (pinfunction "P$1_1") (pintype "passive"))
    )
    (net (code "131") (name "Net-(R70-P$1)") (class "Default")
      (node (ref "D17") (pin "A") (pinfunction "A_A") (pintype "passive"))
      (node (ref "R70") (pin "1") (pinfunction "P$1_1") (pintype "passive"))
    )
    (net (code "132") (name "Net-(R71-P$1)") (class "Default")
      (node (ref "D18") (pin "A") (pinfunction "A_A") (pintype "passive"))
      (node (ref "R71") (pin "1") (pinfunction "P$1_1") (pintype "passive"))
    )
    (net (code "133") (name "Net-(R72-P$1)") (class "Default")
      (node (ref "D19") (pin "A") (pinfunction "A_A") (pintype "passive"))
      (node (ref "R72") (pin "1") (pinfunction "P$1_1") (pintype "passive"))
    )
    (net (code "134") (name "Net-(R73-P$1)") (class "Default")
      (node (ref "D52") (pin "A") (pinfunction "A_A") (pintype "passive"))
      (node (ref "R73") (pin "1") (pinfunction "P$1_1") (pintype "passive"))
    )
    (net (code "135") (name "Net-(R74-P$1)") (class "Default")
      (node (ref "D53") (pin "A") (pinfunction "A_A") (pintype "passive"))
      (node (ref "R74") (pin "1") (pinfunction "P$1_1") (pintype "passive"))
    )
    (net (code "136") (name "Net-(R75-P$1)") (class "Default")
      (node (ref "D54") (pin "A") (pinfunction "A_A") (pintype "passive"))
      (node (ref "R75") (pin "1") (pinfunction "P$1_1") (pintype "passive"))
    )
    (net (code "137") (name "Net-(R76-P$1)") (class "Default")
      (node (ref "D1") (pin "A") (pinfunction "A_A") (pintype "passive"))
      (node (ref "R76") (pin "1") (pinfunction "P$1_1") (pintype "passive"))
    )
    (net (code "138") (name "Net-(R77-P$1)") (class "Default")
      (node (ref "D55") (pin "A") (pinfunction "A_A") (pintype "passive"))
      (node (ref "R77") (pin "1") (pinfunction "P$1_1") (pintype "passive"))
    )
    (net (code "139") (name "Net-(R78-P$1)") (class "Default")
      (node (ref "D56") (pin "A") (pinfunction "A_A") (pintype "passive"))
      (node (ref "R78") (pin "1") (pinfunction "P$1_1") (pintype "passive"))
    )
    (net (code "140") (name "Net-(R79-P$1)") (class "Default")
      (node (ref "D57") (pin "A") (pinfunction "A_A") (pintype "passive"))
      (node (ref "R79") (pin "1") (pinfunction "P$1_1") (pintype "passive"))
    )
    (net (code "141") (name "Net-(R80-P$1)") (class "Default")
      (node (ref "D58") (pin "A") (pinfunction "A_A") (pintype "passive"))
      (node (ref "R80") (pin "1") (pinfunction "P$1_1") (pintype "passive"))
    )
    (net (code "142") (name "Net-(R81-P$1)") (class "Default")
      (node (ref "D59") (pin "A") (pinfunction "A_A") (pintype "passive"))
      (node (ref "R81") (pin "1") (pinfunction "P$1_1") (pintype "passive"))
    )
    (net (code "143") (name "Net-(R85-P$1)") (class "Default")
      (node (ref "D72") (pin "A") (pinfunction "A_A") (pintype "passive"))
      (node (ref "R85") (pin "1") (pinfunction "P$1_1") (pintype "passive"))
    )
    (net (code "144") (name "Net-(R145-P$1)") (class "Default")
      (node (ref "D67") (pin "A") (pinfunction "A_A") (pintype "passive"))
      (node (ref "R145") (pin "1") (pinfunction "P$1_1") (pintype "passive"))
    )
    (net (code "145") (name "Net-(R172-P$1)") (class "Default")
      (node (ref "D68") (pin "A") (pinfunction "A_A") (pintype "passive"))
      (node (ref "R172") (pin "1") (pinfunction "P$1_1") (pintype "passive"))
    )
    (net (code "146") (name "Net-(R173-P$1)") (class "Default")
      (node (ref "D69") (pin "A") (pinfunction "A_A") (pintype "passive"))
      (node (ref "R173") (pin "1") (pinfunction "P$1_1") (pintype "passive"))
    )
    (net (code "147") (name "Net-(R198-P$1)") (class "Default")
      (node (ref "D60") (pin "A") (pinfunction "A_A") (pintype "passive"))
      (node (ref "R198") (pin "1") (pinfunction "P$1_1") (pintype "passive"))
    )
    (net (code "148") (name "Net-(R199-P$1)") (class "Default")
      (node (ref "D61") (pin "A") (pinfunction "A_A") (pintype "passive"))
      (node (ref "R199") (pin "1") (pinfunction "P$1_1") (pintype "passive"))
    )
    (net (code "149") (name "Net-(R200-P$1)") (class "Default")
      (node (ref "D63") (pin "A") (pinfunction "A_A") (pintype "passive"))
      (node (ref "R200") (pin "1") (pinfunction "P$1_1") (pintype "passive"))
    )
    (net (code "150") (name "Net-(R205-P$1)") (class "Default")
      (node (ref "D64") (pin "A") (pinfunction "A_A") (pintype "passive"))
      (node (ref "R205") (pin "1") (pinfunction "P$1_1") (pintype "passive"))
    )
    (net (code "151") (name "Net-(R208-P$1)") (class "Default")
      (node (ref "D65") (pin "A") (pinfunction "A_A") (pintype "passive"))
      (node (ref "R208") (pin "1") (pinfunction "P$1_1") (pintype "passive"))
    )
    (net (code "152") (name "Net-(R209-P$1)") (class "Default")
      (node (ref "D66") (pin "A") (pinfunction "A_A") (pintype "passive"))
      (node (ref "R209") (pin "1") (pinfunction "P$1_1") (pintype "passive"))
    )
    (net (code "153") (name "Net-(U$3-P$2)") (class "Default")
      (node (ref "U$3") (pin "2") (pinfunction "P$2_2") (pintype "bidirectional"))
      (node (ref "U$57") (pin "P$1") (pinfunction "A_P$1") (pintype "passive"))
    )
    (net (code "154") (name "OUT_5V") (class "Default")
      (node (ref "C11") (pin "1") (pinfunction "P$1_1") (pintype "passive"))
      (node (ref "C3") (pin "1") (pinfunction "P$1_1") (pintype "passive"))
      (node (ref "C47") (pin "1") (pinfunction "P$1_1") (pintype "passive"))
      (node (ref "IC1") (pin "3") (pinfunction "INPUT_3") (pintype "bidirectional"))
      (node (ref "LED1") (pin "1") (pinfunction "VDD_1") (pintype "bidirectional"))
      (node (ref "R207") (pin "2") (pinfunction "P$2_2") (pintype "passive"))
      (node (ref "U$57") (pin "P$2") (pinfunction "C_P$2") (pintype "passive"))
      (node (ref "U1") (pin "3") (pinfunction "INPUT_3") (pintype "input"))
    )
    (net (code "155") (name "PGC") (class "Default")
      (node (ref "MCLR") (pin "5") (pinfunction "P$5_5") (pintype "bidirectional"))
      (node (ref "PIC32MK1024MCM100") (pin "25") (pinfunction "PGC3/OA1OUT/AN3/C1IN4-/C4IN2-/RPB1/CTED1/RB1_25") (pintype "bidirectional"))
    )
    (net (code "156") (name "PGD") (class "Default")
      (node (ref "MCLR") (pin "4") (pinfunction "P$4_4") (pintype "bidirectional"))
      (node (ref "PIC32MK1024MCM100") (pin "24") (pinfunction "PGD3/OA2IN-/AN2/C2IN1-/RPB0/CTED2/RB0_24") (pintype "bidirectional"))
    )
    (net (code "157") (name "R1") (class "Default")
      (node (ref "IC27") (pin "1") (pinfunction "OUTPUT_A_1") (pintype "bidirectional"))
      (node (ref "PIC32MK1024MCM100") (pin "35") (pinfunction "AN11/CVD11/C1IN2-/FLT4/PMA12/RC11_35") (pintype "bidirectional"))
      (node (ref "R164") (pin "1") (pinfunction "P$1_1") (pintype "passive"))
    )
    (net (code "158") (name "R1-IN") (class "Default")
      (node (ref "1") (pin "2") (pinfunction "E_2") (pintype "passive"))
      (node (ref "IC27") (pin "2") (pinfunction "INPUTS_A-_2") (pintype "bidirectional"))
      (node (ref "R120") (pin "2") (pinfunction "P$2_2") (pintype "passive"))
    )
    (net (code "159") (name "R2") (class "Default")
      (node (ref "IC27") (pin "7") (pinfunction "OUTPUT_B_7") (pintype "bidirectional"))
      (node (ref "PIC32MK1024MCM100") (pin "38") (pinfunction "AN35/CVD35/RG11_38") (pintype "bidirectional"))
      (node (ref "R165") (pin "2") (pinfunction "P$2_2") (pintype "passive"))
    )
    (net (code "160") (name "R2-IN") (class "Default")
      (node (ref "2") (pin "2") (pinfunction "E_2") (pintype "passive"))
      (node (ref "IC27") (pin "6") (pinfunction "INPUTS_B-_6") (pintype "bidirectional"))
      (node (ref "R121") (pin "2") (pinfunction "P$2_2") (pintype "passive"))
    )
    (net (code "161") (name "R3") (class "Default")
      (node (ref "IC33") (pin "1") (pinfunction "OUTPUT_A_1") (pintype "bidirectional"))
      (node (ref "PIC32MK1024MCM100") (pin "29") (pinfunction "VREF+/AN34/CVD34/PMA6/RF10_29") (pintype "bidirectional"))
      (node (ref "R181") (pin "1") (pinfunction "P$1_1") (pintype "passive"))
    )
    (net (code "162") (name "R3-IN") (class "Default")
      (node (ref "3") (pin "2") (pinfunction "E_2") (pintype "passive"))
      (node (ref "IC33") (pin "2") (pinfunction "INPUTS_A-_2") (pintype "bidirectional"))
      (node (ref "R122") (pin "2") (pinfunction "P$2_2") (pintype "passive"))
    )
    (net (code "163") (name "R4") (class "Default")
      (node (ref "IC33") (pin "7") (pinfunction "OUTPUT_B_7") (pintype "bidirectional"))
      (node (ref "PIC32MK1024MCM100") (pin "32") (pinfunction "OA3OUT/AN6/CVD6/C3IN4-/C4IN1+/C4IN4-/RPC0/RC0_32") (pintype "bidirectional"))
      (node (ref "R194") (pin "2") (pinfunction "P$2_2") (pintype "passive"))
    )
    (net (code "164") (name "R4-IN") (class "Default")
      (node (ref "4") (pin "2") (pinfunction "E_2") (pintype "passive"))
      (node (ref "IC33") (pin "6") (pinfunction "INPUTS_B-_6") (pintype "bidirectional"))
      (node (ref "R123") (pin "2") (pinfunction "P$2_2") (pintype "passive"))
    )
    (net (code "165") (name "R5") (class "Default")
      (node (ref "IC5") (pin "1") (pinfunction "OUTPUT_A_1") (pintype "bidirectional"))
      (node (ref "PIC32MK1024MCM100") (pin "52") (pinfunction "AN40/CVD40/RPE0/RE0_52") (pintype "bidirectional"))
      (node (ref "R168") (pin "1") (pinfunction "P$1_1") (pintype "passive"))
    )
    (net (code "166") (name "R5-IN") (class "Default")
      (node (ref "5") (pin "2") (pinfunction "E_2") (pintype "passive"))
      (node (ref "IC5") (pin "2") (pinfunction "INPUTS_A-_2") (pintype "bidirectional"))
      (node (ref "R124") (pin "2") (pinfunction "P$2_2") (pintype "passive"))
    )
    (net (code "167") (name "R6") (class "Default")
      (node (ref "IC5") (pin "7") (pinfunction "OUTPUT_B_7") (pintype "bidirectional"))
      (node (ref "PIC32MK1024MCM100") (pin "53") (pinfunction "AN41/CVD41/RPE1/RE1_53") (pintype "bidirectional"))
      (node (ref "R169") (pin "2") (pinfunction "P$2_2") (pintype "passive"))
    )
    (net (code "168") (name "R6-IN") (class "Default")
      (node (ref "6") (pin "2") (pinfunction "E_2") (pintype "passive"))
      (node (ref "IC5") (pin "6") (pinfunction "INPUTS_B-_6") (pintype "bidirectional"))
      (node (ref "R125") (pin "2") (pinfunction "P$2_2") (pintype "passive"))
    )
    (net (code "169") (name "RR1") (class "Default")
      (node (ref "IC2") (pin "1") (pinfunction "OUTPUT_A_1") (pintype "bidirectional"))
      (node (ref "PIC32MK1024MCM100") (pin "50") (pinfunction "FLT15/RPB4/SCL2/PMA8/RB4_50") (pintype "bidirectional"))
      (node (ref "R182") (pin "1") (pinfunction "P$1_1") (pintype "passive"))
    )
    (net (code "170") (name "RR1-IN") (class "Default")
      (node (ref "51") (pin "2") (pinfunction "E_2") (pintype "passive"))
      (node (ref "IC2") (pin "2") (pinfunction "INPUTS_A-_2") (pintype "bidirectional"))
      (node (ref "R138") (pin "2") (pinfunction "P$2_2") (pintype "passive"))
    )
    (net (code "171") (name "RR2") (class "Default")
      (node (ref "IC2") (pin "7") (pinfunction "OUTPUT_B_7") (pintype "bidirectional"))
      (node (ref "PIC32MK1024MCM100") (pin "40") (pinfunction "AN37/CVD37/RF12_40") (pintype "bidirectional"))
      (node (ref "R183") (pin "2") (pinfunction "P$2_2") (pintype "passive"))
    )
    (net (code "172") (name "RR2-IN") (class "Default")
      (node (ref "52") (pin "2") (pinfunction "E_2") (pintype "passive"))
      (node (ref "IC2") (pin "6") (pinfunction "INPUTS_B-_6") (pintype "bidirectional"))
      (node (ref "R139") (pin "2") (pinfunction "P$2_2") (pintype "passive"))
    )
    (net (code "173") (name "RR3") (class "Default")
      (node (ref "IC30") (pin "1") (pinfunction "OUTPUT_A_1") (pintype "bidirectional"))
      (node (ref "PIC32MK1024MCM100") (pin "51") (pinfunction "OA5IN+/DAC1/AN24/CVD24/C5IN1+/C5IN3-/RPA4/RA4_51") (pintype "bidirectional"))
      (node (ref "R184") (pin "1") (pinfunction "P$1_1") (pintype "passive"))
    )
    (net (code "174") (name "RR3-IN") (class "Default")
      (node (ref "57") (pin "2") (pinfunction "E_2") (pintype "passive"))
      (node (ref "IC30") (pin "2") (pinfunction "INPUTS_A-_2") (pintype "bidirectional"))
      (node (ref "R144") (pin "2") (pinfunction "P$2_2") (pintype "passive"))
    )
    (net (code "175") (name "RR4") (class "Default")
      (node (ref "PIC32MK1024MCM100") (pin "39") (pinfunction "AN36/CVD36/RF13_39") (pintype "bidirectional"))
    )
    (net (code "176") (name "S1-IN") (class "Default")
      (node (ref "19") (pin "2") (pinfunction "E_2") (pintype "passive"))
      (node (ref "IC12") (pin "2") (pinfunction "INPUTS_A-_2") (pintype "bidirectional"))
      (node (ref "R88") (pin "2") (pinfunction "P$2_2") (pintype "passive"))
    )
    (net (code "177") (name "S2-IN") (class "Default")
      (node (ref "20") (pin "2") (pinfunction "E_2") (pintype "passive"))
      (node (ref "IC12") (pin "6") (pinfunction "INPUTS_B-_6") (pintype "bidirectional"))
      (node (ref "R89") (pin "2") (pinfunction "P$2_2") (pintype "passive"))
    )
    (net (code "178") (name "S3-IN") (class "Default")
      (node (ref "21") (pin "2") (pinfunction "E_2") (pintype "passive"))
      (node (ref "IC13") (pin "2") (pinfunction "INPUTS_A-_2") (pintype "bidirectional"))
      (node (ref "R90") (pin "2") (pinfunction "P$2_2") (pintype "passive"))
    )
    (net (code "179") (name "S4-IN") (class "Default")
      (node (ref "22") (pin "2") (pinfunction "E_2") (pintype "passive"))
      (node (ref "IC13") (pin "6") (pinfunction "INPUTS_B-_6") (pintype "bidirectional"))
      (node (ref "R91") (pin "2") (pinfunction "P$2_2") (pintype "passive"))
    )
    (net (code "180") (name "S5-IN") (class "Default")
      (node (ref "23") (pin "2") (pinfunction "E_2") (pintype "passive"))
      (node (ref "IC14") (pin "2") (pinfunction "INPUTS_A-_2") (pintype "bidirectional"))
      (node (ref "R92") (pin "2") (pinfunction "P$2_2") (pintype "passive"))
    )
    (net (code "181") (name "S6-IN") (class "Default")
      (node (ref "24") (pin "2") (pinfunction "E_2") (pintype "passive"))
      (node (ref "IC14") (pin "6") (pinfunction "INPUTS_B-_6") (pintype "bidirectional"))
      (node (ref "R93") (pin "2") (pinfunction "P$2_2") (pintype "passive"))
    )
    (net (code "182") (name "S7-IN") (class "Default")
      (node (ref "25") (pin "2") (pinfunction "E_2") (pintype "passive"))
      (node (ref "IC15") (pin "2") (pinfunction "INPUTS_A-_2") (pintype "bidirectional"))
      (node (ref "R94") (pin "2") (pinfunction "P$2_2") (pintype "passive"))
    )
    (net (code "183") (name "S8-IN") (class "Default")
      (node (ref "26") (pin "2") (pinfunction "E_2") (pintype "passive"))
      (node (ref "IC15") (pin "6") (pinfunction "INPUTS_B-_6") (pintype "bidirectional"))
      (node (ref "R95") (pin "2") (pinfunction "P$2_2") (pintype "passive"))
    )
    (net (code "184") (name "S9-IN") (class "Default")
      (node (ref "27") (pin "2") (pinfunction "E_2") (pintype "passive"))
      (node (ref "IC16") (pin "2") (pinfunction "INPUTS_A-_2") (pintype "bidirectional"))
      (node (ref "R96") (pin "2") (pinfunction "P$2_2") (pintype "passive"))
    )
    (net (code "185") (name "S10-IN") (class "Default")
      (node (ref "28") (pin "2") (pinfunction "E_2") (pintype "passive"))
      (node (ref "IC16") (pin "6") (pinfunction "INPUTS_B-_6") (pintype "bidirectional"))
      (node (ref "R97") (pin "2") (pinfunction "P$2_2") (pintype "passive"))
    )
    (net (code "186") (name "S11-IN") (class "Default")
      (node (ref "29") (pin "2") (pinfunction "E_2") (pintype "passive"))
      (node (ref "IC17") (pin "2") (pinfunction "INPUTS_A-_2") (pintype "bidirectional"))
      (node (ref "R98") (pin "2") (pinfunction "P$2_2") (pintype "passive"))
    )
    (net (code "187") (name "S12-IN") (class "Default")
      (node (ref "30") (pin "2") (pinfunction "E_2") (pintype "passive"))
      (node (ref "IC17") (pin "6") (pinfunction "INPUTS_B-_6") (pintype "bidirectional"))
      (node (ref "R99") (pin "2") (pinfunction "P$2_2") (pintype "passive"))
    )
    (net (code "188") (name "S13-IN") (class "Default")
      (node (ref "31") (pin "2") (pinfunction "E_2") (pintype "passive"))
      (node (ref "IC18") (pin "2") (pinfunction "INPUTS_A-_2") (pintype "bidirectional"))
      (node (ref "R100") (pin "2") (pinfunction "P$2_2") (pintype "passive"))
    )
    (net (code "189") (name "S14-IN") (class "Default")
      (node (ref "32") (pin "2") (pinfunction "E_2") (pintype "passive"))
      (node (ref "IC18") (pin "6") (pinfunction "INPUTS_B-_6") (pintype "bidirectional"))
      (node (ref "R101") (pin "2") (pinfunction "P$2_2") (pintype "passive"))
    )
    (net (code "190") (name "S15-IN") (class "Default")
      (node (ref "33") (pin "2") (pinfunction "E_2") (pintype "passive"))
      (node (ref "IC19") (pin "2") (pinfunction "INPUTS_A-_2") (pintype "bidirectional"))
      (node (ref "R102") (pin "2") (pinfunction "P$2_2") (pintype "passive"))
    )
    (net (code "191") (name "S16-IN") (class "Default")
      (node (ref "34") (pin "2") (pinfunction "E_2") (pintype "passive"))
      (node (ref "IC19") (pin "6") (pinfunction "INPUTS_B-_6") (pintype "bidirectional"))
      (node (ref "R103") (pin "2") (pinfunction "P$2_2") (pintype "passive"))
    )
    (net (code "192") (name "S17-IN") (class "Default")
      (node (ref "35") (pin "2") (pinfunction "E_2") (pintype "passive"))
      (node (ref "IC20") (pin "2") (pinfunction "INPUTS_A-_2") (pintype "bidirectional"))
      (node (ref "R104") (pin "2") (pinfunction "P$2_2") (pintype "passive"))
    )
    (net (code "193") (name "S18-IN") (class "Default")
      (node (ref "36") (pin "2") (pinfunction "E_2") (pintype "passive"))
      (node (ref "IC20") (pin "6") (pinfunction "INPUTS_B-_6") (pintype "bidirectional"))
      (node (ref "R105") (pin "2") (pinfunction "P$2_2") (pintype "passive"))
    )
    (net (code "194") (name "S19-IN") (class "Default")
      (node (ref "37") (pin "2") (pinfunction "E_2") (pintype "passive"))
      (node (ref "IC21") (pin "2") (pinfunction "INPUTS_A-_2") (pintype "bidirectional"))
      (node (ref "R106") (pin "2") (pinfunction "P$2_2") (pintype "passive"))
    )
    (net (code "195") (name "S20-IN") (class "Default")
      (node (ref "38") (pin "2") (pinfunction "E_2") (pintype "passive"))
      (node (ref "IC21") (pin "6") (pinfunction "INPUTS_B-_6") (pintype "bidirectional"))
      (node (ref "R107") (pin "2") (pinfunction "P$2_2") (pintype "passive"))
    )
    (net (code "196") (name "S21-IN") (class "Default")
      (node (ref "39") (pin "2") (pinfunction "E_2") (pintype "passive"))
      (node (ref "IC22") (pin "2") (pinfunction "INPUTS_A-_2") (pintype "bidirectional"))
      (node (ref "R108") (pin "2") (pinfunction "P$2_2") (pintype "passive"))
    )
    (net (code "197") (name "S22-IN") (class "Default")
      (node (ref "40") (pin "2") (pinfunction "E_2") (pintype "passive"))
      (node (ref "IC22") (pin "6") (pinfunction "INPUTS_B-_6") (pintype "bidirectional"))
      (node (ref "R109") (pin "2") (pinfunction "P$2_2") (pintype "passive"))
    )
    (net (code "198") (name "S23-IN") (class "Default")
      (node (ref "41") (pin "2") (pinfunction "E_2") (pintype "passive"))
      (node (ref "IC23") (pin "2") (pinfunction "INPUTS_A-_2") (pintype "bidirectional"))
      (node (ref "R110") (pin "2") (pinfunction "P$2_2") (pintype "passive"))
    )
    (net (code "199") (name "S24-IN") (class "Default")
      (node (ref "42") (pin "2") (pinfunction "E_2") (pintype "passive"))
      (node (ref "IC23") (pin "6") (pinfunction "INPUTS_B-_6") (pintype "bidirectional"))
      (node (ref "R111") (pin "2") (pinfunction "P$2_2") (pintype "passive"))
    )
    (net (code "200") (name "S25-IN") (class "Default")
      (node (ref "43") (pin "2") (pinfunction "E_2") (pintype "passive"))
      (node (ref "IC24") (pin "2") (pinfunction "INPUTS_A-_2") (pintype "bidirectional"))
      (node (ref "R112") (pin "2") (pinfunction "P$2_2") (pintype "passive"))
    )
    (net (code "201") (name "S26-IN") (class "Default")
      (node (ref "44") (pin "2") (pinfunction "E_2") (pintype "passive"))
      (node (ref "IC24") (pin "6") (pinfunction "INPUTS_B-_6") (pintype "bidirectional"))
      (node (ref "R113") (pin "2") (pinfunction "P$2_2") (pintype "passive"))
    )
    (net (code "202") (name "S27-IN") (class "Default")
      (node (ref "45") (pin "2") (pinfunction "E_2") (pintype "passive"))
      (node (ref "IC25") (pin "2") (pinfunction "INPUTS_A-_2") (pintype "bidirectional"))
      (node (ref "R114") (pin "2") (pinfunction "P$2_2") (pintype "passive"))
    )
    (net (code "203") (name "S28-IN") (class "Default")
      (node (ref "46") (pin "2") (pinfunction "E_2") (pintype "passive"))
      (node (ref "IC25") (pin "6") (pinfunction "INPUTS_B-_6") (pintype "bidirectional"))
      (node (ref "R115") (pin "2") (pinfunction "P$2_2") (pintype "passive"))
    )
    (net (code "204") (name "S29-IN") (class "Default")
      (node (ref "47") (pin "2") (pinfunction "E_2") (pintype "passive"))
      (node (ref "IC26") (pin "2") (pinfunction "INPUTS_A-_2") (pintype "bidirectional"))
      (node (ref "R116") (pin "2") (pinfunction "P$2_2") (pintype "passive"))
    )
    (net (code "205") (name "S30-IN") (class "Default")
      (node (ref "48") (pin "2") (pinfunction "E_2") (pintype "passive"))
      (node (ref "IC26") (pin "6") (pinfunction "INPUTS_B-_6") (pintype "bidirectional"))
      (node (ref "R117") (pin "2") (pinfunction "P$2_2") (pintype "passive"))
    )
    (net (code "206") (name "S31-IN") (class "Default")
      (node (ref "49") (pin "2") (pinfunction "E_2") (pintype "passive"))
      (node (ref "IC28") (pin "2") (pinfunction "INPUTS_A-_2") (pintype "bidirectional"))
      (node (ref "R118") (pin "2") (pinfunction "P$2_2") (pintype "passive"))
    )
    (net (code "207") (name "S32-IN") (class "Default")
      (node (ref "50") (pin "2") (pinfunction "E_2") (pintype "passive"))
      (node (ref "IC28") (pin "6") (pinfunction "INPUTS_B-_6") (pintype "bidirectional"))
      (node (ref "R119") (pin "2") (pinfunction "P$2_2") (pintype "passive"))
    )
    (net (code "208") (name "SCL3") (class "Default")
      (node (ref "PIC32MK1024MCM100") (pin "70") (pinfunction "PGC2/RPB6/SCL3/SCK2/PMA15/RB6_70") (pintype "bidirectional"))
      (node (ref "R4") (pin "1") (pinfunction "P$1_1") (pintype "passive"))
      (node (ref "U$9") (pin "3") (pinfunction "SCL_3") (pintype "bidirectional"))
    )
    (net (code "209") (name "SDA3") (class "Default")
      (node (ref "PIC32MK1024MCM100") (pin "69") (pinfunction "PGD2/RPB5/SDA3/USBID1/RB5_69") (pintype "bidirectional"))
      (node (ref "R2") (pin "1") (pinfunction "P$1_1") (pintype "passive"))
      (node (ref "U$9") (pin "4") (pinfunction "SDA_4") (pintype "bidirectional"))
    )
    (net (code "210") (name "U1-RX") (class "Default")
      (node (ref "PIC32MK1024MCM100") (pin "87") (pinfunction "RPF0/PWM11H/PMD11/RF0_87") (pintype "bidirectional"))
      (node (ref "UART1") (pin "3") (pinfunction "3_3") (pintype "bidirectional"))
    )
    (net (code "211") (name "U1-TX") (class "Default")
      (node (ref "PIC32MK1024MCM100") (pin "88") (pinfunction "RPF1/PWM11L/PMD10/RF1_88") (pintype "bidirectional"))
      (node (ref "UART1") (pin "2") (pinfunction "2_2") (pintype "bidirectional"))
    )
    (net (code "212") (name "U5-RX") (class "Default")
      (node (ref "DEBUG_UART") (pin "3") (pinfunction "3_3") (pintype "passive"))
      (node (ref "PIC32MK1024MCM100") (pin "64") (pinfunction "OSCO/CLKO/RPC15/RC15_64") (pintype "bidirectional"))
    )
    (net (code "213") (name "U5-TX") (class "Default")
      (node (ref "DEBUG_UART") (pin "2") (pinfunction "2_2") (pintype "passive"))
      (node (ref "PIC32MK1024MCM100") (pin "63") (pinfunction "OSCI/CLKI/AN49/CVD49/RPC12/RC12_63") (pintype "bidirectional"))
    )
    (net (code "214") (name "VCC-3.3V") (class "Default")
      (node (ref "1") (pin "1") (pinfunction "C_1") (pintype "passive"))
      (node (ref "10") (pin "1") (pinfunction "C_1") (pintype "passive"))
      (node (ref "11") (pin "1") (pinfunction "C_1") (pintype "passive"))
      (node (ref "12") (pin "1") (pinfunction "C_1") (pintype "passive"))
      (node (ref "13") (pin "1") (pinfunction "C_1") (pintype "passive"))
      (node (ref "14") (pin "1") (pinfunction "C_1") (pintype "passive"))
      (node (ref "15") (pin "1") (pinfunction "C_1") (pintype "passive"))
      (node (ref "16") (pin "1") (pinfunction "C_1") (pintype "passive"))
      (node (ref "17") (pin "1") (pinfunction "C_1") (pintype "passive"))
      (node (ref "18") (pin "1") (pinfunction "C_1") (pintype "passive"))
      (node (ref "19") (pin "1") (pinfunction "C_1") (pintype "passive"))
      (node (ref "2") (pin "1") (pinfunction "C_1") (pintype "passive"))
      (node (ref "20") (pin "1") (pinfunction "C_1") (pintype "passive"))
      (node (ref "21") (pin "1") (pinfunction "C_1") (pintype "passive"))
      (node (ref "22") (pin "1") (pinfunction "C_1") (pintype "passive"))
      (node (ref "23") (pin "1") (pinfunction "C_1") (pintype "passive"))
      (node (ref "24") (pin "1") (pinfunction "C_1") (pintype "passive"))
      (node (ref "25") (pin "1") (pinfunction "C_1") (pintype "passive"))
      (node (ref "26") (pin "1") (pinfunction "C_1") (pintype "passive"))
      (node (ref "27") (pin "1") (pinfunction "C_1") (pintype "passive"))
      (node (ref "28") (pin "1") (pinfunction "C_1") (pintype "passive"))
      (node (ref "29") (pin "1") (pinfunction "C_1") (pintype "passive"))
      (node (ref "3") (pin "1") (pinfunction "C_1") (pintype "passive"))
      (node (ref "30") (pin "1") (pinfunction "C_1") (pintype "passive"))
      (node (ref "31") (pin "1") (pinfunction "C_1") (pintype "passive"))
      (node (ref "32") (pin "1") (pinfunction "C_1") (pintype "passive"))
      (node (ref "33") (pin "1") (pinfunction "C_1") (pintype "passive"))
      (node (ref "34") (pin "1") (pinfunction "C_1") (pintype "passive"))
      (node (ref "35") (pin "1") (pinfunction "C_1") (pintype "passive"))
      (node (ref "36") (pin "1") (pinfunction "C_1") (pintype "passive"))
      (node (ref "37") (pin "1") (pinfunction "C_1") (pintype "passive"))
      (node (ref "38") (pin "1") (pinfunction "C_1") (pintype "passive"))
      (node (ref "39") (pin "1") (pinfunction "C_1") (pintype "passive"))
      (node (ref "4") (pin "1") (pinfunction "C_1") (pintype "passive"))
      (node (ref "40") (pin "1") (pinfunction "C_1") (pintype "passive"))
      (node (ref "41") (pin "1") (pinfunction "C_1") (pintype "passive"))
      (node (ref "42") (pin "1") (pinfunction "C_1") (pintype "passive"))
      (node (ref "43") (pin "1") (pinfunction "C_1") (pintype "passive"))
      (node (ref "44") (pin "1") (pinfunction "C_1") (pintype "passive"))
      (node (ref "45") (pin "1") (pinfunction "C_1") (pintype "passive"))
      (node (ref "46") (pin "1") (pinfunction "C_1") (pintype "passive"))
      (node (ref "47") (pin "1") (pinfunction "C_1") (pintype "passive"))
      (node (ref "48") (pin "1") (pinfunction "C_1") (pintype "passive"))
      (node (ref "49") (pin "1") (pinfunction "C_1") (pintype "passive"))
      (node (ref "5") (pin "1") (pinfunction "C_1") (pintype "passive"))
      (node (ref "50") (pin "1") (pinfunction "C_1") (pintype "passive"))
      (node (ref "51") (pin "1") (pinfunction "C_1") (pintype "passive"))
      (node (ref "52") (pin "1") (pinfunction "C_1") (pintype "passive"))
      (node (ref "53") (pin "1") (pinfunction "C_1") (pintype "passive"))
      (node (ref "54") (pin "1") (pinfunction "C_1") (pintype "passive"))
      (node (ref "55") (pin "1") (pinfunction "C_1") (pintype "passive"))
      (node (ref "57") (pin "1") (pinfunction "C_1") (pintype "passive"))
      (node (ref "59") (pin "1") (pinfunction "C_1") (pintype "passive"))
      (node (ref "6") (pin "1") (pinfunction "C_1") (pintype "passive"))
      (node (ref "60") (pin "1") (pinfunction "C_1") (pintype "passive"))
      (node (ref "61") (pin "1") (pinfunction "C_1") (pintype "passive"))
      (node (ref "63") (pin "1") (pinfunction "C_1") (pintype "passive"))
      (node (ref "7") (pin "1") (pinfunction "C_1") (pintype "passive"))
      (node (ref "8") (pin "1") (pinfunction "C_1") (pintype "passive"))
      (node (ref "9") (pin "1") (pinfunction "C_1") (pintype "passive"))
      (node (ref "C1") (pin "1") (pinfunction "P$1_1") (pintype "passive"))
      (node (ref "C10") (pin "1") (pinfunction "P$1_1") (pintype "passive"))
      (node (ref "C14") (pin "1") (pinfunction "P$1_1") (pintype "passive"))
      (node (ref "C15") (pin "1") (pinfunction "P$1_1") (pintype "passive"))
      (node (ref "C17") (pin "2") (pinfunction "P$2_2") (pintype "passive"))
      (node (ref "C18") (pin "1") (pinfunction "P$1_1") (pintype "passive"))
      (node (ref "C19") (pin "1") (pinfunction "P$1_1") (pintype "passive"))
      (node (ref "C2") (pin "2") (pinfunction "P$2_2") (pintype "passive"))
      (node (ref "C20") (pin "1") (pinfunction "P$1_1") (pintype "passive"))
      (node (ref "C22") (pin "1") (pinfunction "P$1_1") (pintype "passive"))
      (node (ref "C23") (pin "1") (pinfunction "P$1_1") (pintype "passive"))
      (node (ref "C24") (pin "1") (pinfunction "P$1_1") (pintype "passive"))
      (node (ref "C25") (pin "1") (pinfunction "P$1_1") (pintype "passive"))
      (node (ref "C26") (pin "1") (pinfunction "P$1_1") (pintype "passive"))
      (node (ref "C27") (pin "1") (pinfunction "P$1_1") (pintype "passive"))
      (node (ref "C28") (pin "1") (pinfunction "P$1_1") (pintype "passive"))
      (node (ref "C29") (pin "1") (pinfunction "P$1_1") (pintype "passive"))
      (node (ref "C30") (pin "1") (pinfunction "P$1_1") (pintype "passive"))
      (node (ref "C31") (pin "1") (pinfunction "P$1_1") (pintype "passive"))
      (node (ref "C32") (pin "1") (pinfunction "P$1_1") (pintype "passive"))
      (node (ref "C33") (pin "1") (pinfunction "P$1_1") (pintype "passive"))
      (node (ref "C34") (pin "1") (pinfunction "P$1_1") (pintype "passive"))
      (node (ref "C35") (pin "1") (pinfunction "P$1_1") (pintype "passive"))
      (node (ref "C36") (pin "1") (pinfunction "P$1_1") (pintype "passive"))
      (node (ref "C37") (pin "1") (pinfunction "P$1_1") (pintype "passive"))
      (node (ref "C38") (pin "1") (pinfunction "P$1_1") (pintype "passive"))
      (node (ref "C39") (pin "+") (pinfunction "P$1+_+") (pintype "passive"))
      (node (ref "C4") (pin "1") (pinfunction "P$1_1") (pintype "passive"))
      (node (ref "C40") (pin "1") (pinfunction "P$1_1") (pintype "passive"))
      (node (ref "C41") (pin "1") (pinfunction "P$1_1") (pintype "passive"))
      (node (ref "C42") (pin "1") (pinfunction "P$1_1") (pintype "passive"))
      (node (ref "C43") (pin "1") (pinfunction "P$1_1") (pintype "passive"))
      (node (ref "C44") (pin "1") (pinfunction "P$1_1") (pintype "passive"))
      (node (ref "C45") (pin "1") (pinfunction "P$1_1") (pintype "passive"))
      (node (ref "C46") (pin "1") (pinfunction "P$1_1") (pintype "passive"))
      (node (ref "C48") (pin "1") (pinfunction "P$1_1") (pintype "passive"))
      (node (ref "C5") (pin "2") (pinfunction "P$2_2") (pintype "passive"))
      (node (ref "C6") (pin "1") (pinfunction "P$1_1") (pintype "passive"))
      (node (ref "C7") (pin "1") (pinfunction "P$1_1") (pintype "passive"))
      (node (ref "C8") (pin "1") (pinfunction "P$1_1") (pintype "passive"))
      (node (ref "C9") (pin "2") (pinfunction "P$2_2") (pintype "passive"))
      (node (ref "DEBUG_UART") (pin "1") (pinfunction "1_1") (pintype "passive"))
      (node (ref "IC1") (pin "2") (pinfunction "OUTPUT_2") (pintype "bidirectional"))
      (node (ref "IC1") (pin "4") (pinfunction "VOUT_4") (pintype "bidirectional"))
      (node (ref "IC11") (pin "8") (pinfunction "VCC_8") (pintype "bidirectional"))
      (node (ref "IC12") (pin "8") (pinfunction "VCC_8") (pintype "bidirectional"))
      (node (ref "IC13") (pin "8") (pinfunction "VCC_8") (pintype "bidirectional"))
      (node (ref "IC14") (pin "8") (pinfunction "VCC_8") (pintype "bidirectional"))
      (node (ref "IC15") (pin "8") (pinfunction "VCC_8") (pintype "bidirectional"))
      (node (ref "IC16") (pin "8") (pinfunction "VCC_8") (pintype "bidirectional"))
      (node (ref "IC17") (pin "8") (pinfunction "VCC_8") (pintype "bidirectional"))
      (node (ref "IC18") (pin "8") (pinfunction "VCC_8") (pintype "bidirectional"))
      (node (ref "IC19") (pin "8") (pinfunction "VCC_8") (pintype "bidirectional"))
      (node (ref "IC2") (pin "8") (pinfunction "VCC_8") (pintype "bidirectional"))
      (node (ref "IC20") (pin "8") (pinfunction "VCC_8") (pintype "bidirectional"))
      (node (ref "IC21") (pin "8") (pinfunction "VCC_8") (pintype "bidirectional"))
      (node (ref "IC22") (pin "8") (pinfunction "VCC_8") (pintype "bidirectional"))
      (node (ref "IC23") (pin "8") (pinfunction "VCC_8") (pintype "bidirectional"))
      (node (ref "IC24") (pin "8") (pinfunction "VCC_8") (pintype "bidirectional"))
      (node (ref "IC25") (pin "8") (pinfunction "VCC_8") (pintype "bidirectional"))
      (node (ref "IC26") (pin "8") (pinfunction "VCC_8") (pintype "bidirectional"))
      (node (ref "IC27") (pin "8") (pinfunction "VCC_8") (pintype "bidirectional"))
      (node (ref "IC28") (pin "8") (pinfunction "VCC_8") (pintype "bidirectional"))
      (node (ref "IC29") (pin "8") (pinfunction "VCC_8") (pintype "bidirectional"))
      (node (ref "IC3") (pin "8") (pinfunction "VCC_8") (pintype "bidirectional"))
      (node (ref "IC30") (pin "8") (pinfunction "VCC_8") (pintype "bidirectional"))
      (node (ref "IC31") (pin "8") (pinfunction "VCC_8") (pintype "bidirectional"))
      (node (ref "IC32") (pin "8") (pinfunction "VCC_8") (pintype "bidirectional"))
      (node (ref "IC33") (pin "8") (pinfunction "VCC_8") (pintype "bidirectional"))
      (node (ref "IC34") (pin "8") (pinfunction "VCC_8") (pintype "bidirectional"))
      (node (ref "IC5") (pin "8") (pinfunction "VCC_8") (pintype "bidirectional"))
      (node (ref "IC6") (pin "8") (pinfunction "VCC_8") (pintype "bidirectional"))
      (node (ref "IC8") (pin "8") (pinfunction "VCC_8") (pintype "bidirectional"))
      (node (ref "IC9") (pin "8") (pinfunction "VCC_8") (pintype "bidirectional"))
      (node (ref "MCLR") (pin "2") (pinfunction "P$2_2") (pintype "bidirectional"))
      (node (ref "PIC32MK1024MCM100") (pin "16") (pinfunction "VDD_2_16") (pintype "bidirectional"))
      (node (ref "PIC32MK1024MCM100") (pin "2") (pinfunction "VDD_1_2") (pintype "bidirectional"))
      (node (ref "PIC32MK1024MCM100") (pin "30") (pinfunction "AVDD_30") (pintype "bidirectional"))
      (node (ref "PIC32MK1024MCM100") (pin "37") (pinfunction "VDD_3_37") (pintype "bidirectional"))
      (node (ref "PIC32MK1024MCM100") (pin "46") (pinfunction "VDD_4_46") (pintype "bidirectional"))
      (node (ref "PIC32MK1024MCM100") (pin "55") (pinfunction "VUSB3V3_55") (pintype "bidirectional"))
      (node (ref "PIC32MK1024MCM100") (pin "62") (pinfunction "VDD_5_62") (pintype "bidirectional"))
      (node (ref "PIC32MK1024MCM100") (pin "86") (pinfunction "VDD_6_86") (pintype "bidirectional"))
      (node (ref "Q2") (pin "1") (pinfunction "G_1") (pintype "bidirectional"))
      (node (ref "R1") (pin "2") (pinfunction "P$2_2") (pintype "passive"))
      (node (ref "R10") (pin "1") (pinfunction "P$1_1") (pintype "passive"))
      (node (ref "R11") (pin "2") (pinfunction "P$2_2") (pintype "passive"))
      (node (ref "R12") (pin "1") (pinfunction "P$1_1") (pintype "passive"))
      (node (ref "R13") (pin "1") (pinfunction "P$1_1") (pintype "passive"))
      (node (ref "R14") (pin "2") (pinfunction "P$2_2") (pintype "passive"))
      (node (ref "R146") (pin "1") (pinfunction "P$1_1") (pintype "passive"))
      (node (ref "R147") (pin "2") (pinfunction "P$2_2") (pintype "passive"))
      (node (ref "R148") (pin "1") (pinfunction "P$1_1") (pintype "passive"))
      (node (ref "R149") (pin "2") (pinfunction "P$2_2") (pintype "passive"))
      (node (ref "R15") (pin "1") (pinfunction "P$1_1") (pintype "passive"))
      (node (ref "R150") (pin "1") (pinfunction "P$1_1") (pintype "passive"))
      (node (ref "R151") (pin "2") (pinfunction "P$2_2") (pintype "passive"))
      (node (ref "R152") (pin "1") (pinfunction "P$1_1") (pintype "passive"))
      (node (ref "R153") (pin "2") (pinfunction "P$2_2") (pintype "passive"))
      (node (ref "R154") (pin "1") (pinfunction "P$1_1") (pintype "passive"))
      (node (ref "R155") (pin "2") (pinfunction "P$2_2") (pintype "passive"))
      (node (ref "R156") (pin "1") (pinfunction "P$1_1") (pintype "passive"))
      (node (ref "R157") (pin "2") (pinfunction "P$2_2") (pintype "passive"))
      (node (ref "R158") (pin "1") (pinfunction "P$1_1") (pintype "passive"))
      (node (ref "R159") (pin "2") (pinfunction "P$2_2") (pintype "passive"))
      (node (ref "R16") (pin "2") (pinfunction "P$2_2") (pintype "passive"))
      (node (ref "R160") (pin "1") (pinfunction "P$1_1") (pintype "passive"))
      (node (ref "R161") (pin "2") (pinfunction "P$2_2") (pintype "passive"))
      (node (ref "R162") (pin "1") (pinfunction "P$1_1") (pintype "passive"))
      (node (ref "R163") (pin "2") (pinfunction "P$2_2") (pintype "passive"))
      (node (ref "R164") (pin "2") (pinfunction "P$2_2") (pintype "passive"))
      (node (ref "R165") (pin "1") (pinfunction "P$1_1") (pintype "passive"))
      (node (ref "R168") (pin "2") (pinfunction "P$2_2") (pintype "passive"))
      (node (ref "R169") (pin "1") (pinfunction "P$1_1") (pintype "passive"))
      (node (ref "R17") (pin "1") (pinfunction "P$1_1") (pintype "passive"))
      (node (ref "R170") (pin "2") (pinfunction "P$2_2") (pintype "passive"))
      (node (ref "R171") (pin "1") (pinfunction "P$1_1") (pintype "passive"))
      (node (ref "R174") (pin "2") (pinfunction "P$2_2") (pintype "passive"))
      (node (ref "R175") (pin "1") (pinfunction "P$1_1") (pintype "passive"))
      (node (ref "R176") (pin "2") (pinfunction "P$2_2") (pintype "passive"))
      (node (ref "R177") (pin "1") (pinfunction "P$1_1") (pintype "passive"))
      (node (ref "R180") (pin "1") (pinfunction "P$1_1") (pintype "passive"))
      (node (ref "R181") (pin "2") (pinfunction "P$2_2") (pintype "passive"))
      (node (ref "R182") (pin "2") (pinfunction "P$2_2") (pintype "passive"))
      (node (ref "R183") (pin "1") (pinfunction "P$1_1") (pintype "passive"))
      (node (ref "R184") (pin "2") (pinfunction "P$2_2") (pintype "passive"))
      (node (ref "R186") (pin "2") (pinfunction "P$2_2") (pintype "passive"))
      (node (ref "R187") (pin "1") (pinfunction "P$1_1") (pintype "passive"))
      (node (ref "R189") (pin "1") (pinfunction "P$1_1") (pintype "passive"))
      (node (ref "R190") (pin "2") (pinfunction "P$2_2") (pintype "passive"))
      (node (ref "R191") (pin "1") (pinfunction "P$1_1") (pintype "passive"))
      (node (ref "R192") (pin "2") (pinfunction "P$2_2") (pintype "passive"))
      (node (ref "R194") (pin "1") (pinfunction "P$1_1") (pintype "passive"))
      (node (ref "R195") (pin "2") (pinfunction "P$2_2") (pintype "passive"))
      (node (ref "R197") (pin "1") (pinfunction "P$1_1") (pintype "passive"))
      (node (ref "R2") (pin "2") (pinfunction "P$2_2") (pintype "passive"))
      (node (ref "R206") (pin "2") (pinfunction "P$2_2") (pintype "passive"))
      (node (ref "R21") (pin "2") (pinfunction "P$2_2") (pintype "passive"))
      (node (ref "R3") (pin "2") (pinfunction "P$2_2") (pintype "passive"))
      (node (ref "R4") (pin "2") (pinfunction "P$2_2") (pintype "passive"))
      (node (ref "R6") (pin "2") (pinfunction "P$2_2") (pintype "passive"))
      (node (ref "R7") (pin "2") (pinfunction "P$2_2") (pintype "passive"))
      (node (ref "R8") (pin "1") (pinfunction "P$1_1") (pintype "passive"))
      (node (ref "R86") (pin "1") (pinfunction "P$1_1") (pintype "passive"))
      (node (ref "R87") (pin "2") (pinfunction "P$2_2") (pintype "passive"))
      (node (ref "R9") (pin "2") (pinfunction "P$2_2") (pintype "passive"))
      (node (ref "U$9") (pin "1") (pinfunction "VDD_1") (pintype "power_in"))
      (node (ref "UART1") (pin "1") (pinfunction "1_1") (pintype "bidirectional"))
    )
    (net (code "215") (name "VCC-5V") (class "Default")
      (node (ref "J2") (pin "1") (pinfunction "1_1") (pintype "bidirectional"))
      (node (ref "U$3") (pin "1") (pinfunction "P$1_1") (pintype "bidirectional"))
    )
    (net (code "216") (name "unconnected-(IC3-OUTPUT_B-Pad7)") (class "Default")
      (node (ref "IC3") (pin "7") (pinfunction "OUTPUT_B_7") (pintype "bidirectional"))
    )
    (net (code "217") (name "unconnected-(IC29-INPUTS_A--Pad2)") (class "Default")
      (node (ref "IC29") (pin "2") (pinfunction "INPUTS_A-_2") (pintype "bidirectional"))
    )
    (net (code "218") (name "unconnected-(IC29-OUTPUT_A-Pad1)") (class "Default")
      (node (ref "IC29") (pin "1") (pinfunction "OUTPUT_A_1") (pintype "bidirectional"))
    )
    (net (code "219") (name "unconnected-(IC30-INPUTS_B--Pad6)") (class "Default")
      (node (ref "IC30") (pin "6") (pinfunction "INPUTS_B-_6") (pintype "bidirectional"))
    )
    (net (code "220") (name "unconnected-(IC30-OUTPUT_B-Pad7)") (class "Default")
      (node (ref "IC30") (pin "7") (pinfunction "OUTPUT_B_7") (pintype "bidirectional"))
    )
    (net (code "221") (name "unconnected-(LED1-DOUT-Pad2)") (class "Default")
      (node (ref "LED1") (pin "2") (pinfunction "DOUT_2") (pintype "bidirectional"))
    )
    (net (code "222") (name "unconnected-(PIC32MK1024MCM100-AN12{slash}CVD12{slash}C2IN2-{slash}C5IN2-{slash}SDA4{slash}FLT5{slash}PMA11{slash}RE12-Pad41)") (class "Default")
      (node (ref "PIC32MK1024MCM100") (pin "41") (pinfunction "AN12/CVD12/C2IN2-/C5IN2-/SDA4/FLT5/PMA11/RE12_41") (pintype "bidirectional"))
    )
    (net (code "223") (name "unconnected-(PIC32MK1024MCM100-AN13{slash}CVD13{slash}C3IN2-{slash}SCL4{slash}FLT6{slash}PMA10{slash}RE13-Pad42)") (class "Default")
      (node (ref "PIC32MK1024MCM100") (pin "42") (pinfunction "AN13/CVD13/C3IN2-/SCL4/FLT6/PMA10/RE13_42") (pintype "bidirectional"))
    )
    (net (code "224") (name "unconnected-(PIC32MK1024MCM100-AN14{slash}CVD14{slash}RPE14{slash}FLT7{slash}PMA1{slash}RE14-Pad43)") (class "Default")
      (node (ref "PIC32MK1024MCM100") (pin "43") (pinfunction "AN14/CVD14/RPE14/FLT7/PMA1/RE14_43") (pintype "bidirectional"))
    )
    (net (code "225") (name "unconnected-(PIC32MK1024MCM100-AN15{slash}CVD15{slash}RPE15{slash}FLT8{slash}PMA0{slash}RE15-Pad44)") (class "Default")
      (node (ref "PIC32MK1024MCM100") (pin "44") (pinfunction "AN15/CVD15/RPE15/FLT8/PMA0/RE15_44") (pintype "bidirectional"))
    )
    (net (code "226") (name "unconnected-(PIC32MK1024MCM100-AN19{slash}CVD19{slash}RPG6{slash}PWM10L{slash}VBUSON2{slash}PMA5{slash}RG6-Pad10)") (class "Default")
      (node (ref "PIC32MK1024MCM100") (pin "10") (pinfunction "AN19/CVD19/RPG6/PWM10L/VBUSON2/PMA5/RG6_10") (pintype "bidirectional"))
    )
    (net (code "227") (name "unconnected-(PIC32MK1024MCM100-AN22{slash}CVD22{slash}RG10-Pad17)") (class "Default")
      (node (ref "PIC32MK1024MCM100") (pin "17") (pinfunction "AN22/CVD22/RG10_17") (pintype "bidirectional"))
    )
    (net (code "228") (name "unconnected-(PIC32MK1024MCM100-OA2IN+{slash}AN1{slash}C2IN1+{slash}RPA1{slash}RA1-Pad23)") (class "Default")
      (node (ref "PIC32MK1024MCM100") (pin "23") (pinfunction "OA2IN+/AN1/C2IN1+/RPA1/RA1_23") (pintype "bidirectional"))
    )
    (net (code "229") (name "unconnected-(PIC32MK1024MCM100-TRCLK{slash}PWM9H{slash}PMA18{slash}RF6-Pad91)") (class "Default")
      (node (ref "PIC32MK1024MCM100") (pin "91") (pinfunction "TRCLK/PWM9H/PMA18/RF6_91") (pintype "bidirectional"))
    )
    (net (code "230") (name "unconnected-(U$9-A-Pad6)") (class "Default")
      (node (ref "U$9") (pin "6") (pinfunction "A_6") (pintype "bidirectional"))
    )
  )
)
